# Sheet2s.net
KiCad netlist of a schematic drawn in Altium Designer
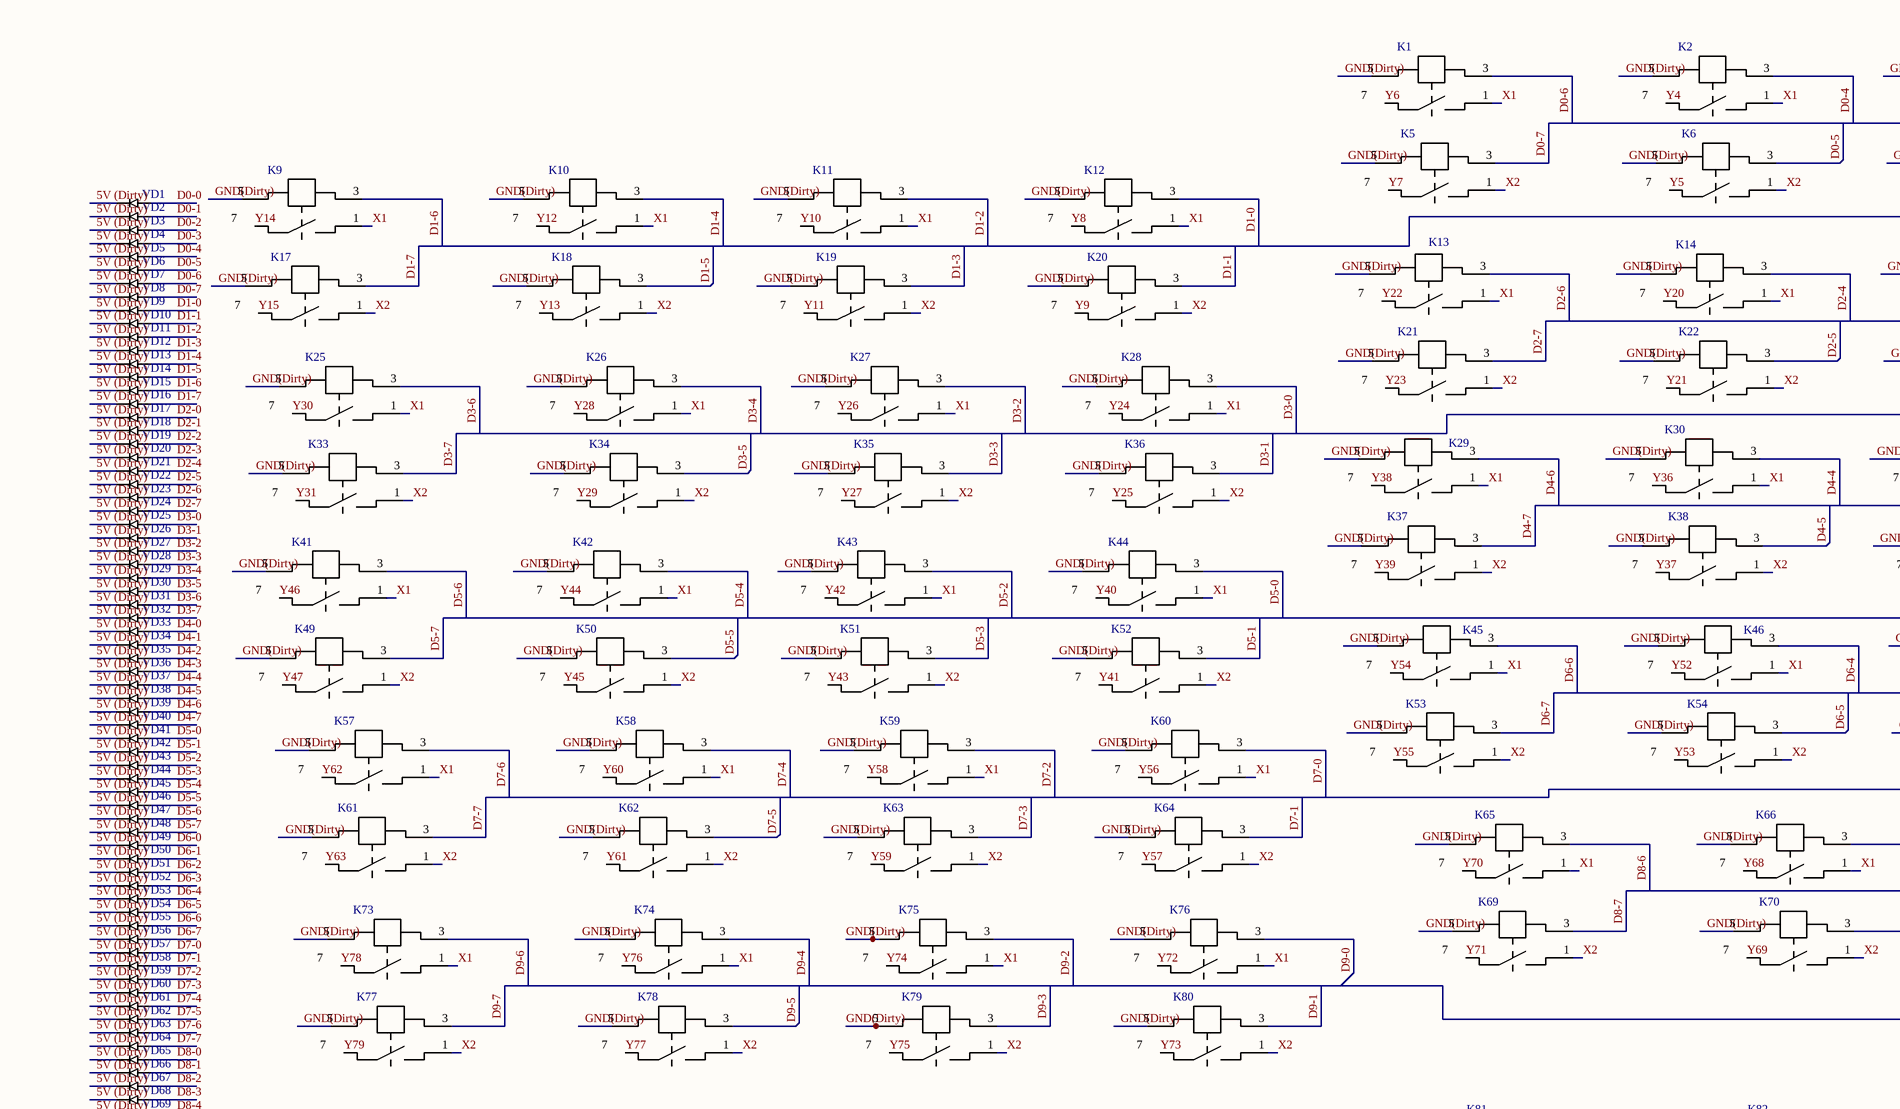
[diagram p0: Sheet2s.SchDoc, top left]
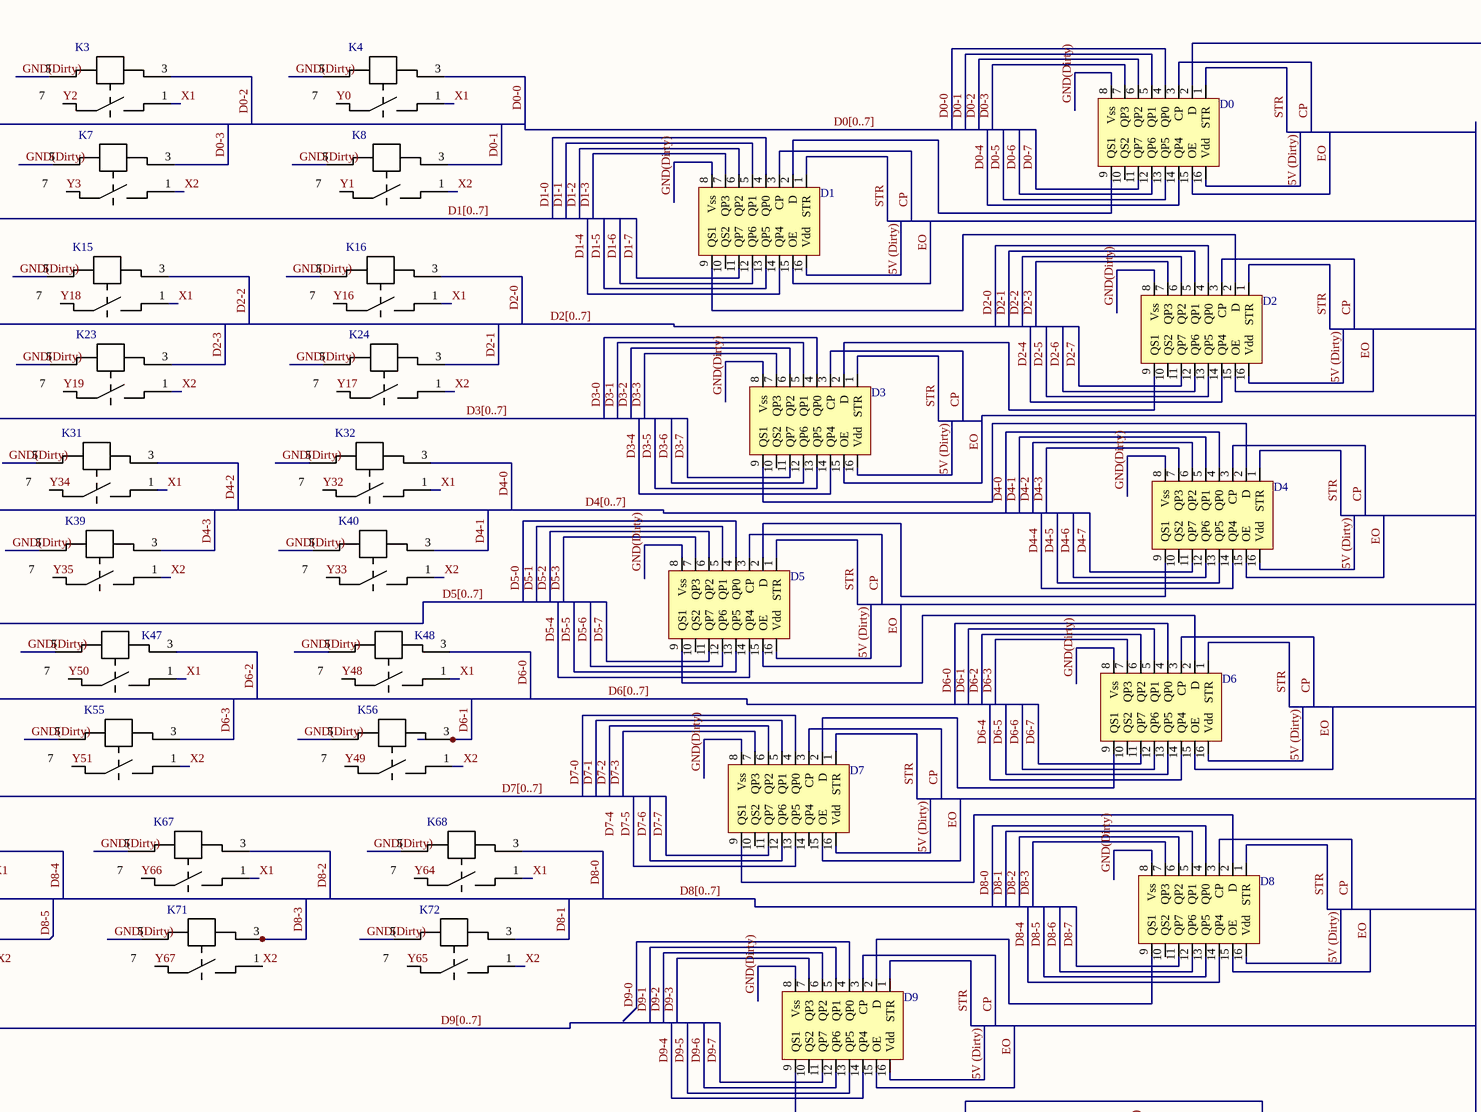
[diagram p1: Sheet2s.SchDoc, top right]
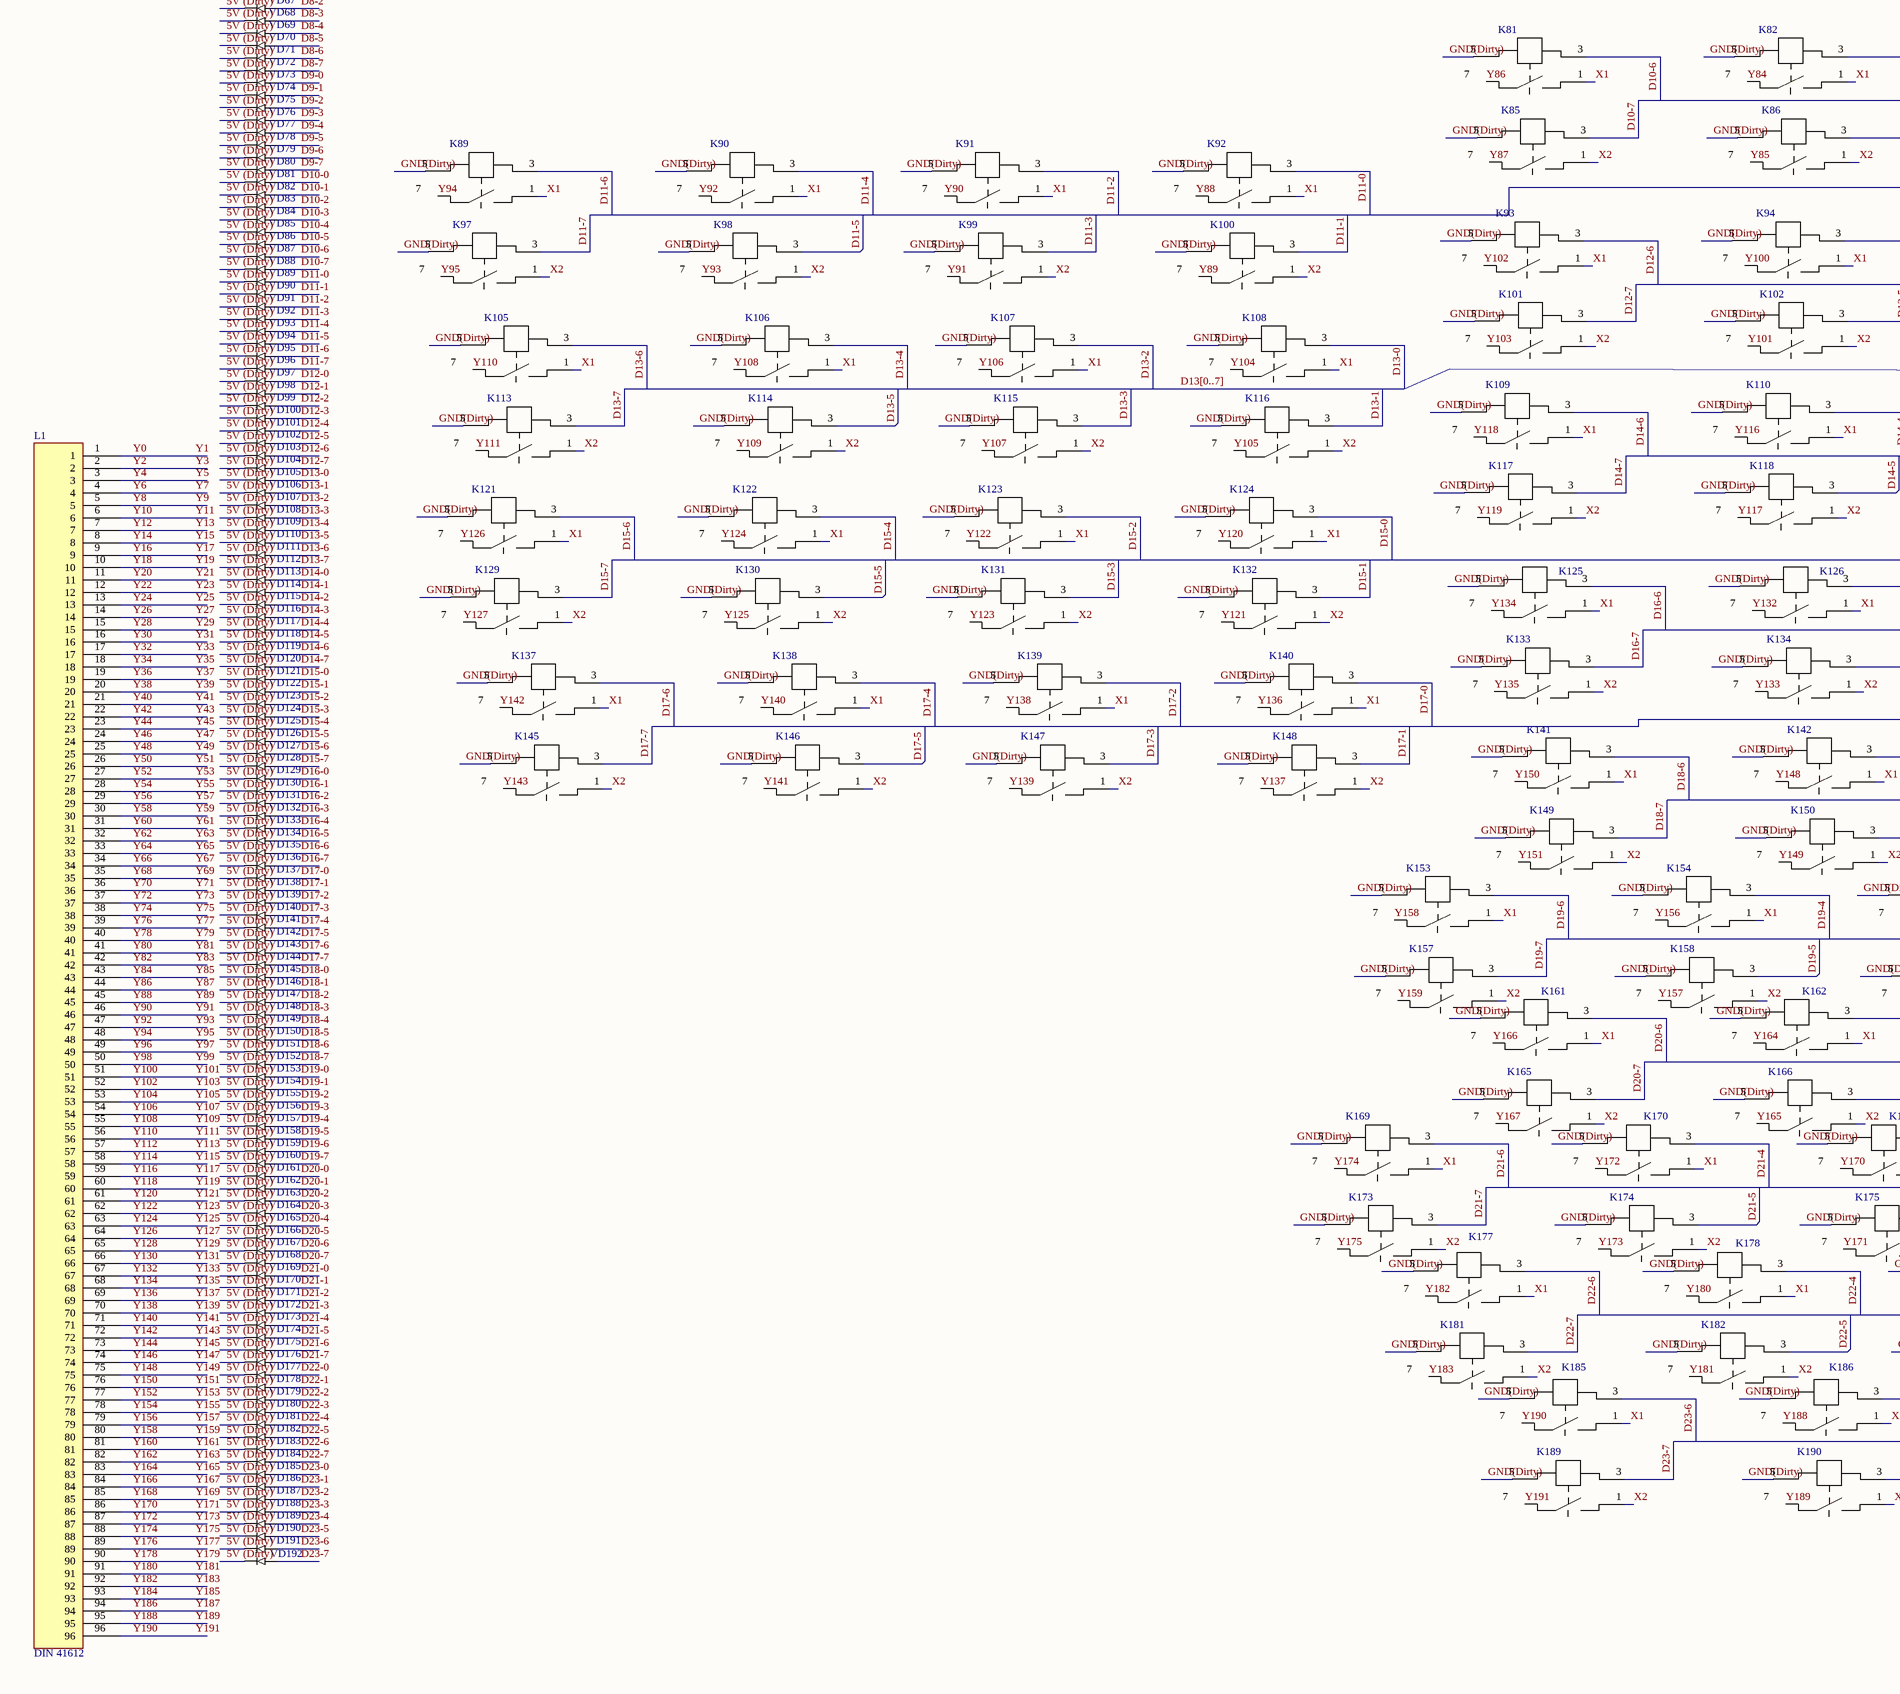
[diagram p2: Sheet2s.SchDoc, bottom left]
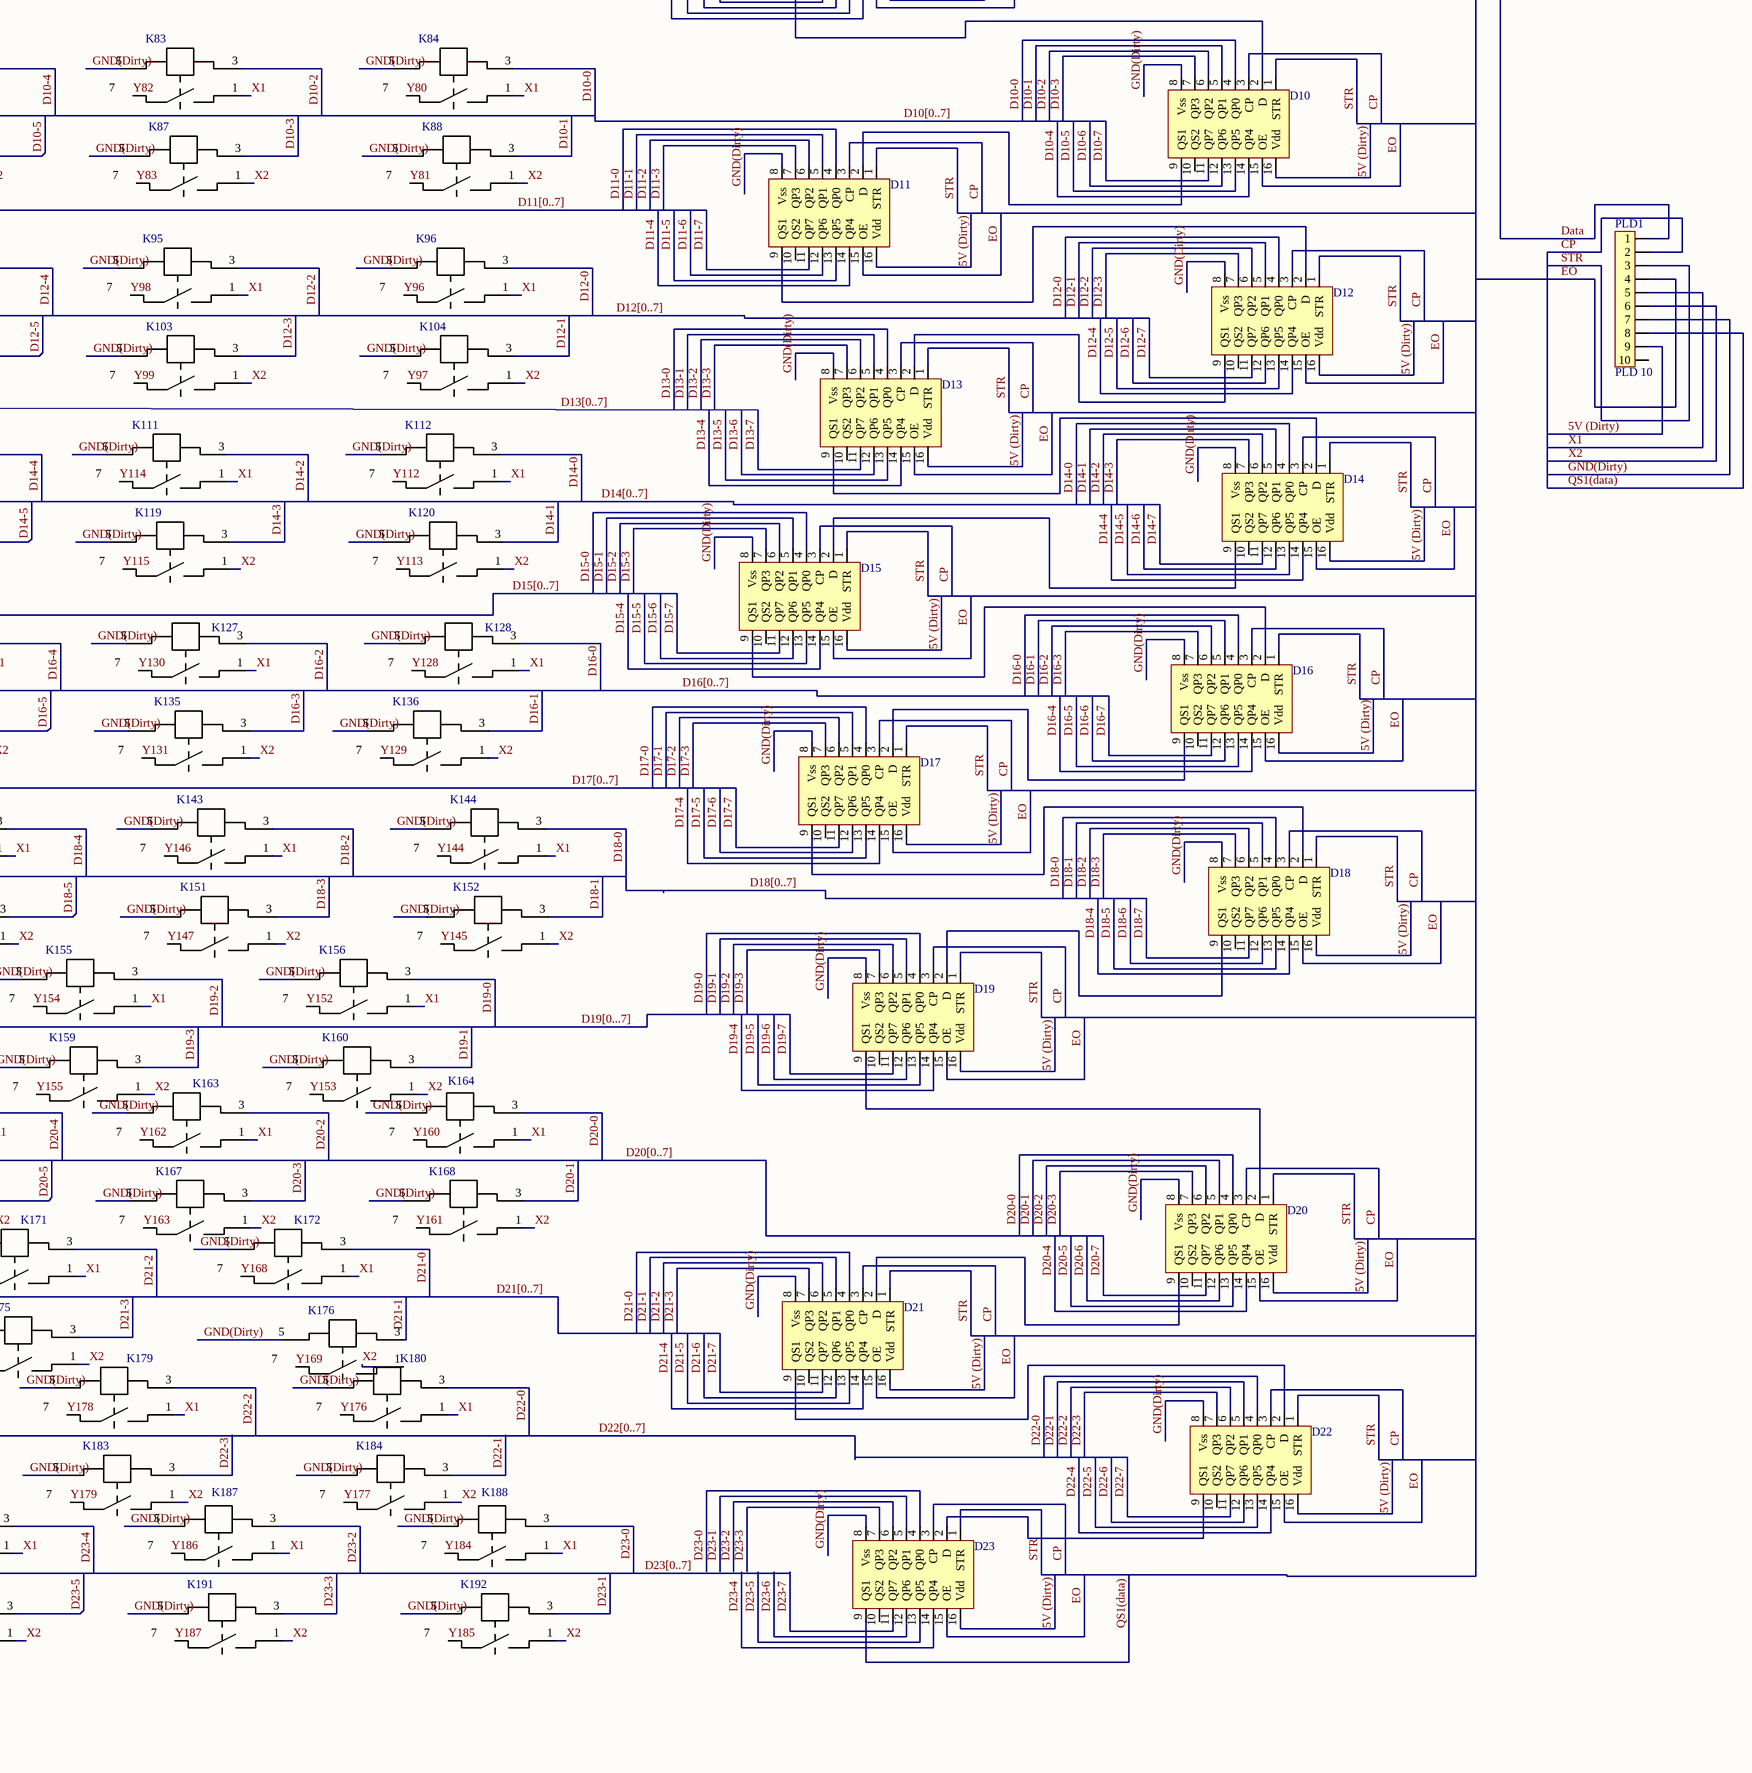
[diagram p3: Sheet2s.SchDoc, bottom right]

(export (version "E")
  (design (tool "Eeschema 10.0.6"))
  (components
    (comp (ref "D0")
      (value "~")
      (footprint "SOP127P600X175-16N")
      (description "Deshifrator")
      (libsource (lib "Schlib1") (part "Component_1"))
    )
    (comp (ref "D1")
      (value "~")
      (footprint "SOP127P600X175-16N")
      (description "Deshifrator")
      (libsource (lib "Schlib1") (part "Component_1"))
    )
    (comp (ref "D2")
      (value "~")
      (footprint "SOP127P600X175-16N")
      (description "Deshifrator")
      (libsource (lib "Schlib1") (part "Component_1"))
    )
    (comp (ref "D3")
      (value "~")
      (footprint "SOP127P600X175-16N")
      (description "Deshifrator")
      (libsource (lib "Schlib1") (part "Component_1"))
    )
    (comp (ref "D4")
      (value "~")
      (footprint "SOP127P600X175-16N")
      (description "Deshifrator")
      (libsource (lib "Schlib1") (part "Component_1"))
    )
    (comp (ref "D5")
      (value "~")
      (footprint "SOP127P600X175-16N")
      (description "Deshifrator")
      (libsource (lib "Schlib1") (part "Component_1"))
    )
    (comp (ref "D6")
      (value "~")
      (footprint "SOP127P600X175-16N")
      (description "Deshifrator")
      (libsource (lib "Schlib1") (part "Component_1"))
    )
    (comp (ref "D7")
      (value "~")
      (footprint "SOP127P600X175-16N")
      (description "Deshifrator")
      (libsource (lib "Schlib1") (part "Component_1"))
    )
    (comp (ref "D8")
      (value "~")
      (footprint "SOP127P600X175-16N")
      (description "Deshifrator")
      (libsource (lib "Schlib1") (part "Component_1"))
    )
    (comp (ref "D9")
      (value "~")
      (footprint "SOP127P600X175-16N")
      (description "Deshifrator")
      (libsource (lib "Schlib1") (part "Component_1"))
    )
    (comp (ref "D10")
      (value "~")
      (footprint "SOP127P600X175-16N")
      (description "Deshifrator")
      (libsource (lib "Schlib1") (part "Component_1"))
    )
    (comp (ref "D11")
      (value "~")
      (footprint "SOP127P600X175-16N")
      (description "Deshifrator")
      (libsource (lib "Schlib1") (part "Component_1"))
    )
    (comp (ref "D12")
      (value "~")
      (footprint "SOP127P600X175-16N")
      (description "Deshifrator")
      (libsource (lib "Schlib1") (part "Component_1"))
    )
    (comp (ref "D13")
      (value "~")
      (footprint "SOP127P600X175-16N")
      (description "Deshifrator")
      (libsource (lib "Schlib1") (part "Component_1"))
    )
    (comp (ref "D14")
      (value "~")
      (footprint "SOP127P600X175-16N")
      (description "Deshifrator")
      (libsource (lib "Schlib1") (part "Component_1"))
    )
    (comp (ref "D15")
      (value "~")
      (footprint "SOP127P600X175-16N")
      (description "Deshifrator")
      (libsource (lib "Schlib1") (part "Component_1"))
    )
    (comp (ref "D16")
      (value "~")
      (footprint "SOP127P600X175-16N")
      (description "Deshifrator")
      (libsource (lib "Schlib1") (part "Component_1"))
    )
    (comp (ref "D17")
      (value "~")
      (footprint "SOP127P600X175-16N")
      (description "Deshifrator")
      (libsource (lib "Schlib1") (part "Component_1"))
    )
    (comp (ref "D18")
      (value "~")
      (footprint "SOP127P600X175-16N")
      (description "Deshifrator")
      (libsource (lib "Schlib1") (part "Component_1"))
    )
    (comp (ref "D19")
      (value "~")
      (footprint "SOP127P600X175-16N")
      (description "Deshifrator")
      (libsource (lib "Schlib1") (part "Component_1"))
    )
    (comp (ref "D20")
      (value "~")
      (footprint "SOP127P600X175-16N")
      (description "Deshifrator")
      (libsource (lib "Schlib1") (part "Component_1"))
    )
    (comp (ref "D21")
      (value "~")
      (footprint "SOP127P600X175-16N")
      (description "Deshifrator")
      (libsource (lib "Schlib1") (part "Component_1"))
    )
    (comp (ref "D22")
      (value "~")
      (footprint "SOP127P600X175-16N")
      (description "Deshifrator")
      (libsource (lib "Schlib1") (part "Component_1"))
    )
    (comp (ref "D23")
      (value "~")
      (footprint "SOP127P600X175-16N")
      (description "Deshifrator")
      (libsource (lib "Schlib1") (part "Component_1"))
    )
    (comp (ref "K1") (value "~") (footprint "TTR-реле") (libsource (lib "Schlib1") (part "TRR1A05D00")))
    (comp (ref "K2") (value "~") (footprint "TTR-реле") (libsource (lib "Schlib1") (part "TRR1A05D00")))
    (comp (ref "K3") (value "~") (footprint "TTR-реле") (libsource (lib "Schlib1") (part "TRR1A05D00")))
    (comp (ref "K4") (value "~") (footprint "TTR-реле") (libsource (lib "Schlib1") (part "TRR1A05D00")))
    (comp (ref "K5") (value "~") (footprint "TTR-реле") (libsource (lib "Schlib1") (part "TRR1A05D00")))
    (comp (ref "K6") (value "~") (footprint "TTR-реле") (libsource (lib "Schlib1") (part "TRR1A05D00")))
    (comp (ref "K7") (value "~") (footprint "TTR-реле") (libsource (lib "Schlib1") (part "TRR1A05D00")))
    (comp (ref "K8") (value "~") (footprint "TTR-реле") (libsource (lib "Schlib1") (part "TRR1A05D00")))
    (comp (ref "K9") (value "~") (footprint "TTR-реле") (libsource (lib "Schlib1") (part "TRR1A05D00")))
    (comp (ref "K10") (value "~") (footprint "TTR-реле") (libsource (lib "Schlib1") (part "TRR1A05D00")))
    (comp (ref "K11") (value "~") (footprint "TTR-реле") (libsource (lib "Schlib1") (part "TRR1A05D00")))
    (comp (ref "K12") (value "~") (footprint "TTR-реле") (libsource (lib "Schlib1") (part "TRR1A05D00")))
    (comp (ref "K13") (value "~") (footprint "TTR-реле") (libsource (lib "Schlib1") (part "TRR1A05D00")))
    (comp (ref "K14") (value "~") (footprint "TTR-реле") (libsource (lib "Schlib1") (part "TRR1A05D00")))
    (comp (ref "K15") (value "~") (footprint "TTR-реле") (libsource (lib "Schlib1") (part "TRR1A05D00")))
    (comp (ref "K16") (value "~") (footprint "TTR-реле") (libsource (lib "Schlib1") (part "TRR1A05D00")))
    (comp (ref "K17") (value "~") (footprint "TTR-реле") (libsource (lib "Schlib1") (part "TRR1A05D00")))
    (comp (ref "K18") (value "~") (footprint "TTR-реле") (libsource (lib "Schlib1") (part "TRR1A05D00")))
    (comp (ref "K19") (value "~") (footprint "TTR-реле") (libsource (lib "Schlib1") (part "TRR1A05D00")))
    (comp (ref "K20") (value "~") (footprint "TTR-реле") (libsource (lib "Schlib1") (part "TRR1A05D00")))
    (comp (ref "K21") (value "~") (footprint "TTR-реле") (libsource (lib "Schlib1") (part "TRR1A05D00")))
    (comp (ref "K22") (value "~") (footprint "TTR-реле") (libsource (lib "Schlib1") (part "TRR1A05D00")))
    (comp (ref "K23") (value "~") (footprint "TTR-реле") (libsource (lib "Schlib1") (part "TRR1A05D00")))
    (comp (ref "K24") (value "~") (footprint "TTR-реле") (libsource (lib "Schlib1") (part "TRR1A05D00")))
    (comp (ref "K25") (value "~") (footprint "TTR-реле") (libsource (lib "Schlib1") (part "TRR1A05D00")))
    (comp (ref "K26") (value "~") (footprint "TTR-реле") (libsource (lib "Schlib1") (part "TRR1A05D00")))
    (comp (ref "K27") (value "~") (footprint "TTR-реле") (libsource (lib "Schlib1") (part "TRR1A05D00")))
    (comp (ref "K28") (value "~") (footprint "TTR-реле") (libsource (lib "Schlib1") (part "TRR1A05D00")))
    (comp (ref "K29") (value "~") (footprint "TTR-реле") (libsource (lib "Schlib1") (part "TRR1A05D00")))
    (comp (ref "K30") (value "~") (footprint "TTR-реле") (libsource (lib "Schlib1") (part "TRR1A05D00")))
    (comp (ref "K31") (value "~") (footprint "TTR-реле") (libsource (lib "Schlib1") (part "TRR1A05D00")))
    (comp (ref "K32") (value "~") (footprint "TTR-реле") (libsource (lib "Schlib1") (part "TRR1A05D00")))
    (comp (ref "K33") (value "~") (footprint "TTR-реле") (libsource (lib "Schlib1") (part "TRR1A05D00")))
    (comp (ref "K34") (value "~") (footprint "TTR-реле") (libsource (lib "Schlib1") (part "TRR1A05D00")))
    (comp (ref "K35") (value "~") (footprint "TTR-реле") (libsource (lib "Schlib1") (part "TRR1A05D00")))
    (comp (ref "K36") (value "~") (footprint "TTR-реле") (libsource (lib "Schlib1") (part "TRR1A05D00")))
    (comp (ref "K37") (value "~") (footprint "TTR-реле") (libsource (lib "Schlib1") (part "TRR1A05D00")))
    (comp (ref "K38") (value "~") (footprint "TTR-реле") (libsource (lib "Schlib1") (part "TRR1A05D00")))
    (comp (ref "K39") (value "~") (footprint "TTR-реле") (libsource (lib "Schlib1") (part "TRR1A05D00")))
    (comp (ref "K40") (value "~") (footprint "TTR-реле") (libsource (lib "Schlib1") (part "TRR1A05D00")))
    (comp (ref "K41") (value "~") (footprint "TTR-реле") (libsource (lib "Schlib1") (part "TRR1A05D00")))
    (comp (ref "K42") (value "~") (footprint "TTR-реле") (libsource (lib "Schlib1") (part "TRR1A05D00")))
    (comp (ref "K43") (value "~") (footprint "TTR-реле") (libsource (lib "Schlib1") (part "TRR1A05D00")))
    (comp (ref "K44") (value "~") (footprint "TTR-реле") (libsource (lib "Schlib1") (part "TRR1A05D00")))
    (comp (ref "K45") (value "~") (footprint "TTR-реле") (libsource (lib "Schlib1") (part "TRR1A05D00")))
    (comp (ref "K46") (value "~") (footprint "TTR-реле") (libsource (lib "Schlib1") (part "TRR1A05D00")))
    (comp (ref "K47") (value "~") (footprint "TTR-реле") (libsource (lib "Schlib1") (part "TRR1A05D00")))
    (comp (ref "K48") (value "~") (footprint "TTR-реле") (libsource (lib "Schlib1") (part "TRR1A05D00")))
    (comp (ref "K49") (value "~") (footprint "TTR-реле") (libsource (lib "Schlib1") (part "TRR1A05D00")))
    (comp (ref "K50") (value "~") (footprint "TTR-реле") (libsource (lib "Schlib1") (part "TRR1A05D00")))
    (comp (ref "K51") (value "~") (footprint "TTR-реле") (libsource (lib "Schlib1") (part "TRR1A05D00")))
    (comp (ref "K52") (value "~") (footprint "TTR-реле") (libsource (lib "Schlib1") (part "TRR1A05D00")))
    (comp (ref "K53") (value "~") (footprint "TTR-реле") (libsource (lib "Schlib1") (part "TRR1A05D00")))
    (comp (ref "K54") (value "~") (footprint "TTR-реле") (libsource (lib "Schlib1") (part "TRR1A05D00")))
    (comp (ref "K55") (value "~") (footprint "TTR-реле") (libsource (lib "Schlib1") (part "TRR1A05D00")))
    (comp (ref "K56") (value "~") (footprint "TTR-реле") (libsource (lib "Schlib1") (part "TRR1A05D00")))
    (comp (ref "K57") (value "~") (footprint "TTR-реле") (libsource (lib "Schlib1") (part "TRR1A05D00")))
    (comp (ref "K58") (value "~") (footprint "TTR-реле") (libsource (lib "Schlib1") (part "TRR1A05D00")))
    (comp (ref "K59") (value "~") (footprint "TTR-реле") (libsource (lib "Schlib1") (part "TRR1A05D00")))
    (comp (ref "K60") (value "~") (footprint "TTR-реле") (libsource (lib "Schlib1") (part "TRR1A05D00")))
    (comp (ref "K61") (value "~") (footprint "TTR-реле") (libsource (lib "Schlib1") (part "TRR1A05D00")))
    (comp (ref "K62") (value "~") (footprint "TTR-реле") (libsource (lib "Schlib1") (part "TRR1A05D00")))
    (comp (ref "K63") (value "~") (footprint "TTR-реле") (libsource (lib "Schlib1") (part "TRR1A05D00")))
    (comp (ref "K64") (value "~") (footprint "TTR-реле") (libsource (lib "Schlib1") (part "TRR1A05D00")))
    (comp (ref "K65") (value "~") (footprint "TTR-реле") (libsource (lib "Schlib1") (part "TRR1A05D00")))
    (comp (ref "K66") (value "~") (footprint "TTR-реле") (libsource (lib "Schlib1") (part "TRR1A05D00")))
    (comp (ref "K67") (value "~") (footprint "TTR-реле") (libsource (lib "Schlib1") (part "TRR1A05D00")))
    (comp (ref "K68") (value "~") (footprint "TTR-реле") (libsource (lib "Schlib1") (part "TRR1A05D00")))
    (comp (ref "K69") (value "~") (footprint "TTR-реле") (libsource (lib "Schlib1") (part "TRR1A05D00")))
    (comp (ref "K70") (value "~") (footprint "TTR-реле") (libsource (lib "Schlib1") (part "TRR1A05D00")))
    (comp (ref "K71") (value "~") (footprint "TTR-реле") (libsource (lib "Schlib1") (part "TRR1A05D00")))
    (comp (ref "K72") (value "~") (footprint "TTR-реле") (libsource (lib "Schlib1") (part "TRR1A05D00")))
    (comp (ref "K73") (value "~") (footprint "TTR-реле") (libsource (lib "Schlib1") (part "TRR1A05D00")))
    (comp (ref "K74") (value "~") (footprint "TTR-реле") (libsource (lib "Schlib1") (part "TRR1A05D00")))
    (comp (ref "K75") (value "~") (footprint "TTR-реле") (libsource (lib "Schlib1") (part "TRR1A05D00")))
    (comp (ref "K76") (value "~") (footprint "TTR-реле") (libsource (lib "Schlib1") (part "TRR1A05D00")))
    (comp (ref "K77") (value "~") (footprint "TTR-реле") (libsource (lib "Schlib1") (part "TRR1A05D00")))
    (comp (ref "K78") (value "~") (footprint "TTR-реле") (libsource (lib "Schlib1") (part "TRR1A05D00")))
    (comp (ref "K79") (value "~") (footprint "TTR-реле") (libsource (lib "Schlib1") (part "TRR1A05D00")))
    (comp (ref "K80") (value "~") (footprint "TTR-реле") (libsource (lib "Schlib1") (part "TRR1A05D00")))
    (comp (ref "K81") (value "~") (footprint "TTR-реле") (libsource (lib "Schlib1") (part "TRR1A05D00")))
    (comp (ref "K82") (value "~") (footprint "TTR-реле") (libsource (lib "Schlib1") (part "TRR1A05D00")))
    (comp (ref "K83") (value "~") (footprint "TTR-реле") (libsource (lib "Schlib1") (part "TRR1A05D00")))
    (comp (ref "K84") (value "~") (footprint "TTR-реле") (libsource (lib "Schlib1") (part "TRR1A05D00")))
    (comp (ref "K85") (value "~") (footprint "TTR-реле") (libsource (lib "Schlib1") (part "TRR1A05D00")))
    (comp (ref "K86") (value "~") (footprint "TTR-реле") (libsource (lib "Schlib1") (part "TRR1A05D00")))
    (comp (ref "K87") (value "~") (footprint "TTR-реле") (libsource (lib "Schlib1") (part "TRR1A05D00")))
    (comp (ref "K88") (value "~") (footprint "TTR-реле") (libsource (lib "Schlib1") (part "TRR1A05D00")))
    (comp (ref "K89") (value "~") (footprint "TTR-реле") (libsource (lib "Schlib1") (part "TRR1A05D00")))
    (comp (ref "K90") (value "~") (footprint "TTR-реле") (libsource (lib "Schlib1") (part "TRR1A05D00")))
    (comp (ref "K91") (value "~") (footprint "TTR-реле") (libsource (lib "Schlib1") (part "TRR1A05D00")))
    (comp (ref "K92") (value "~") (footprint "TTR-реле") (libsource (lib "Schlib1") (part "TRR1A05D00")))
    (comp (ref "K93") (value "~") (footprint "TTR-реле") (libsource (lib "Schlib1") (part "TRR1A05D00")))
    (comp (ref "K94") (value "~") (footprint "TTR-реле") (libsource (lib "Schlib1") (part "TRR1A05D00")))
    (comp (ref "K95") (value "~") (footprint "TTR-реле") (libsource (lib "Schlib1") (part "TRR1A05D00")))
    (comp (ref "K96") (value "~") (footprint "TTR-реле") (libsource (lib "Schlib1") (part "TRR1A05D00")))
    (comp (ref "K97") (value "~") (footprint "TTR-реле") (libsource (lib "Schlib1") (part "TRR1A05D00")))
    (comp (ref "K98") (value "~") (footprint "TTR-реле") (libsource (lib "Schlib1") (part "TRR1A05D00")))
    (comp (ref "K99") (value "~") (footprint "TTR-реле") (libsource (lib "Schlib1") (part "TRR1A05D00")))
    (comp (ref "K100") (value "~") (footprint "TTR-реле") (libsource (lib "Schlib1") (part "TRR1A05D00")))
    (comp (ref "K101") (value "~") (footprint "TTR-реле") (libsource (lib "Schlib1") (part "TRR1A05D00")))
    (comp (ref "K102") (value "~") (footprint "TTR-реле") (libsource (lib "Schlib1") (part "TRR1A05D00")))
    (comp (ref "K103") (value "~") (footprint "TTR-реле") (libsource (lib "Schlib1") (part "TRR1A05D00")))
    (comp (ref "K104") (value "~") (footprint "TTR-реле") (libsource (lib "Schlib1") (part "TRR1A05D00")))
    (comp (ref "K105") (value "~") (footprint "TTR-реле") (libsource (lib "Schlib1") (part "TRR1A05D00")))
    (comp (ref "K106") (value "~") (footprint "TTR-реле") (libsource (lib "Schlib1") (part "TRR1A05D00")))
    (comp (ref "K107") (value "~") (footprint "TTR-реле") (libsource (lib "Schlib1") (part "TRR1A05D00")))
    (comp (ref "K108") (value "~") (footprint "TTR-реле") (libsource (lib "Schlib1") (part "TRR1A05D00")))
    (comp (ref "K109") (value "~") (footprint "TTR-реле") (libsource (lib "Schlib1") (part "TRR1A05D00")))
    (comp (ref "K110") (value "~") (footprint "TTR-реле") (libsource (lib "Schlib1") (part "TRR1A05D00")))
    (comp (ref "K111") (value "~") (footprint "TTR-реле") (libsource (lib "Schlib1") (part "TRR1A05D00")))
    (comp (ref "K112") (value "~") (footprint "TTR-реле") (libsource (lib "Schlib1") (part "TRR1A05D00")))
    (comp (ref "K113") (value "~") (footprint "TTR-реле") (libsource (lib "Schlib1") (part "TRR1A05D00")))
    (comp (ref "K114") (value "~") (footprint "TTR-реле") (libsource (lib "Schlib1") (part "TRR1A05D00")))
    (comp (ref "K115") (value "~") (footprint "TTR-реле") (libsource (lib "Schlib1") (part "TRR1A05D00")))
    (comp (ref "K116") (value "~") (footprint "TTR-реле") (libsource (lib "Schlib1") (part "TRR1A05D00")))
    (comp (ref "K117") (value "~") (footprint "TTR-реле") (libsource (lib "Schlib1") (part "TRR1A05D00")))
    (comp (ref "K118") (value "~") (footprint "TTR-реле") (libsource (lib "Schlib1") (part "TRR1A05D00")))
    (comp (ref "K119") (value "~") (footprint "TTR-реле") (libsource (lib "Schlib1") (part "TRR1A05D00")))
    (comp (ref "K120") (value "~") (footprint "TTR-реле") (libsource (lib "Schlib1") (part "TRR1A05D00")))
    (comp (ref "K121") (value "~") (footprint "TTR-реле") (libsource (lib "Schlib1") (part "TRR1A05D00")))
    (comp (ref "K122") (value "~") (footprint "TTR-реле") (libsource (lib "Schlib1") (part "TRR1A05D00")))
    (comp (ref "K123") (value "~") (footprint "TTR-реле") (libsource (lib "Schlib1") (part "TRR1A05D00")))
    (comp (ref "K124") (value "~") (footprint "TTR-реле") (libsource (lib "Schlib1") (part "TRR1A05D00")))
    (comp (ref "K125") (value "~") (footprint "TTR-реле") (libsource (lib "Schlib1") (part "TRR1A05D00")))
    (comp (ref "K126") (value "~") (footprint "TTR-реле") (libsource (lib "Schlib1") (part "TRR1A05D00")))
    (comp (ref "K127") (value "~") (footprint "TTR-реле") (libsource (lib "Schlib1") (part "TRR1A05D00")))
    (comp (ref "K128") (value "~") (footprint "TTR-реле") (libsource (lib "Schlib1") (part "TRR1A05D00")))
    (comp (ref "K129") (value "~") (footprint "TTR-реле") (libsource (lib "Schlib1") (part "TRR1A05D00")))
    (comp (ref "K130") (value "~") (footprint "TTR-реле") (libsource (lib "Schlib1") (part "TRR1A05D00")))
    (comp (ref "K131") (value "~") (footprint "TTR-реле") (libsource (lib "Schlib1") (part "TRR1A05D00")))
    (comp (ref "K132") (value "~") (footprint "TTR-реле") (libsource (lib "Schlib1") (part "TRR1A05D00")))
    (comp (ref "K133") (value "~") (footprint "TTR-реле") (libsource (lib "Schlib1") (part "TRR1A05D00")))
    (comp (ref "K134") (value "~") (footprint "TTR-реле") (libsource (lib "Schlib1") (part "TRR1A05D00")))
    (comp (ref "K135") (value "~") (footprint "TTR-реле") (libsource (lib "Schlib1") (part "TRR1A05D00")))
    (comp (ref "K136") (value "~") (footprint "TTR-реле") (libsource (lib "Schlib1") (part "TRR1A05D00")))
    (comp (ref "K137") (value "~") (footprint "TTR-реле") (libsource (lib "Schlib1") (part "TRR1A05D00")))
    (comp (ref "K138") (value "~") (footprint "TTR-реле") (libsource (lib "Schlib1") (part "TRR1A05D00")))
    (comp (ref "K139") (value "~") (footprint "TTR-реле") (libsource (lib "Schlib1") (part "TRR1A05D00")))
    (comp (ref "K140") (value "~") (footprint "TTR-реле") (libsource (lib "Schlib1") (part "TRR1A05D00")))
    (comp (ref "K141") (value "~") (footprint "TTR-реле") (libsource (lib "Schlib1") (part "TRR1A05D00")))
    (comp (ref "K142") (value "~") (footprint "TTR-реле") (libsource (lib "Schlib1") (part "TRR1A05D00")))
    (comp (ref "K143") (value "~") (footprint "TTR-реле") (libsource (lib "Schlib1") (part "TRR1A05D00")))
    (comp (ref "K144") (value "~") (footprint "TTR-реле") (libsource (lib "Schlib1") (part "TRR1A05D00")))
    (comp (ref "K145") (value "~") (footprint "TTR-реле") (libsource (lib "Schlib1") (part "TRR1A05D00")))
    (comp (ref "K146") (value "~") (footprint "TTR-реле") (libsource (lib "Schlib1") (part "TRR1A05D00")))
    (comp (ref "K147") (value "~") (footprint "TTR-реле") (libsource (lib "Schlib1") (part "TRR1A05D00")))
    (comp (ref "K148") (value "~") (footprint "TTR-реле") (libsource (lib "Schlib1") (part "TRR1A05D00")))
    (comp (ref "K149") (value "~") (footprint "TTR-реле") (libsource (lib "Schlib1") (part "TRR1A05D00")))
    (comp (ref "K150") (value "~") (footprint "TTR-реле") (libsource (lib "Schlib1") (part "TRR1A05D00")))
    (comp (ref "K151") (value "~") (footprint "TTR-реле") (libsource (lib "Schlib1") (part "TRR1A05D00")))
    (comp (ref "K152") (value "~") (footprint "TTR-реле") (libsource (lib "Schlib1") (part "TRR1A05D00")))
    (comp (ref "K153") (value "~") (footprint "TTR-реле") (libsource (lib "Schlib1") (part "TRR1A05D00")))
    (comp (ref "K154") (value "~") (footprint "TTR-реле") (libsource (lib "Schlib1") (part "TRR1A05D00")))
    (comp (ref "K155") (value "~") (footprint "TTR-реле") (libsource (lib "Schlib1") (part "TRR1A05D00")))
    (comp (ref "K156") (value "~") (footprint "TTR-реле") (libsource (lib "Schlib1") (part "TRR1A05D00")))
    (comp (ref "K157") (value "~") (footprint "TTR-реле") (libsource (lib "Schlib1") (part "TRR1A05D00")))
    (comp (ref "K158") (value "~") (footprint "TTR-реле") (libsource (lib "Schlib1") (part "TRR1A05D00")))
    (comp (ref "K159") (value "~") (footprint "TTR-реле") (libsource (lib "Schlib1") (part "TRR1A05D00")))
    (comp (ref "K160") (value "~") (footprint "TTR-реле") (libsource (lib "Schlib1") (part "TRR1A05D00")))
    (comp (ref "K161") (value "~") (footprint "TTR-реле") (libsource (lib "Schlib1") (part "TRR1A05D00")))
    (comp (ref "K162") (value "~") (footprint "TTR-реле") (libsource (lib "Schlib1") (part "TRR1A05D00")))
    (comp (ref "K163") (value "~") (footprint "TTR-реле") (libsource (lib "Schlib1") (part "TRR1A05D00")))
    (comp (ref "K164") (value "~") (footprint "TTR-реле") (libsource (lib "Schlib1") (part "TRR1A05D00")))
    (comp (ref "K165") (value "~") (footprint "TTR-реле") (libsource (lib "Schlib1") (part "TRR1A05D00")))
    (comp (ref "K166") (value "~") (footprint "TTR-реле") (libsource (lib "Schlib1") (part "TRR1A05D00")))
    (comp (ref "K167") (value "~") (footprint "TTR-реле") (libsource (lib "Schlib1") (part "TRR1A05D00")))
    (comp (ref "K168") (value "~") (footprint "TTR-реле") (libsource (lib "Schlib1") (part "TRR1A05D00")))
    (comp (ref "K169") (value "~") (footprint "TTR-реле") (libsource (lib "Schlib1") (part "TRR1A05D00")))
    (comp (ref "K170") (value "~") (footprint "TTR-реле") (libsource (lib "Schlib1") (part "TRR1A05D00")))
    (comp (ref "K171") (value "~") (footprint "TTR-реле") (libsource (lib "Schlib1") (part "TRR1A05D00")))
    (comp (ref "K172") (value "~") (footprint "TTR-реле") (libsource (lib "Schlib1") (part "TRR1A05D00")))
    (comp (ref "K173") (value "~") (footprint "TTR-реле") (libsource (lib "Schlib1") (part "TRR1A05D00")))
    (comp (ref "K174") (value "~") (footprint "TTR-реле") (libsource (lib "Schlib1") (part "TRR1A05D00")))
    (comp (ref "K175") (value "~") (footprint "TTR-реле") (libsource (lib "Schlib1") (part "TRR1A05D00")))
    (comp (ref "K176") (value "~") (footprint "TTR-реле") (libsource (lib "Schlib1") (part "TRR1A05D00")))
    (comp (ref "K177") (value "~") (footprint "TTR-реле") (libsource (lib "Schlib1") (part "TRR1A05D00")))
    (comp (ref "K178") (value "~") (footprint "TTR-реле") (libsource (lib "Schlib1") (part "TRR1A05D00")))
    (comp (ref "K179") (value "~") (footprint "TTR-реле") (libsource (lib "Schlib1") (part "TRR1A05D00")))
    (comp (ref "K180") (value "~") (footprint "TTR-реле") (libsource (lib "Schlib1") (part "TRR1A05D00")))
    (comp (ref "K181") (value "~") (footprint "TTR-реле") (libsource (lib "Schlib1") (part "TRR1A05D00")))
    (comp (ref "K182") (value "~") (footprint "TTR-реле") (libsource (lib "Schlib1") (part "TRR1A05D00")))
    (comp (ref "K183") (value "~") (footprint "TTR-реле") (libsource (lib "Schlib1") (part "TRR1A05D00")))
    (comp (ref "K184") (value "~") (footprint "TTR-реле") (libsource (lib "Schlib1") (part "TRR1A05D00")))
    (comp (ref "K185") (value "~") (footprint "TTR-реле") (libsource (lib "Schlib1") (part "TRR1A05D00")))
    (comp (ref "K186") (value "~") (footprint "TTR-реле") (libsource (lib "Schlib1") (part "TRR1A05D00")))
    (comp (ref "K187") (value "~") (footprint "TTR-реле") (libsource (lib "Schlib1") (part "TRR1A05D00")))
    (comp (ref "K188") (value "~") (footprint "TTR-реле") (libsource (lib "Schlib1") (part "TRR1A05D00")))
    (comp (ref "K189") (value "~") (footprint "TTR-реле") (libsource (lib "Schlib1") (part "TRR1A05D00")))
    (comp (ref "K190") (value "~") (footprint "TTR-реле") (libsource (lib "Schlib1") (part "TRR1A05D00")))
    (comp (ref "K191") (value "~") (footprint "TTR-реле") (libsource (lib "Schlib1") (part "TRR1A05D00")))
    (comp (ref "K192") (value "~") (footprint "TTR-реле") (libsource (lib "Schlib1") (part "TRR1A05D00")))
    (comp (ref "L1") (value "DIN 41612") (footprint "DIN41612") (libsource (lib "Schlib1") (part "DIN41612")))
    (comp (ref "PLD1") (value "PLD 10") (footprint "PLD 10") (libsource (lib "Schlib1") (part "PLD 10")))
    (comp (ref "VD1") (value "BAS216") (footprint "BAS216") (libsource (lib "Schlib1") (part "Диод")))
    (comp (ref "VD2") (value "BAS216") (footprint "BAS216") (libsource (lib "Schlib1") (part "Диод")))
    (comp (ref "VD3") (value "BAS216") (footprint "BAS216") (libsource (lib "Schlib1") (part "Диод")))
    (comp (ref "VD4") (value "BAS216") (footprint "BAS216") (libsource (lib "Schlib1") (part "Диод")))
    (comp (ref "VD5") (value "BAS216") (footprint "BAS216") (libsource (lib "Schlib1") (part "Диод")))
    (comp (ref "VD6") (value "BAS216") (footprint "BAS216") (libsource (lib "Schlib1") (part "Диод")))
    (comp (ref "VD7") (value "BAS216") (footprint "BAS216") (libsource (lib "Schlib1") (part "Диод")))
    (comp (ref "VD8") (value "BAS216") (footprint "BAS216") (libsource (lib "Schlib1") (part "Диод")))
    (comp (ref "VD9") (value "BAS216") (footprint "BAS216") (libsource (lib "Schlib1") (part "Диод")))
    (comp (ref "VD10") (value "BAS216") (footprint "BAS216") (libsource (lib "Schlib1") (part "Диод")))
    (comp (ref "VD11") (value "BAS216") (footprint "BAS216") (libsource (lib "Schlib1") (part "Диод")))
    (comp (ref "VD12") (value "BAS216") (footprint "BAS216") (libsource (lib "Schlib1") (part "Диод")))
    (comp (ref "VD13") (value "BAS216") (footprint "BAS216") (libsource (lib "Schlib1") (part "Диод")))
    (comp (ref "VD14") (value "BAS216") (footprint "BAS216") (libsource (lib "Schlib1") (part "Диод")))
    (comp (ref "VD15") (value "BAS216") (footprint "BAS216") (libsource (lib "Schlib1") (part "Диод")))
    (comp (ref "VD16") (value "BAS216") (footprint "BAS216") (libsource (lib "Schlib1") (part "Диод")))
    (comp (ref "VD17") (value "BAS216") (footprint "BAS216") (libsource (lib "Schlib1") (part "Диод")))
    (comp (ref "VD18") (value "BAS216") (footprint "BAS216") (libsource (lib "Schlib1") (part "Диод")))
    (comp (ref "VD19") (value "BAS216") (footprint "BAS216") (libsource (lib "Schlib1") (part "Диод")))
    (comp (ref "VD20") (value "BAS216") (footprint "BAS216") (libsource (lib "Schlib1") (part "Диод")))
    (comp (ref "VD21") (value "BAS216") (footprint "BAS216") (libsource (lib "Schlib1") (part "Диод")))
    (comp (ref "VD22") (value "BAS216") (footprint "BAS216") (libsource (lib "Schlib1") (part "Диод")))
    (comp (ref "VD23") (value "BAS216") (footprint "BAS216") (libsource (lib "Schlib1") (part "Диод")))
    (comp (ref "VD24") (value "BAS216") (footprint "BAS216") (libsource (lib "Schlib1") (part "Диод")))
    (comp (ref "VD25") (value "BAS216") (footprint "BAS216") (libsource (lib "Schlib1") (part "Диод")))
    (comp (ref "VD26") (value "BAS216") (footprint "BAS216") (libsource (lib "Schlib1") (part "Диод")))
    (comp (ref "VD27") (value "BAS216") (footprint "BAS216") (libsource (lib "Schlib1") (part "Диод")))
    (comp (ref "VD28") (value "BAS216") (footprint "BAS216") (libsource (lib "Schlib1") (part "Диод")))
    (comp (ref "VD29") (value "BAS216") (footprint "BAS216") (libsource (lib "Schlib1") (part "Диод")))
    (comp (ref "VD30") (value "BAS216") (footprint "BAS216") (libsource (lib "Schlib1") (part "Диод")))
    (comp (ref "VD31") (value "BAS216") (footprint "BAS216") (libsource (lib "Schlib1") (part "Диод")))
    (comp (ref "VD32") (value "BAS216") (footprint "BAS216") (libsource (lib "Schlib1") (part "Диод")))
    (comp (ref "VD33") (value "BAS216") (footprint "BAS216") (libsource (lib "Schlib1") (part "Диод")))
    (comp (ref "VD34") (value "BAS216") (footprint "BAS216") (libsource (lib "Schlib1") (part "Диод")))
    (comp (ref "VD35") (value "BAS216") (footprint "BAS216") (libsource (lib "Schlib1") (part "Диод")))
    (comp (ref "VD36") (value "BAS216") (footprint "BAS216") (libsource (lib "Schlib1") (part "Диод")))
    (comp (ref "VD37") (value "BAS216") (footprint "BAS216") (libsource (lib "Schlib1") (part "Диод")))
    (comp (ref "VD38") (value "BAS216") (footprint "BAS216") (libsource (lib "Schlib1") (part "Диод")))
    (comp (ref "VD39") (value "BAS216") (footprint "BAS216") (libsource (lib "Schlib1") (part "Диод")))
    (comp (ref "VD40") (value "BAS216") (footprint "BAS216") (libsource (lib "Schlib1") (part "Диод")))
    (comp (ref "VD41") (value "BAS216") (footprint "BAS216") (libsource (lib "Schlib1") (part "Диод")))
    (comp (ref "VD42") (value "BAS216") (footprint "BAS216") (libsource (lib "Schlib1") (part "Диод")))
    (comp (ref "VD43") (value "BAS216") (footprint "BAS216") (libsource (lib "Schlib1") (part "Диод")))
    (comp (ref "VD44") (value "BAS216") (footprint "BAS216") (libsource (lib "Schlib1") (part "Диод")))
    (comp (ref "VD45") (value "BAS216") (footprint "BAS216") (libsource (lib "Schlib1") (part "Диод")))
    (comp (ref "VD46") (value "BAS216") (footprint "BAS216") (libsource (lib "Schlib1") (part "Диод")))
    (comp (ref "VD47") (value "BAS216") (footprint "BAS216") (libsource (lib "Schlib1") (part "Диод")))
    (comp (ref "VD48") (value "BAS216") (footprint "BAS216") (libsource (lib "Schlib1") (part "Диод")))
    (comp (ref "VD49") (value "BAS216") (footprint "BAS216") (libsource (lib "Schlib1") (part "Диод")))
    (comp (ref "VD50") (value "BAS216") (footprint "BAS216") (libsource (lib "Schlib1") (part "Диод")))
    (comp (ref "VD51") (value "BAS216") (footprint "BAS216") (libsource (lib "Schlib1") (part "Диод")))
    (comp (ref "VD52") (value "BAS216") (footprint "BAS216") (libsource (lib "Schlib1") (part "Диод")))
    (comp (ref "VD53") (value "BAS216") (footprint "BAS216") (libsource (lib "Schlib1") (part "Диод")))
    (comp (ref "VD54") (value "BAS216") (footprint "BAS216") (libsource (lib "Schlib1") (part "Диод")))
    (comp (ref "VD55") (value "BAS216") (footprint "BAS216") (libsource (lib "Schlib1") (part "Диод")))
    (comp (ref "VD56") (value "BAS216") (footprint "BAS216") (libsource (lib "Schlib1") (part "Диод")))
    (comp (ref "VD57") (value "BAS216") (footprint "BAS216") (libsource (lib "Schlib1") (part "Диод")))
    (comp (ref "VD58") (value "BAS216") (footprint "BAS216") (libsource (lib "Schlib1") (part "Диод")))
    (comp (ref "VD59") (value "BAS216") (footprint "BAS216") (libsource (lib "Schlib1") (part "Диод")))
    (comp (ref "VD60") (value "BAS216") (footprint "BAS216") (libsource (lib "Schlib1") (part "Диод")))
    (comp (ref "VD61") (value "BAS216") (footprint "BAS216") (libsource (lib "Schlib1") (part "Диод")))
    (comp (ref "VD62") (value "BAS216") (footprint "BAS216") (libsource (lib "Schlib1") (part "Диод")))
    (comp (ref "VD63") (value "BAS216") (footprint "BAS216") (libsource (lib "Schlib1") (part "Диод")))
    (comp (ref "VD64") (value "BAS216") (footprint "BAS216") (libsource (lib "Schlib1") (part "Диод")))
    (comp (ref "VD65") (value "BAS216") (footprint "BAS216") (libsource (lib "Schlib1") (part "Диод")))
    (comp (ref "VD66") (value "BAS216") (footprint "BAS216") (libsource (lib "Schlib1") (part "Диод")))
    (comp (ref "VD67") (value "BAS216") (footprint "BAS216") (libsource (lib "Schlib1") (part "Диод")))
    (comp (ref "VD68") (value "BAS216") (footprint "BAS216") (libsource (lib "Schlib1") (part "Диод")))
    (comp (ref "VD69") (value "BAS216") (footprint "BAS216") (libsource (lib "Schlib1") (part "Диод")))
    (comp (ref "VD70") (value "BAS216") (footprint "BAS216") (libsource (lib "Schlib1") (part "Диод")))
    (comp (ref "VD71") (value "BAS216") (footprint "BAS216") (libsource (lib "Schlib1") (part "Диод")))
    (comp (ref "VD72") (value "BAS216") (footprint "BAS216") (libsource (lib "Schlib1") (part "Диод")))
    (comp (ref "VD73") (value "BAS216") (footprint "BAS216") (libsource (lib "Schlib1") (part "Диод")))
    (comp (ref "VD74") (value "BAS216") (footprint "BAS216") (libsource (lib "Schlib1") (part "Диод")))
    (comp (ref "VD75") (value "BAS216") (footprint "BAS216") (libsource (lib "Schlib1") (part "Диод")))
    (comp (ref "VD76") (value "BAS216") (footprint "BAS216") (libsource (lib "Schlib1") (part "Диод")))
    (comp (ref "VD77") (value "BAS216") (footprint "BAS216") (libsource (lib "Schlib1") (part "Диод")))
    (comp (ref "VD78") (value "BAS216") (footprint "BAS216") (libsource (lib "Schlib1") (part "Диод")))
    (comp (ref "VD79") (value "BAS216") (footprint "BAS216") (libsource (lib "Schlib1") (part "Диод")))
    (comp (ref "VD80") (value "BAS216") (footprint "BAS216") (libsource (lib "Schlib1") (part "Диод")))
    (comp (ref "VD81") (value "BAS216") (footprint "BAS216") (libsource (lib "Schlib1") (part "Диод")))
    (comp (ref "VD82") (value "BAS216") (footprint "BAS216") (libsource (lib "Schlib1") (part "Диод")))
    (comp (ref "VD83") (value "BAS216") (footprint "BAS216") (libsource (lib "Schlib1") (part "Диод")))
    (comp (ref "VD84") (value "BAS216") (footprint "BAS216") (libsource (lib "Schlib1") (part "Диод")))
    (comp (ref "VD85") (value "BAS216") (footprint "BAS216") (libsource (lib "Schlib1") (part "Диод")))
    (comp (ref "VD86") (value "BAS216") (footprint "BAS216") (libsource (lib "Schlib1") (part "Диод")))
    (comp (ref "VD87") (value "BAS216") (footprint "BAS216") (libsource (lib "Schlib1") (part "Диод")))
    (comp (ref "VD88") (value "BAS216") (footprint "BAS216") (libsource (lib "Schlib1") (part "Диод")))
    (comp (ref "VD89") (value "BAS216") (footprint "BAS216") (libsource (lib "Schlib1") (part "Диод")))
    (comp (ref "VD90") (value "BAS216") (footprint "BAS216") (libsource (lib "Schlib1") (part "Диод")))
    (comp (ref "VD91") (value "BAS216") (footprint "BAS216") (libsource (lib "Schlib1") (part "Диод")))
    (comp (ref "VD92") (value "BAS216") (footprint "BAS216") (libsource (lib "Schlib1") (part "Диод")))
    (comp (ref "VD93") (value "BAS216") (footprint "BAS216") (libsource (lib "Schlib1") (part "Диод")))
    (comp (ref "VD94") (value "BAS216") (footprint "BAS216") (libsource (lib "Schlib1") (part "Диод")))
    (comp (ref "VD95") (value "BAS216") (footprint "BAS216") (libsource (lib "Schlib1") (part "Диод")))
    (comp (ref "VD96") (value "BAS216") (footprint "BAS216") (libsource (lib "Schlib1") (part "Диод")))
    (comp (ref "VD97") (value "BAS216") (footprint "BAS216") (libsource (lib "Schlib1") (part "Диод")))
    (comp (ref "VD98") (value "BAS216") (footprint "BAS216") (libsource (lib "Schlib1") (part "Диод")))
    (comp (ref "VD99") (value "BAS216") (footprint "BAS216") (libsource (lib "Schlib1") (part "Диод")))
    (comp (ref "VD100") (value "BAS216") (footprint "BAS216") (libsource (lib "Schlib1") (part "Диод")))
    (comp (ref "VD101") (value "BAS216") (footprint "BAS216") (libsource (lib "Schlib1") (part "Диод")))
    (comp (ref "VD102") (value "BAS216") (footprint "BAS216") (libsource (lib "Schlib1") (part "Диод")))
    (comp (ref "VD103") (value "BAS216") (footprint "BAS216") (libsource (lib "Schlib1") (part "Диод")))
    (comp (ref "VD104") (value "BAS216") (footprint "BAS216") (libsource (lib "Schlib1") (part "Диод")))
    (comp (ref "VD105") (value "BAS216") (footprint "BAS216") (libsource (lib "Schlib1") (part "Диод")))
    (comp (ref "VD106") (value "BAS216") (footprint "BAS216") (libsource (lib "Schlib1") (part "Диод")))
    (comp (ref "VD107") (value "BAS216") (footprint "BAS216") (libsource (lib "Schlib1") (part "Диод")))
    (comp (ref "VD108") (value "BAS216") (footprint "BAS216") (libsource (lib "Schlib1") (part "Диод")))
    (comp (ref "VD109") (value "BAS216") (footprint "BAS216") (libsource (lib "Schlib1") (part "Диод")))
    (comp (ref "VD110") (value "BAS216") (footprint "BAS216") (libsource (lib "Schlib1") (part "Диод")))
    (comp (ref "VD111") (value "BAS216") (footprint "BAS216") (libsource (lib "Schlib1") (part "Диод")))
    (comp (ref "VD112") (value "BAS216") (footprint "BAS216") (libsource (lib "Schlib1") (part "Диод")))
    (comp (ref "VD113") (value "BAS216") (footprint "BAS216") (libsource (lib "Schlib1") (part "Диод")))
    (comp (ref "VD114") (value "BAS216") (footprint "BAS216") (libsource (lib "Schlib1") (part "Диод")))
    (comp (ref "VD115") (value "BAS216") (footprint "BAS216") (libsource (lib "Schlib1") (part "Диод")))
    (comp (ref "VD116") (value "BAS216") (footprint "BAS216") (libsource (lib "Schlib1") (part "Диод")))
    (comp (ref "VD117") (value "BAS216") (footprint "BAS216") (libsource (lib "Schlib1") (part "Диод")))
    (comp (ref "VD118") (value "BAS216") (footprint "BAS216") (libsource (lib "Schlib1") (part "Диод")))
    (comp (ref "VD119") (value "BAS216") (footprint "BAS216") (libsource (lib "Schlib1") (part "Диод")))
    (comp (ref "VD120") (value "BAS216") (footprint "BAS216") (libsource (lib "Schlib1") (part "Диод")))
    (comp (ref "VD121") (value "BAS216") (footprint "BAS216") (libsource (lib "Schlib1") (part "Диод")))
    (comp (ref "VD122") (value "BAS216") (footprint "BAS216") (libsource (lib "Schlib1") (part "Диод")))
    (comp (ref "VD123") (value "BAS216") (footprint "BAS216") (libsource (lib "Schlib1") (part "Диод")))
    (comp (ref "VD124") (value "BAS216") (footprint "BAS216") (libsource (lib "Schlib1") (part "Диод")))
    (comp (ref "VD125") (value "BAS216") (footprint "BAS216") (libsource (lib "Schlib1") (part "Диод")))
    (comp (ref "VD126") (value "BAS216") (footprint "BAS216") (libsource (lib "Schlib1") (part "Диод")))
    (comp (ref "VD127") (value "BAS216") (footprint "BAS216") (libsource (lib "Schlib1") (part "Диод")))
    (comp (ref "VD128") (value "BAS216") (footprint "BAS216") (libsource (lib "Schlib1") (part "Диод")))
    (comp (ref "VD129") (value "BAS216") (footprint "BAS216") (libsource (lib "Schlib1") (part "Диод")))
    (comp (ref "VD130") (value "BAS216") (footprint "BAS216") (libsource (lib "Schlib1") (part "Диод")))
    (comp (ref "VD131") (value "BAS216") (footprint "BAS216") (libsource (lib "Schlib1") (part "Диод")))
    (comp (ref "VD132") (value "BAS216") (footprint "BAS216") (libsource (lib "Schlib1") (part "Диод")))
    (comp (ref "VD133") (value "BAS216") (footprint "BAS216") (libsource (lib "Schlib1") (part "Диод")))
    (comp (ref "VD134") (value "BAS216") (footprint "BAS216") (libsource (lib "Schlib1") (part "Диод")))
    (comp (ref "VD135") (value "BAS216") (footprint "BAS216") (libsource (lib "Schlib1") (part "Диод")))
    (comp (ref "VD136") (value "BAS216") (footprint "BAS216") (libsource (lib "Schlib1") (part "Диод")))
    (comp (ref "VD137") (value "BAS216") (footprint "BAS216") (libsource (lib "Schlib1") (part "Диод")))
    (comp (ref "VD138") (value "BAS216") (footprint "BAS216") (libsource (lib "Schlib1") (part "Диод")))
    (comp (ref "VD139") (value "BAS216") (footprint "BAS216") (libsource (lib "Schlib1") (part "Диод")))
    (comp (ref "VD140") (value "BAS216") (footprint "BAS216") (libsource (lib "Schlib1") (part "Диод")))
    (comp (ref "VD141") (value "BAS216") (footprint "BAS216") (libsource (lib "Schlib1") (part "Диод")))
    (comp (ref "VD142") (value "BAS216") (footprint "BAS216") (libsource (lib "Schlib1") (part "Диод")))
    (comp (ref "VD143") (value "BAS216") (footprint "BAS216") (libsource (lib "Schlib1") (part "Диод")))
    (comp (ref "VD144") (value "BAS216") (footprint "BAS216") (libsource (lib "Schlib1") (part "Диод")))
    (comp (ref "VD145") (value "BAS216") (footprint "BAS216") (libsource (lib "Schlib1") (part "Диод")))
    (comp (ref "VD146") (value "BAS216") (footprint "BAS216") (libsource (lib "Schlib1") (part "Диод")))
    (comp (ref "VD147") (value "BAS216") (footprint "BAS216") (libsource (lib "Schlib1") (part "Диод")))
    (comp (ref "VD148") (value "BAS216") (footprint "BAS216") (libsource (lib "Schlib1") (part "Диод")))
    (comp (ref "VD149") (value "BAS216") (footprint "BAS216") (libsource (lib "Schlib1") (part "Диод")))
    (comp (ref "VD150") (value "BAS216") (footprint "BAS216") (libsource (lib "Schlib1") (part "Диод")))
    (comp (ref "VD151") (value "BAS216") (footprint "BAS216") (libsource (lib "Schlib1") (part "Диод")))
    (comp (ref "VD152") (value "BAS216") (footprint "BAS216") (libsource (lib "Schlib1") (part "Диод")))
    (comp (ref "VD153") (value "BAS216") (footprint "BAS216") (libsource (lib "Schlib1") (part "Диод")))
    (comp (ref "VD154") (value "BAS216") (footprint "BAS216") (libsource (lib "Schlib1") (part "Диод")))
    (comp (ref "VD155") (value "BAS216") (footprint "BAS216") (libsource (lib "Schlib1") (part "Диод")))
    (comp (ref "VD156") (value "BAS216") (footprint "BAS216") (libsource (lib "Schlib1") (part "Диод")))
    (comp (ref "VD157") (value "BAS216") (footprint "BAS216") (libsource (lib "Schlib1") (part "Диод")))
    (comp (ref "VD158") (value "BAS216") (footprint "BAS216") (libsource (lib "Schlib1") (part "Диод")))
    (comp (ref "VD159") (value "BAS216") (footprint "BAS216") (libsource (lib "Schlib1") (part "Диод")))
    (comp (ref "VD160") (value "BAS216") (footprint "BAS216") (libsource (lib "Schlib1") (part "Диод")))
    (comp (ref "VD161") (value "BAS216") (footprint "BAS216") (libsource (lib "Schlib1") (part "Диод")))
    (comp (ref "VD162") (value "BAS216") (footprint "BAS216") (libsource (lib "Schlib1") (part "Диод")))
    (comp (ref "VD163") (value "BAS216") (footprint "BAS216") (libsource (lib "Schlib1") (part "Диод")))
    (comp (ref "VD164") (value "BAS216") (footprint "BAS216") (libsource (lib "Schlib1") (part "Диод")))
    (comp (ref "VD165") (value "BAS216") (footprint "BAS216") (libsource (lib "Schlib1") (part "Диод")))
    (comp (ref "VD166") (value "BAS216") (footprint "BAS216") (libsource (lib "Schlib1") (part "Диод")))
    (comp (ref "VD167") (value "BAS216") (footprint "BAS216") (libsource (lib "Schlib1") (part "Диод")))
    (comp (ref "VD168") (value "BAS216") (footprint "BAS216") (libsource (lib "Schlib1") (part "Диод")))
    (comp (ref "VD169") (value "BAS216") (footprint "BAS216") (libsource (lib "Schlib1") (part "Диод")))
    (comp (ref "VD170") (value "BAS216") (footprint "BAS216") (libsource (lib "Schlib1") (part "Диод")))
    (comp (ref "VD171") (value "BAS216") (footprint "BAS216") (libsource (lib "Schlib1") (part "Диод")))
    (comp (ref "VD172") (value "BAS216") (footprint "BAS216") (libsource (lib "Schlib1") (part "Диод")))
    (comp (ref "VD173") (value "BAS216") (footprint "BAS216") (libsource (lib "Schlib1") (part "Диод")))
    (comp (ref "VD174") (value "BAS216") (footprint "BAS216") (libsource (lib "Schlib1") (part "Диод")))
    (comp (ref "VD175") (value "BAS216") (footprint "BAS216") (libsource (lib "Schlib1") (part "Диод")))
    (comp (ref "VD176") (value "BAS216") (footprint "BAS216") (libsource (lib "Schlib1") (part "Диод")))
    (comp (ref "VD177") (value "BAS216") (footprint "BAS216") (libsource (lib "Schlib1") (part "Диод")))
    (comp (ref "VD178") (value "BAS216") (footprint "BAS216") (libsource (lib "Schlib1") (part "Диод")))
    (comp (ref "VD179") (value "BAS216") (footprint "BAS216") (libsource (lib "Schlib1") (part "Диод")))
    (comp (ref "VD180") (value "BAS216") (footprint "BAS216") (libsource (lib "Schlib1") (part "Диод")))
    (comp (ref "VD181") (value "BAS216") (footprint "BAS216") (libsource (lib "Schlib1") (part "Диод")))
    (comp (ref "VD182") (value "BAS216") (footprint "BAS216") (libsource (lib "Schlib1") (part "Диод")))
    (comp (ref "VD183") (value "BAS216") (footprint "BAS216") (libsource (lib "Schlib1") (part "Диод")))
    (comp (ref "VD184") (value "BAS216") (footprint "BAS216") (libsource (lib "Schlib1") (part "Диод")))
    (comp (ref "VD185") (value "BAS216") (footprint "BAS216") (libsource (lib "Schlib1") (part "Диод")))
    (comp (ref "VD186") (value "BAS216") (footprint "BAS216") (libsource (lib "Schlib1") (part "Диод")))
    (comp (ref "VD187") (value "BAS216") (footprint "BAS216") (libsource (lib "Schlib1") (part "Диод")))
    (comp (ref "VD188") (value "BAS216") (footprint "BAS216") (libsource (lib "Schlib1") (part "Диод")))
    (comp (ref "VD189") (value "BAS216") (footprint "BAS216") (libsource (lib "Schlib1") (part "Диод")))
    (comp (ref "VD190") (value "BAS216") (footprint "BAS216") (libsource (lib "Schlib1") (part "Диод")))
    (comp (ref "VD191") (value "BAS216") (footprint "BAS216") (libsource (lib "Schlib1") (part "Диод")))
    (comp (ref "VD192") (value "BAS216") (footprint "BAS216") (libsource (lib "Schlib1") (part "Диод")))
  )
  (nets
    (net (code "186") (name "/5V (Dirty)") (class "Default")
      (node (ref "D0") (pin "16") (pinfunction "Vdd_16") (pintype "passive"))
      (node (ref "D1") (pin "16") (pinfunction "Vdd_16") (pintype "passive"))
      (node (ref "D10") (pin "16") (pinfunction "Vdd_16") (pintype "passive"))
      (node (ref "D11") (pin "16") (pinfunction "Vdd_16") (pintype "passive"))
      (node (ref "D12") (pin "16") (pinfunction "Vdd_16") (pintype "passive"))
      (node (ref "D13") (pin "16") (pinfunction "Vdd_16") (pintype "passive"))
      (node (ref "D14") (pin "16") (pinfunction "Vdd_16") (pintype "passive"))
      (node (ref "D15") (pin "16") (pinfunction "Vdd_16") (pintype "passive"))
      (node (ref "D16") (pin "16") (pinfunction "Vdd_16") (pintype "passive"))
      (node (ref "D17") (pin "16") (pinfunction "Vdd_16") (pintype "passive"))
      (node (ref "D18") (pin "16") (pinfunction "Vdd_16") (pintype "passive"))
      (node (ref "D19") (pin "16") (pinfunction "Vdd_16") (pintype "passive"))
      (node (ref "D2") (pin "16") (pinfunction "Vdd_16") (pintype "passive"))
      (node (ref "D20") (pin "16") (pinfunction "Vdd_16") (pintype "passive"))
      (node (ref "D21") (pin "16") (pinfunction "Vdd_16") (pintype "passive"))
      (node (ref "D22") (pin "16") (pinfunction "Vdd_16") (pintype "passive"))
      (node (ref "D23") (pin "16") (pinfunction "Vdd_16") (pintype "passive"))
      (node (ref "D3") (pin "16") (pinfunction "Vdd_16") (pintype "passive"))
      (node (ref "D4") (pin "16") (pinfunction "Vdd_16") (pintype "passive"))
      (node (ref "D5") (pin "16") (pinfunction "Vdd_16") (pintype "passive"))
      (node (ref "D6") (pin "16") (pinfunction "Vdd_16") (pintype "passive"))
      (node (ref "D7") (pin "16") (pinfunction "Vdd_16") (pintype "passive"))
      (node (ref "D8") (pin "16") (pinfunction "Vdd_16") (pintype "passive"))
      (node (ref "D9") (pin "16") (pinfunction "Vdd_16") (pintype "passive"))
      (node (ref "PLD1") (pin "9") (pinfunction "9_9") (pintype "passive"))
      (node (ref "VD1") (pin "K") (pinfunction "Katod_K") (pintype "passive"))
      (node (ref "VD10") (pin "K") (pinfunction "Katod_K") (pintype "passive"))
      (node (ref "VD100") (pin "K") (pinfunction "Katod_K") (pintype "passive"))
      (node (ref "VD101") (pin "K") (pinfunction "Katod_K") (pintype "passive"))
      (node (ref "VD102") (pin "K") (pinfunction "Katod_K") (pintype "passive"))
      (node (ref "VD103") (pin "K") (pinfunction "Katod_K") (pintype "passive"))
      (node (ref "VD104") (pin "K") (pinfunction "Katod_K") (pintype "passive"))
      (node (ref "VD105") (pin "K") (pinfunction "Katod_K") (pintype "passive"))
      (node (ref "VD106") (pin "K") (pinfunction "Katod_K") (pintype "passive"))
      (node (ref "VD107") (pin "K") (pinfunction "Katod_K") (pintype "passive"))
      (node (ref "VD108") (pin "K") (pinfunction "Katod_K") (pintype "passive"))
      (node (ref "VD109") (pin "K") (pinfunction "Katod_K") (pintype "passive"))
      (node (ref "VD11") (pin "K") (pinfunction "Katod_K") (pintype "passive"))
      (node (ref "VD110") (pin "K") (pinfunction "Katod_K") (pintype "passive"))
      (node (ref "VD111") (pin "K") (pinfunction "Katod_K") (pintype "passive"))
      (node (ref "VD112") (pin "K") (pinfunction "Katod_K") (pintype "passive"))
      (node (ref "VD113") (pin "K") (pinfunction "Katod_K") (pintype "passive"))
      (node (ref "VD114") (pin "K") (pinfunction "Katod_K") (pintype "passive"))
      (node (ref "VD115") (pin "K") (pinfunction "Katod_K") (pintype "passive"))
      (node (ref "VD116") (pin "K") (pinfunction "Katod_K") (pintype "passive"))
      (node (ref "VD117") (pin "K") (pinfunction "Katod_K") (pintype "passive"))
      (node (ref "VD118") (pin "K") (pinfunction "Katod_K") (pintype "passive"))
      (node (ref "VD119") (pin "K") (pinfunction "Katod_K") (pintype "passive"))
      (node (ref "VD12") (pin "K") (pinfunction "Katod_K") (pintype "passive"))
      (node (ref "VD120") (pin "K") (pinfunction "Katod_K") (pintype "passive"))
      (node (ref "VD121") (pin "K") (pinfunction "Katod_K") (pintype "passive"))
      (node (ref "VD122") (pin "K") (pinfunction "Katod_K") (pintype "passive"))
      (node (ref "VD123") (pin "K") (pinfunction "Katod_K") (pintype "passive"))
      (node (ref "VD124") (pin "K") (pinfunction "Katod_K") (pintype "passive"))
      (node (ref "VD125") (pin "K") (pinfunction "Katod_K") (pintype "passive"))
      (node (ref "VD126") (pin "K") (pinfunction "Katod_K") (pintype "passive"))
      (node (ref "VD127") (pin "K") (pinfunction "Katod_K") (pintype "passive"))
      (node (ref "VD128") (pin "K") (pinfunction "Katod_K") (pintype "passive"))
      (node (ref "VD129") (pin "K") (pinfunction "Katod_K") (pintype "passive"))
      (node (ref "VD13") (pin "K") (pinfunction "Katod_K") (pintype "passive"))
      (node (ref "VD130") (pin "K") (pinfunction "Katod_K") (pintype "passive"))
      (node (ref "VD131") (pin "K") (pinfunction "Katod_K") (pintype "passive"))
      (node (ref "VD132") (pin "K") (pinfunction "Katod_K") (pintype "passive"))
      (node (ref "VD133") (pin "K") (pinfunction "Katod_K") (pintype "passive"))
      (node (ref "VD134") (pin "K") (pinfunction "Katod_K") (pintype "passive"))
      (node (ref "VD135") (pin "K") (pinfunction "Katod_K") (pintype "passive"))
      (node (ref "VD136") (pin "K") (pinfunction "Katod_K") (pintype "passive"))
      (node (ref "VD137") (pin "K") (pinfunction "Katod_K") (pintype "passive"))
      (node (ref "VD138") (pin "K") (pinfunction "Katod_K") (pintype "passive"))
      (node (ref "VD139") (pin "K") (pinfunction "Katod_K") (pintype "passive"))
      (node (ref "VD14") (pin "K") (pinfunction "Katod_K") (pintype "passive"))
      (node (ref "VD140") (pin "K") (pinfunction "Katod_K") (pintype "passive"))
      (node (ref "VD141") (pin "K") (pinfunction "Katod_K") (pintype "passive"))
      (node (ref "VD142") (pin "K") (pinfunction "Katod_K") (pintype "passive"))
      (node (ref "VD143") (pin "K") (pinfunction "Katod_K") (pintype "passive"))
      (node (ref "VD144") (pin "K") (pinfunction "Katod_K") (pintype "passive"))
      (node (ref "VD145") (pin "K") (pinfunction "Katod_K") (pintype "passive"))
      (node (ref "VD146") (pin "K") (pinfunction "Katod_K") (pintype "passive"))
      (node (ref "VD147") (pin "K") (pinfunction "Katod_K") (pintype "passive"))
      (node (ref "VD148") (pin "K") (pinfunction "Katod_K") (pintype "passive"))
      (node (ref "VD149") (pin "K") (pinfunction "Katod_K") (pintype "passive"))
      (node (ref "VD15") (pin "K") (pinfunction "Katod_K") (pintype "passive"))
      (node (ref "VD150") (pin "K") (pinfunction "Katod_K") (pintype "passive"))
      (node (ref "VD151") (pin "K") (pinfunction "Katod_K") (pintype "passive"))
      (node (ref "VD152") (pin "K") (pinfunction "Katod_K") (pintype "passive"))
      (node (ref "VD153") (pin "K") (pinfunction "Katod_K") (pintype "passive"))
      (node (ref "VD154") (pin "K") (pinfunction "Katod_K") (pintype "passive"))
      (node (ref "VD155") (pin "K") (pinfunction "Katod_K") (pintype "passive"))
      (node (ref "VD156") (pin "K") (pinfunction "Katod_K") (pintype "passive"))
      (node (ref "VD157") (pin "K") (pinfunction "Katod_K") (pintype "passive"))
      (node (ref "VD158") (pin "K") (pinfunction "Katod_K") (pintype "passive"))
      (node (ref "VD159") (pin "K") (pinfunction "Katod_K") (pintype "passive"))
      (node (ref "VD16") (pin "K") (pinfunction "Katod_K") (pintype "passive"))
      (node (ref "VD160") (pin "K") (pinfunction "Katod_K") (pintype "passive"))
      (node (ref "VD161") (pin "K") (pinfunction "Katod_K") (pintype "passive"))
      (node (ref "VD162") (pin "K") (pinfunction "Katod_K") (pintype "passive"))
      (node (ref "VD163") (pin "K") (pinfunction "Katod_K") (pintype "passive"))
      (node (ref "VD164") (pin "K") (pinfunction "Katod_K") (pintype "passive"))
      (node (ref "VD165") (pin "K") (pinfunction "Katod_K") (pintype "passive"))
      (node (ref "VD166") (pin "K") (pinfunction "Katod_K") (pintype "passive"))
      (node (ref "VD167") (pin "K") (pinfunction "Katod_K") (pintype "passive"))
      (node (ref "VD168") (pin "K") (pinfunction "Katod_K") (pintype "passive"))
      (node (ref "VD169") (pin "K") (pinfunction "Katod_K") (pintype "passive"))
      (node (ref "VD17") (pin "K") (pinfunction "Katod_K") (pintype "passive"))
      (node (ref "VD170") (pin "K") (pinfunction "Katod_K") (pintype "passive"))
      (node (ref "VD171") (pin "K") (pinfunction "Katod_K") (pintype "passive"))
      (node (ref "VD172") (pin "K") (pinfunction "Katod_K") (pintype "passive"))
      (node (ref "VD173") (pin "K") (pinfunction "Katod_K") (pintype "passive"))
      (node (ref "VD174") (pin "K") (pinfunction "Katod_K") (pintype "passive"))
      (node (ref "VD175") (pin "K") (pinfunction "Katod_K") (pintype "passive"))
      (node (ref "VD176") (pin "K") (pinfunction "Katod_K") (pintype "passive"))
      (node (ref "VD177") (pin "K") (pinfunction "Katod_K") (pintype "passive"))
      (node (ref "VD178") (pin "K") (pinfunction "Katod_K") (pintype "passive"))
      (node (ref "VD179") (pin "K") (pinfunction "Katod_K") (pintype "passive"))
      (node (ref "VD18") (pin "K") (pinfunction "Katod_K") (pintype "passive"))
      (node (ref "VD180") (pin "K") (pinfunction "Katod_K") (pintype "passive"))
      (node (ref "VD181") (pin "K") (pinfunction "Katod_K") (pintype "passive"))
      (node (ref "VD182") (pin "K") (pinfunction "Katod_K") (pintype "passive"))
      (node (ref "VD183") (pin "K") (pinfunction "Katod_K") (pintype "passive"))
      (node (ref "VD184") (pin "K") (pinfunction "Katod_K") (pintype "passive"))
      (node (ref "VD185") (pin "K") (pinfunction "Katod_K") (pintype "passive"))
      (node (ref "VD186") (pin "K") (pinfunction "Katod_K") (pintype "passive"))
      (node (ref "VD187") (pin "K") (pinfunction "Katod_K") (pintype "passive"))
      (node (ref "VD188") (pin "K") (pinfunction "Katod_K") (pintype "passive"))
      (node (ref "VD189") (pin "K") (pinfunction "Katod_K") (pintype "passive"))
      (node (ref "VD19") (pin "K") (pinfunction "Katod_K") (pintype "passive"))
      (node (ref "VD190") (pin "K") (pinfunction "Katod_K") (pintype "passive"))
      (node (ref "VD191") (pin "K") (pinfunction "Katod_K") (pintype "passive"))
      (node (ref "VD192") (pin "K") (pinfunction "Katod_K") (pintype "passive"))
      (node (ref "VD2") (pin "K") (pinfunction "Katod_K") (pintype "passive"))
      (node (ref "VD20") (pin "K") (pinfunction "Katod_K") (pintype "passive"))
      (node (ref "VD21") (pin "K") (pinfunction "Katod_K") (pintype "passive"))
      (node (ref "VD22") (pin "K") (pinfunction "Katod_K") (pintype "passive"))
      (node (ref "VD23") (pin "K") (pinfunction "Katod_K") (pintype "passive"))
      (node (ref "VD24") (pin "K") (pinfunction "Katod_K") (pintype "passive"))
      (node (ref "VD25") (pin "K") (pinfunction "Katod_K") (pintype "passive"))
      (node (ref "VD26") (pin "K") (pinfunction "Katod_K") (pintype "passive"))
      (node (ref "VD27") (pin "K") (pinfunction "Katod_K") (pintype "passive"))
      (node (ref "VD28") (pin "K") (pinfunction "Katod_K") (pintype "passive"))
      (node (ref "VD29") (pin "K") (pinfunction "Katod_K") (pintype "passive"))
      (node (ref "VD3") (pin "K") (pinfunction "Katod_K") (pintype "passive"))
      (node (ref "VD30") (pin "K") (pinfunction "Katod_K") (pintype "passive"))
      (node (ref "VD31") (pin "K") (pinfunction "Katod_K") (pintype "passive"))
      (node (ref "VD32") (pin "K") (pinfunction "Katod_K") (pintype "passive"))
      (node (ref "VD33") (pin "K") (pinfunction "Katod_K") (pintype "passive"))
      (node (ref "VD34") (pin "K") (pinfunction "Katod_K") (pintype "passive"))
      (node (ref "VD35") (pin "K") (pinfunction "Katod_K") (pintype "passive"))
      (node (ref "VD36") (pin "K") (pinfunction "Katod_K") (pintype "passive"))
      (node (ref "VD37") (pin "K") (pinfunction "Katod_K") (pintype "passive"))
      (node (ref "VD38") (pin "K") (pinfunction "Katod_K") (pintype "passive"))
      (node (ref "VD39") (pin "K") (pinfunction "Katod_K") (pintype "passive"))
      (node (ref "VD4") (pin "K") (pinfunction "Katod_K") (pintype "passive"))
      (node (ref "VD40") (pin "K") (pinfunction "Katod_K") (pintype "passive"))
      (node (ref "VD41") (pin "K") (pinfunction "Katod_K") (pintype "passive"))
      (node (ref "VD42") (pin "K") (pinfunction "Katod_K") (pintype "passive"))
      (node (ref "VD43") (pin "K") (pinfunction "Katod_K") (pintype "passive"))
      (node (ref "VD44") (pin "K") (pinfunction "Katod_K") (pintype "passive"))
      (node (ref "VD45") (pin "K") (pinfunction "Katod_K") (pintype "passive"))
      (node (ref "VD46") (pin "K") (pinfunction "Katod_K") (pintype "passive"))
      (node (ref "VD47") (pin "K") (pinfunction "Katod_K") (pintype "passive"))
      (node (ref "VD48") (pin "K") (pinfunction "Katod_K") (pintype "passive"))
      (node (ref "VD49") (pin "K") (pinfunction "Katod_K") (pintype "passive"))
      (node (ref "VD5") (pin "K") (pinfunction "Katod_K") (pintype "passive"))
      (node (ref "VD50") (pin "K") (pinfunction "Katod_K") (pintype "passive"))
      (node (ref "VD51") (pin "K") (pinfunction "Katod_K") (pintype "passive"))
      (node (ref "VD52") (pin "K") (pinfunction "Katod_K") (pintype "passive"))
      (node (ref "VD53") (pin "K") (pinfunction "Katod_K") (pintype "passive"))
      (node (ref "VD54") (pin "K") (pinfunction "Katod_K") (pintype "passive"))
      (node (ref "VD55") (pin "K") (pinfunction "Katod_K") (pintype "passive"))
      (node (ref "VD56") (pin "K") (pinfunction "Katod_K") (pintype "passive"))
      (node (ref "VD57") (pin "K") (pinfunction "Katod_K") (pintype "passive"))
      (node (ref "VD58") (pin "K") (pinfunction "Katod_K") (pintype "passive"))
      (node (ref "VD59") (pin "K") (pinfunction "Katod_K") (pintype "passive"))
      (node (ref "VD6") (pin "K") (pinfunction "Katod_K") (pintype "passive"))
      (node (ref "VD60") (pin "K") (pinfunction "Katod_K") (pintype "passive"))
      (node (ref "VD61") (pin "K") (pinfunction "Katod_K") (pintype "passive"))
      (node (ref "VD62") (pin "K") (pinfunction "Katod_K") (pintype "passive"))
      (node (ref "VD63") (pin "K") (pinfunction "Katod_K") (pintype "passive"))
      (node (ref "VD64") (pin "K") (pinfunction "Katod_K") (pintype "passive"))
      (node (ref "VD65") (pin "K") (pinfunction "Katod_K") (pintype "passive"))
      (node (ref "VD66") (pin "K") (pinfunction "Katod_K") (pintype "passive"))
      (node (ref "VD67") (pin "K") (pinfunction "Katod_K") (pintype "passive"))
      (node (ref "VD68") (pin "K") (pinfunction "Katod_K") (pintype "passive"))
      (node (ref "VD69") (pin "K") (pinfunction "Katod_K") (pintype "passive"))
      (node (ref "VD7") (pin "K") (pinfunction "Katod_K") (pintype "passive"))
      (node (ref "VD70") (pin "K") (pinfunction "Katod_K") (pintype "passive"))
      (node (ref "VD71") (pin "K") (pinfunction "Katod_K") (pintype "passive"))
      (node (ref "VD72") (pin "K") (pinfunction "Katod_K") (pintype "passive"))
      (node (ref "VD73") (pin "K") (pinfunction "Katod_K") (pintype "passive"))
      (node (ref "VD74") (pin "K") (pinfunction "Katod_K") (pintype "passive"))
      (node (ref "VD75") (pin "K") (pinfunction "Katod_K") (pintype "passive"))
      (node (ref "VD76") (pin "K") (pinfunction "Katod_K") (pintype "passive"))
      (node (ref "VD77") (pin "K") (pinfunction "Katod_K") (pintype "passive"))
      (node (ref "VD78") (pin "K") (pinfunction "Katod_K") (pintype "passive"))
      (node (ref "VD79") (pin "K") (pinfunction "Katod_K") (pintype "passive"))
      (node (ref "VD8") (pin "K") (pinfunction "Katod_K") (pintype "passive"))
      (node (ref "VD80") (pin "K") (pinfunction "Katod_K") (pintype "passive"))
      (node (ref "VD81") (pin "K") (pinfunction "Katod_K") (pintype "passive"))
      (node (ref "VD82") (pin "K") (pinfunction "Katod_K") (pintype "passive"))
      (node (ref "VD83") (pin "K") (pinfunction "Katod_K") (pintype "passive"))
      (node (ref "VD84") (pin "K") (pinfunction "Katod_K") (pintype "passive"))
      (node (ref "VD85") (pin "K") (pinfunction "Katod_K") (pintype "passive"))
      (node (ref "VD86") (pin "K") (pinfunction "Katod_K") (pintype "passive"))
      (node (ref "VD87") (pin "K") (pinfunction "Katod_K") (pintype "passive"))
      (node (ref "VD88") (pin "K") (pinfunction "Katod_K") (pintype "passive"))
      (node (ref "VD89") (pin "K") (pinfunction "Katod_K") (pintype "passive"))
      (node (ref "VD9") (pin "K") (pinfunction "Katod_K") (pintype "passive"))
      (node (ref "VD90") (pin "K") (pinfunction "Katod_K") (pintype "passive"))
      (node (ref "VD91") (pin "K") (pinfunction "Katod_K") (pintype "passive"))
      (node (ref "VD92") (pin "K") (pinfunction "Katod_K") (pintype "passive"))
      (node (ref "VD93") (pin "K") (pinfunction "Katod_K") (pintype "passive"))
      (node (ref "VD94") (pin "K") (pinfunction "Katod_K") (pintype "passive"))
      (node (ref "VD95") (pin "K") (pinfunction "Katod_K") (pintype "passive"))
      (node (ref "VD96") (pin "K") (pinfunction "Katod_K") (pintype "passive"))
      (node (ref "VD97") (pin "K") (pinfunction "Katod_K") (pintype "passive"))
      (node (ref "VD98") (pin "K") (pinfunction "Katod_K") (pintype "passive"))
      (node (ref "VD99") (pin "K") (pinfunction "Katod_K") (pintype "passive"))
    )
    (net (code "187") (name "/CP") (class "Default")
      (node (ref "D0") (pin "3") (pinfunction "CP_3") (pintype "passive"))
      (node (ref "D1") (pin "3") (pinfunction "CP_3") (pintype "passive"))
      (node (ref "D10") (pin "3") (pinfunction "CP_3") (pintype "passive"))
      (node (ref "D11") (pin "3") (pinfunction "CP_3") (pintype "passive"))
      (node (ref "D12") (pin "3") (pinfunction "CP_3") (pintype "passive"))
      (node (ref "D13") (pin "3") (pinfunction "CP_3") (pintype "passive"))
      (node (ref "D14") (pin "3") (pinfunction "CP_3") (pintype "passive"))
      (node (ref "D15") (pin "3") (pinfunction "CP_3") (pintype "passive"))
      (node (ref "D16") (pin "3") (pinfunction "CP_3") (pintype "passive"))
      (node (ref "D17") (pin "3") (pinfunction "CP_3") (pintype "passive"))
      (node (ref "D18") (pin "3") (pinfunction "CP_3") (pintype "passive"))
      (node (ref "D19") (pin "3") (pinfunction "CP_3") (pintype "passive"))
      (node (ref "D2") (pin "3") (pinfunction "CP_3") (pintype "passive"))
      (node (ref "D20") (pin "3") (pinfunction "CP_3") (pintype "passive"))
      (node (ref "D21") (pin "3") (pinfunction "CP_3") (pintype "passive"))
      (node (ref "D22") (pin "3") (pinfunction "CP_3") (pintype "passive"))
      (node (ref "D23") (pin "3") (pinfunction "CP_3") (pintype "passive"))
      (node (ref "D3") (pin "3") (pinfunction "CP_3") (pintype "passive"))
      (node (ref "D4") (pin "3") (pinfunction "CP_3") (pintype "passive"))
      (node (ref "D5") (pin "3") (pinfunction "CP_3") (pintype "passive"))
      (node (ref "D6") (pin "3") (pinfunction "CP_3") (pintype "passive"))
      (node (ref "D7") (pin "3") (pinfunction "CP_3") (pintype "passive"))
      (node (ref "D8") (pin "3") (pinfunction "CP_3") (pintype "passive"))
      (node (ref "D9") (pin "3") (pinfunction "CP_3") (pintype "passive"))
      (node (ref "PLD1") (pin "2") (pinfunction "2_2") (pintype "passive"))
    )
    (net (code "188") (name "/D0-0") (class "Default")
      (node (ref "D0") (pin "4") (pinfunction "QP0_4") (pintype "passive"))
      (node (ref "K4") (pin "3") (pinfunction "3_3") (pintype "passive"))
      (node (ref "VD1") (pin "A") (pinfunction "Anod_A") (pintype "passive"))
    )
    (net (code "189") (name "/D0-1") (class "Default")
      (node (ref "D0") (pin "5") (pinfunction "QP1_5") (pintype "passive"))
      (node (ref "K8") (pin "3") (pinfunction "3_3") (pintype "passive"))
      (node (ref "VD2") (pin "A") (pinfunction "Anod_A") (pintype "passive"))
    )
    (net (code "190") (name "/D0-2") (class "Default")
      (node (ref "D0") (pin "6") (pinfunction "QP2_6") (pintype "passive"))
      (node (ref "K3") (pin "3") (pinfunction "3_3") (pintype "passive"))
      (node (ref "VD3") (pin "A") (pinfunction "Anod_A") (pintype "passive"))
    )
    (net (code "191") (name "/D0-3") (class "Default")
      (node (ref "D0") (pin "7") (pinfunction "QP3_7") (pintype "passive"))
      (node (ref "K7") (pin "3") (pinfunction "3_3") (pintype "passive"))
      (node (ref "VD4") (pin "A") (pinfunction "Anod_A") (pintype "passive"))
    )
    (net (code "192") (name "/D0-4") (class "Default")
      (node (ref "D0") (pin "14") (pinfunction "QP4_14") (pintype "passive"))
      (node (ref "K2") (pin "3") (pinfunction "3_3") (pintype "passive"))
      (node (ref "VD5") (pin "A") (pinfunction "Anod_A") (pintype "passive"))
    )
    (net (code "193") (name "/D0-5") (class "Default")
      (node (ref "D0") (pin "13") (pinfunction "QP5_13") (pintype "passive"))
      (node (ref "K6") (pin "3") (pinfunction "3_3") (pintype "passive"))
      (node (ref "VD6") (pin "A") (pinfunction "Anod_A") (pintype "passive"))
    )
    (net (code "194") (name "/D0-6") (class "Default")
      (node (ref "D0") (pin "12") (pinfunction "QP6_12") (pintype "passive"))
      (node (ref "K1") (pin "3") (pinfunction "3_3") (pintype "passive"))
      (node (ref "VD7") (pin "A") (pinfunction "Anod_A") (pintype "passive"))
    )
    (net (code "195") (name "/D0-7") (class "Default")
      (node (ref "D0") (pin "11") (pinfunction "QP7_11") (pintype "passive"))
      (node (ref "K5") (pin "3") (pinfunction "3_3") (pintype "passive"))
      (node (ref "VD8") (pin "A") (pinfunction "Anod_A") (pintype "passive"))
    )
    (net (code "197") (name "/D1-0") (class "Default")
      (node (ref "D1") (pin "4") (pinfunction "QP0_4") (pintype "passive"))
      (node (ref "K12") (pin "3") (pinfunction "3_3") (pintype "passive"))
      (node (ref "VD9") (pin "A") (pinfunction "Anod_A") (pintype "passive"))
    )
    (net (code "198") (name "/D1-1") (class "Default")
      (node (ref "D1") (pin "5") (pinfunction "QP1_5") (pintype "passive"))
      (node (ref "K20") (pin "3") (pinfunction "3_3") (pintype "passive"))
      (node (ref "VD10") (pin "A") (pinfunction "Anod_A") (pintype "passive"))
    )
    (net (code "199") (name "/D1-2") (class "Default")
      (node (ref "D1") (pin "6") (pinfunction "QP2_6") (pintype "passive"))
      (node (ref "K11") (pin "3") (pinfunction "3_3") (pintype "passive"))
      (node (ref "VD11") (pin "A") (pinfunction "Anod_A") (pintype "passive"))
    )
    (net (code "200") (name "/D1-3") (class "Default")
      (node (ref "D1") (pin "7") (pinfunction "QP3_7") (pintype "passive"))
      (node (ref "K19") (pin "3") (pinfunction "3_3") (pintype "passive"))
      (node (ref "VD12") (pin "A") (pinfunction "Anod_A") (pintype "passive"))
    )
    (net (code "201") (name "/D1-4") (class "Default")
      (node (ref "D1") (pin "14") (pinfunction "QP4_14") (pintype "passive"))
      (node (ref "K10") (pin "3") (pinfunction "3_3") (pintype "passive"))
      (node (ref "VD13") (pin "A") (pinfunction "Anod_A") (pintype "passive"))
    )
    (net (code "202") (name "/D1-5") (class "Default")
      (node (ref "D1") (pin "13") (pinfunction "QP5_13") (pintype "passive"))
      (node (ref "K18") (pin "3") (pinfunction "3_3") (pintype "passive"))
      (node (ref "VD14") (pin "A") (pinfunction "Anod_A") (pintype "passive"))
    )
    (net (code "203") (name "/D1-6") (class "Default")
      (node (ref "D1") (pin "12") (pinfunction "QP6_12") (pintype "passive"))
      (node (ref "K9") (pin "3") (pinfunction "3_3") (pintype "passive"))
      (node (ref "VD15") (pin "A") (pinfunction "Anod_A") (pintype "passive"))
    )
    (net (code "204") (name "/D1-7") (class "Default")
      (node (ref "D1") (pin "11") (pinfunction "QP7_11") (pintype "passive"))
      (node (ref "K17") (pin "3") (pinfunction "3_3") (pintype "passive"))
      (node (ref "VD16") (pin "A") (pinfunction "Anod_A") (pintype "passive"))
    )
    (net (code "206") (name "/D2-0") (class "Default")
      (node (ref "D2") (pin "4") (pinfunction "QP0_4") (pintype "passive"))
      (node (ref "K16") (pin "3") (pinfunction "3_3") (pintype "passive"))
      (node (ref "VD17") (pin "A") (pinfunction "Anod_A") (pintype "passive"))
    )
    (net (code "207") (name "/D2-1") (class "Default")
      (node (ref "D2") (pin "5") (pinfunction "QP1_5") (pintype "passive"))
      (node (ref "K24") (pin "3") (pinfunction "3_3") (pintype "passive"))
      (node (ref "VD18") (pin "A") (pinfunction "Anod_A") (pintype "passive"))
    )
    (net (code "208") (name "/D2-2") (class "Default")
      (node (ref "D2") (pin "6") (pinfunction "QP2_6") (pintype "passive"))
      (node (ref "K15") (pin "3") (pinfunction "3_3") (pintype "passive"))
      (node (ref "VD19") (pin "A") (pinfunction "Anod_A") (pintype "passive"))
    )
    (net (code "209") (name "/D2-3") (class "Default")
      (node (ref "D2") (pin "7") (pinfunction "QP3_7") (pintype "passive"))
      (node (ref "K23") (pin "3") (pinfunction "3_3") (pintype "passive"))
      (node (ref "VD20") (pin "A") (pinfunction "Anod_A") (pintype "passive"))
    )
    (net (code "210") (name "/D2-4") (class "Default")
      (node (ref "D2") (pin "14") (pinfunction "QP4_14") (pintype "passive"))
      (node (ref "K14") (pin "3") (pinfunction "3_3") (pintype "passive"))
      (node (ref "VD21") (pin "A") (pinfunction "Anod_A") (pintype "passive"))
    )
    (net (code "211") (name "/D2-5") (class "Default")
      (node (ref "D2") (pin "13") (pinfunction "QP5_13") (pintype "passive"))
      (node (ref "K22") (pin "3") (pinfunction "3_3") (pintype "passive"))
      (node (ref "VD22") (pin "A") (pinfunction "Anod_A") (pintype "passive"))
    )
    (net (code "212") (name "/D2-6") (class "Default")
      (node (ref "D2") (pin "12") (pinfunction "QP6_12") (pintype "passive"))
      (node (ref "K13") (pin "3") (pinfunction "3_3") (pintype "passive"))
      (node (ref "VD23") (pin "A") (pinfunction "Anod_A") (pintype "passive"))
    )
    (net (code "213") (name "/D2-7") (class "Default")
      (node (ref "D2") (pin "11") (pinfunction "QP7_11") (pintype "passive"))
      (node (ref "K21") (pin "3") (pinfunction "3_3") (pintype "passive"))
      (node (ref "VD24") (pin "A") (pinfunction "Anod_A") (pintype "passive"))
    )
    (net (code "215") (name "/D3-0") (class "Default")
      (node (ref "D3") (pin "4") (pinfunction "QP0_4") (pintype "passive"))
      (node (ref "K28") (pin "3") (pinfunction "3_3") (pintype "passive"))
      (node (ref "VD25") (pin "A") (pinfunction "Anod_A") (pintype "passive"))
    )
    (net (code "216") (name "/D3-1") (class "Default")
      (node (ref "D3") (pin "5") (pinfunction "QP1_5") (pintype "passive"))
      (node (ref "K36") (pin "3") (pinfunction "3_3") (pintype "passive"))
      (node (ref "VD26") (pin "A") (pinfunction "Anod_A") (pintype "passive"))
    )
    (net (code "217") (name "/D3-2") (class "Default")
      (node (ref "D3") (pin "6") (pinfunction "QP2_6") (pintype "passive"))
      (node (ref "K27") (pin "3") (pinfunction "3_3") (pintype "passive"))
      (node (ref "VD27") (pin "A") (pinfunction "Anod_A") (pintype "passive"))
    )
    (net (code "218") (name "/D3-3") (class "Default")
      (node (ref "D3") (pin "7") (pinfunction "QP3_7") (pintype "passive"))
      (node (ref "K35") (pin "3") (pinfunction "3_3") (pintype "passive"))
      (node (ref "VD28") (pin "A") (pinfunction "Anod_A") (pintype "passive"))
    )
    (net (code "219") (name "/D3-4") (class "Default")
      (node (ref "D3") (pin "14") (pinfunction "QP4_14") (pintype "passive"))
      (node (ref "K26") (pin "3") (pinfunction "3_3") (pintype "passive"))
      (node (ref "VD29") (pin "A") (pinfunction "Anod_A") (pintype "passive"))
    )
    (net (code "220") (name "/D3-5") (class "Default")
      (node (ref "D3") (pin "13") (pinfunction "QP5_13") (pintype "passive"))
      (node (ref "K34") (pin "3") (pinfunction "3_3") (pintype "passive"))
      (node (ref "VD30") (pin "A") (pinfunction "Anod_A") (pintype "passive"))
    )
    (net (code "221") (name "/D3-6") (class "Default")
      (node (ref "D3") (pin "12") (pinfunction "QP6_12") (pintype "passive"))
      (node (ref "K25") (pin "3") (pinfunction "3_3") (pintype "passive"))
      (node (ref "VD31") (pin "A") (pinfunction "Anod_A") (pintype "passive"))
    )
    (net (code "222") (name "/D3-7") (class "Default")
      (node (ref "D3") (pin "11") (pinfunction "QP7_11") (pintype "passive"))
      (node (ref "K33") (pin "3") (pinfunction "3_3") (pintype "passive"))
      (node (ref "VD32") (pin "A") (pinfunction "Anod_A") (pintype "passive"))
    )
    (net (code "224") (name "/D4-0") (class "Default")
      (node (ref "D4") (pin "4") (pinfunction "QP0_4") (pintype "passive"))
      (node (ref "K32") (pin "3") (pinfunction "3_3") (pintype "passive"))
      (node (ref "VD33") (pin "A") (pinfunction "Anod_A") (pintype "passive"))
    )
    (net (code "225") (name "/D4-1") (class "Default")
      (node (ref "D4") (pin "5") (pinfunction "QP1_5") (pintype "passive"))
      (node (ref "K40") (pin "3") (pinfunction "3_3") (pintype "passive"))
      (node (ref "VD34") (pin "A") (pinfunction "Anod_A") (pintype "passive"))
    )
    (net (code "226") (name "/D4-2") (class "Default")
      (node (ref "D4") (pin "6") (pinfunction "QP2_6") (pintype "passive"))
      (node (ref "K31") (pin "3") (pinfunction "3_3") (pintype "passive"))
      (node (ref "VD35") (pin "A") (pinfunction "Anod_A") (pintype "passive"))
    )
    (net (code "227") (name "/D4-3") (class "Default")
      (node (ref "D4") (pin "7") (pinfunction "QP3_7") (pintype "passive"))
      (node (ref "K39") (pin "3") (pinfunction "3_3") (pintype "passive"))
      (node (ref "VD36") (pin "A") (pinfunction "Anod_A") (pintype "passive"))
    )
    (net (code "228") (name "/D4-4") (class "Default")
      (node (ref "D4") (pin "14") (pinfunction "QP4_14") (pintype "passive"))
      (node (ref "K30") (pin "3") (pinfunction "3_3") (pintype "passive"))
      (node (ref "VD37") (pin "A") (pinfunction "Anod_A") (pintype "passive"))
    )
    (net (code "229") (name "/D4-5") (class "Default")
      (node (ref "D4") (pin "13") (pinfunction "QP5_13") (pintype "passive"))
      (node (ref "K38") (pin "3") (pinfunction "3_3") (pintype "passive"))
      (node (ref "VD38") (pin "A") (pinfunction "Anod_A") (pintype "passive"))
    )
    (net (code "230") (name "/D4-6") (class "Default")
      (node (ref "D4") (pin "12") (pinfunction "QP6_12") (pintype "passive"))
      (node (ref "K29") (pin "3") (pinfunction "3_3") (pintype "passive"))
      (node (ref "VD39") (pin "A") (pinfunction "Anod_A") (pintype "passive"))
    )
    (net (code "231") (name "/D4-7") (class "Default")
      (node (ref "D4") (pin "11") (pinfunction "QP7_11") (pintype "passive"))
      (node (ref "K37") (pin "3") (pinfunction "3_3") (pintype "passive"))
      (node (ref "VD40") (pin "A") (pinfunction "Anod_A") (pintype "passive"))
    )
    (net (code "233") (name "/D5-0") (class "Default")
      (node (ref "D5") (pin "4") (pinfunction "QP0_4") (pintype "passive"))
      (node (ref "K44") (pin "3") (pinfunction "3_3") (pintype "passive"))
      (node (ref "VD41") (pin "A") (pinfunction "Anod_A") (pintype "passive"))
    )
    (net (code "234") (name "/D5-1") (class "Default")
      (node (ref "D5") (pin "5") (pinfunction "QP1_5") (pintype "passive"))
      (node (ref "K52") (pin "3") (pinfunction "3_3") (pintype "passive"))
      (node (ref "VD42") (pin "A") (pinfunction "Anod_A") (pintype "passive"))
    )
    (net (code "235") (name "/D5-2") (class "Default")
      (node (ref "D5") (pin "6") (pinfunction "QP2_6") (pintype "passive"))
      (node (ref "K43") (pin "3") (pinfunction "3_3") (pintype "passive"))
      (node (ref "VD43") (pin "A") (pinfunction "Anod_A") (pintype "passive"))
    )
    (net (code "236") (name "/D5-3") (class "Default")
      (node (ref "D5") (pin "7") (pinfunction "QP3_7") (pintype "passive"))
      (node (ref "K51") (pin "3") (pinfunction "3_3") (pintype "passive"))
      (node (ref "VD44") (pin "A") (pinfunction "Anod_A") (pintype "passive"))
    )
    (net (code "237") (name "/D5-4") (class "Default")
      (node (ref "D5") (pin "14") (pinfunction "QP4_14") (pintype "passive"))
      (node (ref "K42") (pin "3") (pinfunction "3_3") (pintype "passive"))
      (node (ref "VD45") (pin "A") (pinfunction "Anod_A") (pintype "passive"))
    )
    (net (code "238") (name "/D5-5") (class "Default")
      (node (ref "D5") (pin "13") (pinfunction "QP5_13") (pintype "passive"))
      (node (ref "K50") (pin "3") (pinfunction "3_3") (pintype "passive"))
      (node (ref "VD46") (pin "A") (pinfunction "Anod_A") (pintype "passive"))
    )
    (net (code "239") (name "/D5-6") (class "Default")
      (node (ref "D5") (pin "12") (pinfunction "QP6_12") (pintype "passive"))
      (node (ref "K41") (pin "3") (pinfunction "3_3") (pintype "passive"))
      (node (ref "VD47") (pin "A") (pinfunction "Anod_A") (pintype "passive"))
    )
    (net (code "240") (name "/D5-7") (class "Default")
      (node (ref "D5") (pin "11") (pinfunction "QP7_11") (pintype "passive"))
      (node (ref "K49") (pin "3") (pinfunction "3_3") (pintype "passive"))
      (node (ref "VD48") (pin "A") (pinfunction "Anod_A") (pintype "passive"))
    )
    (net (code "242") (name "/D6-0") (class "Default")
      (node (ref "D6") (pin "4") (pinfunction "QP0_4") (pintype "passive"))
      (node (ref "K48") (pin "3") (pinfunction "3_3") (pintype "passive"))
      (node (ref "VD49") (pin "A") (pinfunction "Anod_A") (pintype "passive"))
    )
    (net (code "243") (name "/D6-1") (class "Default")
      (node (ref "D6") (pin "5") (pinfunction "QP1_5") (pintype "passive"))
      (node (ref "K56") (pin "3") (pinfunction "3_3") (pintype "passive"))
      (node (ref "VD50") (pin "A") (pinfunction "Anod_A") (pintype "passive"))
    )
    (net (code "244") (name "/D6-2") (class "Default")
      (node (ref "D6") (pin "6") (pinfunction "QP2_6") (pintype "passive"))
      (node (ref "K47") (pin "3") (pinfunction "3_3") (pintype "passive"))
      (node (ref "VD51") (pin "A") (pinfunction "Anod_A") (pintype "passive"))
    )
    (net (code "245") (name "/D6-3") (class "Default")
      (node (ref "D6") (pin "7") (pinfunction "QP3_7") (pintype "passive"))
      (node (ref "K55") (pin "3") (pinfunction "3_3") (pintype "passive"))
      (node (ref "VD52") (pin "A") (pinfunction "Anod_A") (pintype "passive"))
    )
    (net (code "246") (name "/D6-4") (class "Default")
      (node (ref "D6") (pin "14") (pinfunction "QP4_14") (pintype "passive"))
      (node (ref "K46") (pin "3") (pinfunction "3_3") (pintype "passive"))
      (node (ref "VD53") (pin "A") (pinfunction "Anod_A") (pintype "passive"))
    )
    (net (code "247") (name "/D6-5") (class "Default")
      (node (ref "D6") (pin "13") (pinfunction "QP5_13") (pintype "passive"))
      (node (ref "K54") (pin "3") (pinfunction "3_3") (pintype "passive"))
      (node (ref "VD54") (pin "A") (pinfunction "Anod_A") (pintype "passive"))
    )
    (net (code "248") (name "/D6-6") (class "Default")
      (node (ref "D6") (pin "12") (pinfunction "QP6_12") (pintype "passive"))
      (node (ref "K45") (pin "3") (pinfunction "3_3") (pintype "passive"))
      (node (ref "VD55") (pin "A") (pinfunction "Anod_A") (pintype "passive"))
    )
    (net (code "249") (name "/D6-7") (class "Default")
      (node (ref "D6") (pin "11") (pinfunction "QP7_11") (pintype "passive"))
      (node (ref "K53") (pin "3") (pinfunction "3_3") (pintype "passive"))
      (node (ref "VD56") (pin "A") (pinfunction "Anod_A") (pintype "passive"))
    )
    (net (code "251") (name "/D7-0") (class "Default")
      (node (ref "D7") (pin "4") (pinfunction "QP0_4") (pintype "passive"))
      (node (ref "K60") (pin "3") (pinfunction "3_3") (pintype "passive"))
      (node (ref "VD57") (pin "A") (pinfunction "Anod_A") (pintype "passive"))
    )
    (net (code "252") (name "/D7-1") (class "Default")
      (node (ref "D7") (pin "5") (pinfunction "QP1_5") (pintype "passive"))
      (node (ref "K64") (pin "3") (pinfunction "3_3") (pintype "passive"))
      (node (ref "VD58") (pin "A") (pinfunction "Anod_A") (pintype "passive"))
    )
    (net (code "253") (name "/D7-2") (class "Default")
      (node (ref "D7") (pin "6") (pinfunction "QP2_6") (pintype "passive"))
      (node (ref "K59") (pin "3") (pinfunction "3_3") (pintype "passive"))
      (node (ref "VD59") (pin "A") (pinfunction "Anod_A") (pintype "passive"))
    )
    (net (code "254") (name "/D7-3") (class "Default")
      (node (ref "D7") (pin "7") (pinfunction "QP3_7") (pintype "passive"))
      (node (ref "K63") (pin "3") (pinfunction "3_3") (pintype "passive"))
      (node (ref "VD60") (pin "A") (pinfunction "Anod_A") (pintype "passive"))
    )
    (net (code "255") (name "/D7-4") (class "Default")
      (node (ref "K58") (pin "3") (pinfunction "3_3") (pintype "passive"))
      (node (ref "VD61") (pin "A") (pinfunction "Anod_A") (pintype "passive"))
    )
    (net (code "256") (name "/D7-5") (class "Default")
      (node (ref "D7") (pin "13") (pinfunction "QP5_13") (pintype "passive"))
      (node (ref "K62") (pin "3") (pinfunction "3_3") (pintype "passive"))
      (node (ref "VD62") (pin "A") (pinfunction "Anod_A") (pintype "passive"))
    )
    (net (code "257") (name "/D7-6") (class "Default")
      (node (ref "D7") (pin "12") (pinfunction "QP6_12") (pintype "passive"))
      (node (ref "K57") (pin "3") (pinfunction "3_3") (pintype "passive"))
      (node (ref "VD63") (pin "A") (pinfunction "Anod_A") (pintype "passive"))
    )
    (net (code "258") (name "/D7-7") (class "Default")
      (node (ref "D7") (pin "11") (pinfunction "QP7_11") (pintype "passive"))
      (node (ref "K61") (pin "3") (pinfunction "3_3") (pintype "passive"))
      (node (ref "VD64") (pin "A") (pinfunction "Anod_A") (pintype "passive"))
    )
    (net (code "260") (name "/D8-0") (class "Default")
      (node (ref "D8") (pin "4") (pinfunction "QP0_4") (pintype "passive"))
      (node (ref "K68") (pin "3") (pinfunction "3_3") (pintype "passive"))
      (node (ref "VD65") (pin "A") (pinfunction "Anod_A") (pintype "passive"))
    )
    (net (code "261") (name "/D8-1") (class "Default")
      (node (ref "D8") (pin "5") (pinfunction "QP1_5") (pintype "passive"))
      (node (ref "K72") (pin "3") (pinfunction "3_3") (pintype "passive"))
      (node (ref "VD66") (pin "A") (pinfunction "Anod_A") (pintype "passive"))
    )
    (net (code "262") (name "/D8-2") (class "Default")
      (node (ref "D8") (pin "6") (pinfunction "QP2_6") (pintype "passive"))
      (node (ref "K67") (pin "3") (pinfunction "3_3") (pintype "passive"))
      (node (ref "VD67") (pin "A") (pinfunction "Anod_A") (pintype "passive"))
    )
    (net (code "263") (name "/D8-3") (class "Default")
      (node (ref "D8") (pin "7") (pinfunction "QP3_7") (pintype "passive"))
      (node (ref "K71") (pin "3") (pinfunction "3_3") (pintype "passive"))
      (node (ref "VD68") (pin "A") (pinfunction "Anod_A") (pintype "passive"))
    )
    (net (code "264") (name "/D8-4") (class "Default")
      (node (ref "D8") (pin "14") (pinfunction "QP4_14") (pintype "passive"))
      (node (ref "K66") (pin "3") (pinfunction "3_3") (pintype "passive"))
      (node (ref "VD69") (pin "A") (pinfunction "Anod_A") (pintype "passive"))
    )
    (net (code "265") (name "/D8-5") (class "Default")
      (node (ref "D8") (pin "13") (pinfunction "QP5_13") (pintype "passive"))
      (node (ref "K70") (pin "3") (pinfunction "3_3") (pintype "passive"))
      (node (ref "VD70") (pin "A") (pinfunction "Anod_A") (pintype "passive"))
    )
    (net (code "266") (name "/D8-6") (class "Default")
      (node (ref "D8") (pin "12") (pinfunction "QP6_12") (pintype "passive"))
      (node (ref "K65") (pin "3") (pinfunction "3_3") (pintype "passive"))
      (node (ref "VD71") (pin "A") (pinfunction "Anod_A") (pintype "passive"))
    )
    (net (code "267") (name "/D8-7") (class "Default")
      (node (ref "D8") (pin "11") (pinfunction "QP7_11") (pintype "passive"))
      (node (ref "K69") (pin "3") (pinfunction "3_3") (pintype "passive"))
      (node (ref "VD72") (pin "A") (pinfunction "Anod_A") (pintype "passive"))
    )
    (net (code "269") (name "/D9-0") (class "Default")
      (node (ref "D9") (pin "4") (pinfunction "QP0_4") (pintype "passive"))
      (node (ref "K76") (pin "3") (pinfunction "3_3") (pintype "passive"))
      (node (ref "VD73") (pin "A") (pinfunction "Anod_A") (pintype "passive"))
    )
    (net (code "270") (name "/D9-1") (class "Default")
      (node (ref "D9") (pin "5") (pinfunction "QP1_5") (pintype "passive"))
      (node (ref "K80") (pin "3") (pinfunction "3_3") (pintype "passive"))
      (node (ref "VD74") (pin "A") (pinfunction "Anod_A") (pintype "passive"))
    )
    (net (code "271") (name "/D9-2") (class "Default")
      (node (ref "D9") (pin "6") (pinfunction "QP2_6") (pintype "passive"))
      (node (ref "K75") (pin "3") (pinfunction "3_3") (pintype "passive"))
      (node (ref "VD75") (pin "A") (pinfunction "Anod_A") (pintype "passive"))
    )
    (net (code "272") (name "/D9-3") (class "Default")
      (node (ref "D9") (pin "7") (pinfunction "QP3_7") (pintype "passive"))
      (node (ref "K79") (pin "3") (pinfunction "3_3") (pintype "passive"))
      (node (ref "VD76") (pin "A") (pinfunction "Anod_A") (pintype "passive"))
    )
    (net (code "273") (name "/D9-4") (class "Default")
      (node (ref "D9") (pin "14") (pinfunction "QP4_14") (pintype "passive"))
      (node (ref "K74") (pin "3") (pinfunction "3_3") (pintype "passive"))
      (node (ref "VD77") (pin "A") (pinfunction "Anod_A") (pintype "passive"))
    )
    (net (code "274") (name "/D9-5") (class "Default")
      (node (ref "D9") (pin "13") (pinfunction "QP5_13") (pintype "passive"))
      (node (ref "K78") (pin "3") (pinfunction "3_3") (pintype "passive"))
      (node (ref "VD78") (pin "A") (pinfunction "Anod_A") (pintype "passive"))
    )
    (net (code "275") (name "/D9-6") (class "Default")
      (node (ref "D9") (pin "12") (pinfunction "QP6_12") (pintype "passive"))
      (node (ref "K73") (pin "3") (pinfunction "3_3") (pintype "passive"))
      (node (ref "VD79") (pin "A") (pinfunction "Anod_A") (pintype "passive"))
    )
    (net (code "276") (name "/D9-7") (class "Default")
      (node (ref "D9") (pin "11") (pinfunction "QP7_11") (pintype "passive"))
      (node (ref "K77") (pin "3") (pinfunction "3_3") (pintype "passive"))
      (node (ref "VD80") (pin "A") (pinfunction "Anod_A") (pintype "passive"))
    )
    (net (code "278") (name "/D10-0") (class "Default")
      (node (ref "D10") (pin "4") (pinfunction "QP0_4") (pintype "passive"))
      (node (ref "K84") (pin "3") (pinfunction "3_3") (pintype "passive"))
      (node (ref "VD81") (pin "A") (pinfunction "Anod_A") (pintype "passive"))
    )
    (net (code "279") (name "/D10-1") (class "Default")
      (node (ref "D10") (pin "5") (pinfunction "QP1_5") (pintype "passive"))
      (node (ref "K88") (pin "3") (pinfunction "3_3") (pintype "passive"))
      (node (ref "VD82") (pin "A") (pinfunction "Anod_A") (pintype "passive"))
    )
    (net (code "280") (name "/D10-2") (class "Default")
      (node (ref "D10") (pin "6") (pinfunction "QP2_6") (pintype "passive"))
      (node (ref "K83") (pin "3") (pinfunction "3_3") (pintype "passive"))
      (node (ref "VD83") (pin "A") (pinfunction "Anod_A") (pintype "passive"))
    )
    (net (code "281") (name "/D10-3") (class "Default")
      (node (ref "D10") (pin "7") (pinfunction "QP3_7") (pintype "passive"))
      (node (ref "K87") (pin "3") (pinfunction "3_3") (pintype "passive"))
      (node (ref "VD84") (pin "A") (pinfunction "Anod_A") (pintype "passive"))
    )
    (net (code "282") (name "/D10-4") (class "Default")
      (node (ref "D10") (pin "14") (pinfunction "QP4_14") (pintype "passive"))
      (node (ref "K82") (pin "3") (pinfunction "3_3") (pintype "passive"))
      (node (ref "VD85") (pin "A") (pinfunction "Anod_A") (pintype "passive"))
    )
    (net (code "283") (name "/D10-5") (class "Default")
      (node (ref "D10") (pin "13") (pinfunction "QP5_13") (pintype "passive"))
      (node (ref "K86") (pin "3") (pinfunction "3_3") (pintype "passive"))
      (node (ref "VD86") (pin "A") (pinfunction "Anod_A") (pintype "passive"))
    )
    (net (code "284") (name "/D10-6") (class "Default")
      (node (ref "D10") (pin "12") (pinfunction "QP6_12") (pintype "passive"))
      (node (ref "K81") (pin "3") (pinfunction "3_3") (pintype "passive"))
      (node (ref "VD87") (pin "A") (pinfunction "Anod_A") (pintype "passive"))
    )
    (net (code "285") (name "/D10-7") (class "Default")
      (node (ref "D10") (pin "11") (pinfunction "QP7_11") (pintype "passive"))
      (node (ref "K85") (pin "3") (pinfunction "3_3") (pintype "passive"))
      (node (ref "VD88") (pin "A") (pinfunction "Anod_A") (pintype "passive"))
    )
    (net (code "287") (name "/D11-0") (class "Default")
      (node (ref "D11") (pin "4") (pinfunction "QP0_4") (pintype "passive"))
      (node (ref "K92") (pin "3") (pinfunction "3_3") (pintype "passive"))
      (node (ref "VD89") (pin "A") (pinfunction "Anod_A") (pintype "passive"))
    )
    (net (code "288") (name "/D11-1") (class "Default")
      (node (ref "D11") (pin "5") (pinfunction "QP1_5") (pintype "passive"))
      (node (ref "K100") (pin "3") (pinfunction "3_3") (pintype "passive"))
      (node (ref "VD90") (pin "A") (pinfunction "Anod_A") (pintype "passive"))
    )
    (net (code "289") (name "/D11-2") (class "Default")
      (node (ref "D11") (pin "6") (pinfunction "QP2_6") (pintype "passive"))
      (node (ref "K91") (pin "3") (pinfunction "3_3") (pintype "passive"))
      (node (ref "VD91") (pin "A") (pinfunction "Anod_A") (pintype "passive"))
    )
    (net (code "290") (name "/D11-3") (class "Default")
      (node (ref "D11") (pin "7") (pinfunction "QP3_7") (pintype "passive"))
      (node (ref "K99") (pin "3") (pinfunction "3_3") (pintype "passive"))
      (node (ref "VD92") (pin "A") (pinfunction "Anod_A") (pintype "passive"))
    )
    (net (code "291") (name "/D11-4") (class "Default")
      (node (ref "D11") (pin "14") (pinfunction "QP4_14") (pintype "passive"))
      (node (ref "K90") (pin "3") (pinfunction "3_3") (pintype "passive"))
      (node (ref "VD93") (pin "A") (pinfunction "Anod_A") (pintype "passive"))
    )
    (net (code "292") (name "/D11-5") (class "Default")
      (node (ref "D11") (pin "13") (pinfunction "QP5_13") (pintype "passive"))
      (node (ref "K98") (pin "3") (pinfunction "3_3") (pintype "passive"))
      (node (ref "VD94") (pin "A") (pinfunction "Anod_A") (pintype "passive"))
    )
    (net (code "293") (name "/D11-6") (class "Default")
      (node (ref "D11") (pin "12") (pinfunction "QP6_12") (pintype "passive"))
      (node (ref "K89") (pin "3") (pinfunction "3_3") (pintype "passive"))
      (node (ref "VD95") (pin "A") (pinfunction "Anod_A") (pintype "passive"))
    )
    (net (code "294") (name "/D11-7") (class "Default")
      (node (ref "D11") (pin "11") (pinfunction "QP7_11") (pintype "passive"))
      (node (ref "K97") (pin "3") (pinfunction "3_3") (pintype "passive"))
      (node (ref "VD96") (pin "A") (pinfunction "Anod_A") (pintype "passive"))
    )
    (net (code "296") (name "/D12-0") (class "Default")
      (node (ref "D12") (pin "4") (pinfunction "QP0_4") (pintype "passive"))
      (node (ref "K96") (pin "3") (pinfunction "3_3") (pintype "passive"))
      (node (ref "VD97") (pin "A") (pinfunction "Anod_A") (pintype "passive"))
    )
    (net (code "297") (name "/D12-1") (class "Default")
      (node (ref "D12") (pin "5") (pinfunction "QP1_5") (pintype "passive"))
      (node (ref "K104") (pin "3") (pinfunction "3_3") (pintype "passive"))
      (node (ref "VD98") (pin "A") (pinfunction "Anod_A") (pintype "passive"))
    )
    (net (code "298") (name "/D12-2") (class "Default")
      (node (ref "D12") (pin "6") (pinfunction "QP2_6") (pintype "passive"))
      (node (ref "K95") (pin "3") (pinfunction "3_3") (pintype "passive"))
      (node (ref "VD99") (pin "A") (pinfunction "Anod_A") (pintype "passive"))
    )
    (net (code "299") (name "/D12-3") (class "Default")
      (node (ref "D12") (pin "7") (pinfunction "QP3_7") (pintype "passive"))
      (node (ref "K103") (pin "3") (pinfunction "3_3") (pintype "passive"))
      (node (ref "VD100") (pin "A") (pinfunction "Anod_A") (pintype "passive"))
    )
    (net (code "300") (name "/D12-4") (class "Default")
      (node (ref "D12") (pin "14") (pinfunction "QP4_14") (pintype "passive"))
      (node (ref "K94") (pin "3") (pinfunction "3_3") (pintype "passive"))
      (node (ref "VD101") (pin "A") (pinfunction "Anod_A") (pintype "passive"))
    )
    (net (code "301") (name "/D12-5") (class "Default")
      (node (ref "D12") (pin "13") (pinfunction "QP5_13") (pintype "passive"))
      (node (ref "K102") (pin "3") (pinfunction "3_3") (pintype "passive"))
      (node (ref "VD102") (pin "A") (pinfunction "Anod_A") (pintype "passive"))
    )
    (net (code "302") (name "/D12-6") (class "Default")
      (node (ref "D12") (pin "12") (pinfunction "QP6_12") (pintype "passive"))
      (node (ref "K93") (pin "3") (pinfunction "3_3") (pintype "passive"))
      (node (ref "VD103") (pin "A") (pinfunction "Anod_A") (pintype "passive"))
    )
    (net (code "303") (name "/D12-7") (class "Default")
      (node (ref "D12") (pin "11") (pinfunction "QP7_11") (pintype "passive"))
      (node (ref "K101") (pin "3") (pinfunction "3_3") (pintype "passive"))
      (node (ref "VD104") (pin "A") (pinfunction "Anod_A") (pintype "passive"))
    )
    (net (code "305") (name "/D13-0") (class "Default")
      (node (ref "D13") (pin "4") (pinfunction "QP0_4") (pintype "passive"))
      (node (ref "K108") (pin "3") (pinfunction "3_3") (pintype "passive"))
      (node (ref "VD105") (pin "A") (pinfunction "Anod_A") (pintype "passive"))
    )
    (net (code "306") (name "/D13-1") (class "Default")
      (node (ref "D13") (pin "5") (pinfunction "QP1_5") (pintype "passive"))
      (node (ref "K116") (pin "3") (pinfunction "3_3") (pintype "passive"))
      (node (ref "VD106") (pin "A") (pinfunction "Anod_A") (pintype "passive"))
    )
    (net (code "307") (name "/D13-2") (class "Default")
      (node (ref "D13") (pin "6") (pinfunction "QP2_6") (pintype "passive"))
      (node (ref "K107") (pin "3") (pinfunction "3_3") (pintype "passive"))
      (node (ref "VD107") (pin "A") (pinfunction "Anod_A") (pintype "passive"))
    )
    (net (code "308") (name "/D13-3") (class "Default")
      (node (ref "D13") (pin "7") (pinfunction "QP3_7") (pintype "passive"))
      (node (ref "K115") (pin "3") (pinfunction "3_3") (pintype "passive"))
      (node (ref "VD108") (pin "A") (pinfunction "Anod_A") (pintype "passive"))
    )
    (net (code "309") (name "/D13-4") (class "Default")
      (node (ref "D13") (pin "14") (pinfunction "QP4_14") (pintype "passive"))
      (node (ref "K106") (pin "3") (pinfunction "3_3") (pintype "passive"))
      (node (ref "VD109") (pin "A") (pinfunction "Anod_A") (pintype "passive"))
    )
    (net (code "310") (name "/D13-5") (class "Default")
      (node (ref "D13") (pin "13") (pinfunction "QP5_13") (pintype "passive"))
      (node (ref "K114") (pin "3") (pinfunction "3_3") (pintype "passive"))
      (node (ref "VD110") (pin "A") (pinfunction "Anod_A") (pintype "passive"))
    )
    (net (code "311") (name "/D13-6") (class "Default")
      (node (ref "D13") (pin "12") (pinfunction "QP6_12") (pintype "passive"))
      (node (ref "K105") (pin "3") (pinfunction "3_3") (pintype "passive"))
      (node (ref "VD111") (pin "A") (pinfunction "Anod_A") (pintype "passive"))
    )
    (net (code "312") (name "/D13-7") (class "Default")
      (node (ref "D13") (pin "11") (pinfunction "QP7_11") (pintype "passive"))
      (node (ref "K113") (pin "3") (pinfunction "3_3") (pintype "passive"))
      (node (ref "VD112") (pin "A") (pinfunction "Anod_A") (pintype "passive"))
    )
    (net (code "314") (name "/D14-0") (class "Default")
      (node (ref "D14") (pin "4") (pinfunction "QP0_4") (pintype "passive"))
      (node (ref "K112") (pin "3") (pinfunction "3_3") (pintype "passive"))
      (node (ref "VD113") (pin "A") (pinfunction "Anod_A") (pintype "passive"))
    )
    (net (code "315") (name "/D14-1") (class "Default")
      (node (ref "D14") (pin "5") (pinfunction "QP1_5") (pintype "passive"))
      (node (ref "K120") (pin "3") (pinfunction "3_3") (pintype "passive"))
      (node (ref "VD114") (pin "A") (pinfunction "Anod_A") (pintype "passive"))
    )
    (net (code "316") (name "/D14-2") (class "Default")
      (node (ref "D14") (pin "6") (pinfunction "QP2_6") (pintype "passive"))
      (node (ref "K111") (pin "3") (pinfunction "3_3") (pintype "passive"))
      (node (ref "VD115") (pin "A") (pinfunction "Anod_A") (pintype "passive"))
    )
    (net (code "317") (name "/D14-3") (class "Default")
      (node (ref "D14") (pin "7") (pinfunction "QP3_7") (pintype "passive"))
      (node (ref "K119") (pin "3") (pinfunction "3_3") (pintype "passive"))
      (node (ref "VD116") (pin "A") (pinfunction "Anod_A") (pintype "passive"))
    )
    (net (code "318") (name "/D14-4") (class "Default")
      (node (ref "D14") (pin "14") (pinfunction "QP4_14") (pintype "passive"))
      (node (ref "K110") (pin "3") (pinfunction "3_3") (pintype "passive"))
      (node (ref "VD117") (pin "A") (pinfunction "Anod_A") (pintype "passive"))
    )
    (net (code "319") (name "/D14-5") (class "Default")
      (node (ref "D14") (pin "13") (pinfunction "QP5_13") (pintype "passive"))
      (node (ref "K118") (pin "3") (pinfunction "3_3") (pintype "passive"))
      (node (ref "VD118") (pin "A") (pinfunction "Anod_A") (pintype "passive"))
    )
    (net (code "320") (name "/D14-6") (class "Default")
      (node (ref "D14") (pin "12") (pinfunction "QP6_12") (pintype "passive"))
      (node (ref "K109") (pin "3") (pinfunction "3_3") (pintype "passive"))
      (node (ref "VD119") (pin "A") (pinfunction "Anod_A") (pintype "passive"))
    )
    (net (code "321") (name "/D14-7") (class "Default")
      (node (ref "D14") (pin "11") (pinfunction "QP7_11") (pintype "passive"))
      (node (ref "K117") (pin "3") (pinfunction "3_3") (pintype "passive"))
      (node (ref "VD120") (pin "A") (pinfunction "Anod_A") (pintype "passive"))
    )
    (net (code "323") (name "/D15-0") (class "Default")
      (node (ref "D15") (pin "4") (pinfunction "QP0_4") (pintype "passive"))
      (node (ref "K124") (pin "3") (pinfunction "3_3") (pintype "passive"))
      (node (ref "VD121") (pin "A") (pinfunction "Anod_A") (pintype "passive"))
    )
    (net (code "324") (name "/D15-1") (class "Default")
      (node (ref "D15") (pin "5") (pinfunction "QP1_5") (pintype "passive"))
      (node (ref "K132") (pin "3") (pinfunction "3_3") (pintype "passive"))
      (node (ref "VD122") (pin "A") (pinfunction "Anod_A") (pintype "passive"))
    )
    (net (code "325") (name "/D15-2") (class "Default")
      (node (ref "D15") (pin "6") (pinfunction "QP2_6") (pintype "passive"))
      (node (ref "K123") (pin "3") (pinfunction "3_3") (pintype "passive"))
      (node (ref "VD123") (pin "A") (pinfunction "Anod_A") (pintype "passive"))
    )
    (net (code "326") (name "/D15-3") (class "Default")
      (node (ref "D15") (pin "7") (pinfunction "QP3_7") (pintype "passive"))
      (node (ref "K131") (pin "3") (pinfunction "3_3") (pintype "passive"))
      (node (ref "VD124") (pin "A") (pinfunction "Anod_A") (pintype "passive"))
    )
    (net (code "327") (name "/D15-4") (class "Default")
      (node (ref "D15") (pin "14") (pinfunction "QP4_14") (pintype "passive"))
      (node (ref "K122") (pin "3") (pinfunction "3_3") (pintype "passive"))
      (node (ref "VD125") (pin "A") (pinfunction "Anod_A") (pintype "passive"))
    )
    (net (code "328") (name "/D15-5") (class "Default")
      (node (ref "D15") (pin "13") (pinfunction "QP5_13") (pintype "passive"))
      (node (ref "K130") (pin "3") (pinfunction "3_3") (pintype "passive"))
      (node (ref "VD126") (pin "A") (pinfunction "Anod_A") (pintype "passive"))
    )
    (net (code "329") (name "/D15-6") (class "Default")
      (node (ref "D15") (pin "12") (pinfunction "QP6_12") (pintype "passive"))
      (node (ref "K121") (pin "3") (pinfunction "3_3") (pintype "passive"))
      (node (ref "VD127") (pin "A") (pinfunction "Anod_A") (pintype "passive"))
    )
    (net (code "330") (name "/D15-7") (class "Default")
      (node (ref "D15") (pin "11") (pinfunction "QP7_11") (pintype "passive"))
      (node (ref "K129") (pin "3") (pinfunction "3_3") (pintype "passive"))
      (node (ref "VD128") (pin "A") (pinfunction "Anod_A") (pintype "passive"))
    )
    (net (code "332") (name "/D16-0") (class "Default")
      (node (ref "D16") (pin "4") (pinfunction "QP0_4") (pintype "passive"))
      (node (ref "K128") (pin "3") (pinfunction "3_3") (pintype "passive"))
      (node (ref "VD129") (pin "A") (pinfunction "Anod_A") (pintype "passive"))
    )
    (net (code "333") (name "/D16-1") (class "Default")
      (node (ref "D16") (pin "5") (pinfunction "QP1_5") (pintype "passive"))
      (node (ref "K136") (pin "3") (pinfunction "3_3") (pintype "passive"))
      (node (ref "VD130") (pin "A") (pinfunction "Anod_A") (pintype "passive"))
    )
    (net (code "334") (name "/D16-2") (class "Default")
      (node (ref "D16") (pin "6") (pinfunction "QP2_6") (pintype "passive"))
      (node (ref "K127") (pin "3") (pinfunction "3_3") (pintype "passive"))
      (node (ref "VD131") (pin "A") (pinfunction "Anod_A") (pintype "passive"))
    )
    (net (code "335") (name "/D16-3") (class "Default")
      (node (ref "D16") (pin "7") (pinfunction "QP3_7") (pintype "passive"))
      (node (ref "K135") (pin "3") (pinfunction "3_3") (pintype "passive"))
      (node (ref "VD132") (pin "A") (pinfunction "Anod_A") (pintype "passive"))
    )
    (net (code "336") (name "/D16-4") (class "Default")
      (node (ref "D16") (pin "14") (pinfunction "QP4_14") (pintype "passive"))
      (node (ref "K126") (pin "3") (pinfunction "3_3") (pintype "passive"))
      (node (ref "VD133") (pin "A") (pinfunction "Anod_A") (pintype "passive"))
    )
    (net (code "337") (name "/D16-5") (class "Default")
      (node (ref "D16") (pin "13") (pinfunction "QP5_13") (pintype "passive"))
      (node (ref "K134") (pin "3") (pinfunction "3_3") (pintype "passive"))
      (node (ref "VD134") (pin "A") (pinfunction "Anod_A") (pintype "passive"))
    )
    (net (code "338") (name "/D16-6") (class "Default")
      (node (ref "D16") (pin "12") (pinfunction "QP6_12") (pintype "passive"))
      (node (ref "K125") (pin "3") (pinfunction "3_3") (pintype "passive"))
      (node (ref "VD135") (pin "A") (pinfunction "Anod_A") (pintype "passive"))
    )
    (net (code "339") (name "/D16-7") (class "Default")
      (node (ref "D16") (pin "11") (pinfunction "QP7_11") (pintype "passive"))
      (node (ref "K133") (pin "3") (pinfunction "3_3") (pintype "passive"))
      (node (ref "VD136") (pin "A") (pinfunction "Anod_A") (pintype "passive"))
    )
    (net (code "341") (name "/D17-0") (class "Default")
      (node (ref "D17") (pin "4") (pinfunction "QP0_4") (pintype "passive"))
      (node (ref "K140") (pin "3") (pinfunction "3_3") (pintype "passive"))
      (node (ref "VD137") (pin "A") (pinfunction "Anod_A") (pintype "passive"))
    )
    (net (code "342") (name "/D17-1") (class "Default")
      (node (ref "D17") (pin "5") (pinfunction "QP1_5") (pintype "passive"))
      (node (ref "K148") (pin "3") (pinfunction "3_3") (pintype "passive"))
      (node (ref "VD138") (pin "A") (pinfunction "Anod_A") (pintype "passive"))
    )
    (net (code "343") (name "/D17-2") (class "Default")
      (node (ref "D17") (pin "6") (pinfunction "QP2_6") (pintype "passive"))
      (node (ref "K139") (pin "3") (pinfunction "3_3") (pintype "passive"))
      (node (ref "VD139") (pin "A") (pinfunction "Anod_A") (pintype "passive"))
    )
    (net (code "344") (name "/D17-3") (class "Default")
      (node (ref "D17") (pin "7") (pinfunction "QP3_7") (pintype "passive"))
      (node (ref "K147") (pin "3") (pinfunction "3_3") (pintype "passive"))
      (node (ref "VD140") (pin "A") (pinfunction "Anod_A") (pintype "passive"))
    )
    (net (code "345") (name "/D17-4") (class "Default")
      (node (ref "D17") (pin "14") (pinfunction "QP4_14") (pintype "passive"))
      (node (ref "K138") (pin "3") (pinfunction "3_3") (pintype "passive"))
      (node (ref "VD141") (pin "A") (pinfunction "Anod_A") (pintype "passive"))
    )
    (net (code "346") (name "/D17-5") (class "Default")
      (node (ref "D17") (pin "13") (pinfunction "QP5_13") (pintype "passive"))
      (node (ref "K146") (pin "3") (pinfunction "3_3") (pintype "passive"))
      (node (ref "VD142") (pin "A") (pinfunction "Anod_A") (pintype "passive"))
    )
    (net (code "347") (name "/D17-6") (class "Default")
      (node (ref "D17") (pin "12") (pinfunction "QP6_12") (pintype "passive"))
      (node (ref "K137") (pin "3") (pinfunction "3_3") (pintype "passive"))
      (node (ref "VD143") (pin "A") (pinfunction "Anod_A") (pintype "passive"))
    )
    (net (code "348") (name "/D17-7") (class "Default")
      (node (ref "D17") (pin "11") (pinfunction "QP7_11") (pintype "passive"))
      (node (ref "K145") (pin "3") (pinfunction "3_3") (pintype "passive"))
      (node (ref "VD144") (pin "A") (pinfunction "Anod_A") (pintype "passive"))
    )
    (net (code "350") (name "/D18-0") (class "Default")
      (node (ref "D18") (pin "4") (pinfunction "QP0_4") (pintype "passive"))
      (node (ref "K144") (pin "3") (pinfunction "3_3") (pintype "passive"))
      (node (ref "VD145") (pin "A") (pinfunction "Anod_A") (pintype "passive"))
    )
    (net (code "351") (name "/D18-1") (class "Default")
      (node (ref "D18") (pin "5") (pinfunction "QP1_5") (pintype "passive"))
      (node (ref "K152") (pin "3") (pinfunction "3_3") (pintype "passive"))
      (node (ref "VD146") (pin "A") (pinfunction "Anod_A") (pintype "passive"))
    )
    (net (code "352") (name "/D18-2") (class "Default")
      (node (ref "D18") (pin "6") (pinfunction "QP2_6") (pintype "passive"))
      (node (ref "K143") (pin "3") (pinfunction "3_3") (pintype "passive"))
      (node (ref "VD147") (pin "A") (pinfunction "Anod_A") (pintype "passive"))
    )
    (net (code "353") (name "/D18-3") (class "Default")
      (node (ref "D18") (pin "7") (pinfunction "QP3_7") (pintype "passive"))
      (node (ref "K151") (pin "3") (pinfunction "3_3") (pintype "passive"))
      (node (ref "VD148") (pin "A") (pinfunction "Anod_A") (pintype "passive"))
    )
    (net (code "354") (name "/D18-4") (class "Default")
      (node (ref "D18") (pin "14") (pinfunction "QP4_14") (pintype "passive"))
      (node (ref "K142") (pin "3") (pinfunction "3_3") (pintype "passive"))
      (node (ref "VD149") (pin "A") (pinfunction "Anod_A") (pintype "passive"))
    )
    (net (code "355") (name "/D18-5") (class "Default")
      (node (ref "D18") (pin "13") (pinfunction "QP5_13") (pintype "passive"))
      (node (ref "K150") (pin "3") (pinfunction "3_3") (pintype "passive"))
      (node (ref "VD150") (pin "A") (pinfunction "Anod_A") (pintype "passive"))
    )
    (net (code "356") (name "/D18-6") (class "Default")
      (node (ref "D18") (pin "12") (pinfunction "QP6_12") (pintype "passive"))
      (node (ref "K141") (pin "3") (pinfunction "3_3") (pintype "passive"))
      (node (ref "VD151") (pin "A") (pinfunction "Anod_A") (pintype "passive"))
    )
    (net (code "357") (name "/D18-7") (class "Default")
      (node (ref "D18") (pin "11") (pinfunction "QP7_11") (pintype "passive"))
      (node (ref "K149") (pin "3") (pinfunction "3_3") (pintype "passive"))
      (node (ref "VD152") (pin "A") (pinfunction "Anod_A") (pintype "passive"))
    )
    (net (code "359") (name "/D19-0") (class "Default")
      (node (ref "D19") (pin "4") (pinfunction "QP0_4") (pintype "passive"))
      (node (ref "K156") (pin "3") (pinfunction "3_3") (pintype "passive"))
      (node (ref "VD153") (pin "A") (pinfunction "Anod_A") (pintype "passive"))
    )
    (net (code "360") (name "/D19-1") (class "Default")
      (node (ref "D19") (pin "5") (pinfunction "QP1_5") (pintype "passive"))
      (node (ref "K160") (pin "3") (pinfunction "3_3") (pintype "passive"))
      (node (ref "VD154") (pin "A") (pinfunction "Anod_A") (pintype "passive"))
    )
    (net (code "361") (name "/D19-2") (class "Default")
      (node (ref "D19") (pin "6") (pinfunction "QP2_6") (pintype "passive"))
      (node (ref "K155") (pin "3") (pinfunction "3_3") (pintype "passive"))
      (node (ref "VD155") (pin "A") (pinfunction "Anod_A") (pintype "passive"))
    )
    (net (code "362") (name "/D19-3") (class "Default")
      (node (ref "D19") (pin "7") (pinfunction "QP3_7") (pintype "passive"))
      (node (ref "K159") (pin "3") (pinfunction "3_3") (pintype "passive"))
      (node (ref "VD156") (pin "A") (pinfunction "Anod_A") (pintype "passive"))
    )
    (net (code "363") (name "/D19-4") (class "Default")
      (node (ref "D19") (pin "14") (pinfunction "QP4_14") (pintype "passive"))
      (node (ref "K154") (pin "3") (pinfunction "3_3") (pintype "passive"))
      (node (ref "VD157") (pin "A") (pinfunction "Anod_A") (pintype "passive"))
    )
    (net (code "364") (name "/D19-5") (class "Default")
      (node (ref "D19") (pin "13") (pinfunction "QP5_13") (pintype "passive"))
      (node (ref "K158") (pin "3") (pinfunction "3_3") (pintype "passive"))
      (node (ref "VD158") (pin "A") (pinfunction "Anod_A") (pintype "passive"))
    )
    (net (code "365") (name "/D19-6") (class "Default")
      (node (ref "D19") (pin "12") (pinfunction "QP6_12") (pintype "passive"))
      (node (ref "K153") (pin "3") (pinfunction "3_3") (pintype "passive"))
      (node (ref "VD159") (pin "A") (pinfunction "Anod_A") (pintype "passive"))
    )
    (net (code "366") (name "/D19-7") (class "Default")
      (node (ref "D19") (pin "11") (pinfunction "QP7_11") (pintype "passive"))
      (node (ref "K157") (pin "3") (pinfunction "3_3") (pintype "passive"))
      (node (ref "VD160") (pin "A") (pinfunction "Anod_A") (pintype "passive"))
    )
    (net (code "367") (name "/D20-0") (class "Default")
      (node (ref "D20") (pin "4") (pinfunction "QP0_4") (pintype "passive"))
      (node (ref "K164") (pin "3") (pinfunction "3_3") (pintype "passive"))
      (node (ref "VD161") (pin "A") (pinfunction "Anod_A") (pintype "passive"))
    )
    (net (code "368") (name "/D20-1") (class "Default")
      (node (ref "D20") (pin "5") (pinfunction "QP1_5") (pintype "passive"))
      (node (ref "K168") (pin "3") (pinfunction "3_3") (pintype "passive"))
      (node (ref "VD162") (pin "A") (pinfunction "Anod_A") (pintype "passive"))
    )
    (net (code "369") (name "/D20-2") (class "Default")
      (node (ref "D20") (pin "6") (pinfunction "QP2_6") (pintype "passive"))
      (node (ref "K163") (pin "3") (pinfunction "3_3") (pintype "passive"))
      (node (ref "VD163") (pin "A") (pinfunction "Anod_A") (pintype "passive"))
    )
    (net (code "370") (name "/D20-3") (class "Default")
      (node (ref "D20") (pin "7") (pinfunction "QP3_7") (pintype "passive"))
      (node (ref "K167") (pin "3") (pinfunction "3_3") (pintype "passive"))
      (node (ref "VD164") (pin "A") (pinfunction "Anod_A") (pintype "passive"))
    )
    (net (code "371") (name "/D20-4") (class "Default")
      (node (ref "D20") (pin "14") (pinfunction "QP4_14") (pintype "passive"))
      (node (ref "K162") (pin "3") (pinfunction "3_3") (pintype "passive"))
      (node (ref "VD165") (pin "A") (pinfunction "Anod_A") (pintype "passive"))
    )
    (net (code "372") (name "/D20-5") (class "Default")
      (node (ref "D20") (pin "13") (pinfunction "QP5_13") (pintype "passive"))
      (node (ref "K166") (pin "3") (pinfunction "3_3") (pintype "passive"))
      (node (ref "VD166") (pin "A") (pinfunction "Anod_A") (pintype "passive"))
    )
    (net (code "373") (name "/D20-6") (class "Default")
      (node (ref "D20") (pin "12") (pinfunction "QP6_12") (pintype "passive"))
      (node (ref "K161") (pin "3") (pinfunction "3_3") (pintype "passive"))
      (node (ref "VD167") (pin "A") (pinfunction "Anod_A") (pintype "passive"))
    )
    (net (code "374") (name "/D20-7") (class "Default")
      (node (ref "D20") (pin "11") (pinfunction "QP7_11") (pintype "passive"))
      (node (ref "K165") (pin "3") (pinfunction "3_3") (pintype "passive"))
      (node (ref "VD168") (pin "A") (pinfunction "Anod_A") (pintype "passive"))
    )
    (net (code "376") (name "/D21-0") (class "Default")
      (node (ref "D21") (pin "4") (pinfunction "QP0_4") (pintype "passive"))
      (node (ref "K172") (pin "3") (pinfunction "3_3") (pintype "passive"))
      (node (ref "VD169") (pin "A") (pinfunction "Anod_A") (pintype "passive"))
    )
    (net (code "377") (name "/D21-1") (class "Default")
      (node (ref "D21") (pin "5") (pinfunction "QP1_5") (pintype "passive"))
      (node (ref "K176") (pin "3") (pinfunction "3_3") (pintype "passive"))
      (node (ref "VD170") (pin "A") (pinfunction "Anod_A") (pintype "passive"))
    )
    (net (code "378") (name "/D21-2") (class "Default")
      (node (ref "D21") (pin "6") (pinfunction "QP2_6") (pintype "passive"))
      (node (ref "K171") (pin "3") (pinfunction "3_3") (pintype "passive"))
      (node (ref "VD171") (pin "A") (pinfunction "Anod_A") (pintype "passive"))
    )
    (net (code "379") (name "/D21-3") (class "Default")
      (node (ref "D21") (pin "7") (pinfunction "QP3_7") (pintype "passive"))
      (node (ref "K175") (pin "3") (pinfunction "3_3") (pintype "passive"))
      (node (ref "VD172") (pin "A") (pinfunction "Anod_A") (pintype "passive"))
    )
    (net (code "380") (name "/D21-4") (class "Default")
      (node (ref "D21") (pin "14") (pinfunction "QP4_14") (pintype "passive"))
      (node (ref "K170") (pin "3") (pinfunction "3_3") (pintype "passive"))
      (node (ref "VD173") (pin "A") (pinfunction "Anod_A") (pintype "passive"))
    )
    (net (code "381") (name "/D21-5") (class "Default")
      (node (ref "D21") (pin "13") (pinfunction "QP5_13") (pintype "passive"))
      (node (ref "K174") (pin "3") (pinfunction "3_3") (pintype "passive"))
      (node (ref "VD174") (pin "A") (pinfunction "Anod_A") (pintype "passive"))
    )
    (net (code "382") (name "/D21-6") (class "Default")
      (node (ref "D21") (pin "12") (pinfunction "QP6_12") (pintype "passive"))
      (node (ref "K169") (pin "3") (pinfunction "3_3") (pintype "passive"))
      (node (ref "VD175") (pin "A") (pinfunction "Anod_A") (pintype "passive"))
    )
    (net (code "383") (name "/D21-7") (class "Default")
      (node (ref "D21") (pin "11") (pinfunction "QP7_11") (pintype "passive"))
      (node (ref "K173") (pin "3") (pinfunction "3_3") (pintype "passive"))
      (node (ref "VD176") (pin "A") (pinfunction "Anod_A") (pintype "passive"))
    )
    (net (code "385") (name "/D22-0") (class "Default")
      (node (ref "D22") (pin "4") (pinfunction "QP0_4") (pintype "passive"))
      (node (ref "K180") (pin "3") (pinfunction "3_3") (pintype "passive"))
      (node (ref "VD177") (pin "A") (pinfunction "Anod_A") (pintype "passive"))
    )
    (net (code "386") (name "/D22-1") (class "Default")
      (node (ref "D22") (pin "5") (pinfunction "QP1_5") (pintype "passive"))
      (node (ref "K184") (pin "3") (pinfunction "3_3") (pintype "passive"))
      (node (ref "VD178") (pin "A") (pinfunction "Anod_A") (pintype "passive"))
    )
    (net (code "387") (name "/D22-2") (class "Default")
      (node (ref "D22") (pin "6") (pinfunction "QP2_6") (pintype "passive"))
      (node (ref "K179") (pin "3") (pinfunction "3_3") (pintype "passive"))
      (node (ref "VD179") (pin "A") (pinfunction "Anod_A") (pintype "passive"))
    )
    (net (code "388") (name "/D22-3") (class "Default")
      (node (ref "D22") (pin "7") (pinfunction "QP3_7") (pintype "passive"))
      (node (ref "K183") (pin "3") (pinfunction "3_3") (pintype "passive"))
      (node (ref "VD180") (pin "A") (pinfunction "Anod_A") (pintype "passive"))
    )
    (net (code "389") (name "/D22-4") (class "Default")
      (node (ref "D22") (pin "14") (pinfunction "QP4_14") (pintype "passive"))
      (node (ref "K178") (pin "3") (pinfunction "3_3") (pintype "passive"))
      (node (ref "VD181") (pin "A") (pinfunction "Anod_A") (pintype "passive"))
    )
    (net (code "390") (name "/D22-5") (class "Default")
      (node (ref "D22") (pin "13") (pinfunction "QP5_13") (pintype "passive"))
      (node (ref "K182") (pin "3") (pinfunction "3_3") (pintype "passive"))
      (node (ref "VD182") (pin "A") (pinfunction "Anod_A") (pintype "passive"))
    )
    (net (code "391") (name "/D22-6") (class "Default")
      (node (ref "D22") (pin "12") (pinfunction "QP6_12") (pintype "passive"))
      (node (ref "K177") (pin "3") (pinfunction "3_3") (pintype "passive"))
      (node (ref "VD183") (pin "A") (pinfunction "Anod_A") (pintype "passive"))
    )
    (net (code "392") (name "/D22-7") (class "Default")
      (node (ref "D22") (pin "11") (pinfunction "QP7_11") (pintype "passive"))
      (node (ref "K181") (pin "3") (pinfunction "3_3") (pintype "passive"))
      (node (ref "VD184") (pin "A") (pinfunction "Anod_A") (pintype "passive"))
    )
    (net (code "394") (name "/D23-0") (class "Default")
      (node (ref "D23") (pin "4") (pinfunction "QP0_4") (pintype "passive"))
      (node (ref "K188") (pin "3") (pinfunction "3_3") (pintype "passive"))
      (node (ref "VD185") (pin "A") (pinfunction "Anod_A") (pintype "passive"))
    )
    (net (code "395") (name "/D23-1") (class "Default")
      (node (ref "D23") (pin "5") (pinfunction "QP1_5") (pintype "passive"))
      (node (ref "K192") (pin "3") (pinfunction "3_3") (pintype "passive"))
      (node (ref "VD186") (pin "A") (pinfunction "Anod_A") (pintype "passive"))
    )
    (net (code "396") (name "/D23-2") (class "Default")
      (node (ref "D23") (pin "6") (pinfunction "QP2_6") (pintype "passive"))
      (node (ref "K187") (pin "3") (pinfunction "3_3") (pintype "passive"))
      (node (ref "VD187") (pin "A") (pinfunction "Anod_A") (pintype "passive"))
    )
    (net (code "397") (name "/D23-3") (class "Default")
      (node (ref "D23") (pin "7") (pinfunction "QP3_7") (pintype "passive"))
      (node (ref "K191") (pin "3") (pinfunction "3_3") (pintype "passive"))
      (node (ref "VD188") (pin "A") (pinfunction "Anod_A") (pintype "passive"))
    )
    (net (code "398") (name "/D23-4") (class "Default")
      (node (ref "D23") (pin "14") (pinfunction "QP4_14") (pintype "passive"))
      (node (ref "K186") (pin "3") (pinfunction "3_3") (pintype "passive"))
      (node (ref "VD189") (pin "A") (pinfunction "Anod_A") (pintype "passive"))
    )
    (net (code "399") (name "/D23-5") (class "Default")
      (node (ref "D23") (pin "13") (pinfunction "QP5_13") (pintype "passive"))
      (node (ref "K190") (pin "3") (pinfunction "3_3") (pintype "passive"))
      (node (ref "VD190") (pin "A") (pinfunction "Anod_A") (pintype "passive"))
    )
    (net (code "400") (name "/D23-6") (class "Default")
      (node (ref "D23") (pin "12") (pinfunction "QP6_12") (pintype "passive"))
      (node (ref "K185") (pin "3") (pinfunction "3_3") (pintype "passive"))
      (node (ref "VD191") (pin "A") (pinfunction "Anod_A") (pintype "passive"))
    )
    (net (code "401") (name "/D23-7") (class "Default")
      (node (ref "D23") (pin "11") (pinfunction "QP7_11") (pintype "passive"))
      (node (ref "K189") (pin "3") (pinfunction "3_3") (pintype "passive"))
      (node (ref "VD192") (pin "A") (pinfunction "Anod_A") (pintype "passive"))
    )
    (net (code "403") (name "/Data") (class "Default")
      (node (ref "D0") (pin "2") (pinfunction "D_2") (pintype "passive"))
      (node (ref "PLD1") (pin "1") (pinfunction "1_1") (pintype "passive"))
    )
    (net (code "404") (name "/EO") (class "Default")
      (node (ref "D0") (pin "15") (pinfunction "OE_15") (pintype "passive"))
      (node (ref "D1") (pin "15") (pinfunction "OE_15") (pintype "passive"))
      (node (ref "D10") (pin "15") (pinfunction "OE_15") (pintype "passive"))
      (node (ref "D11") (pin "15") (pinfunction "OE_15") (pintype "passive"))
      (node (ref "D12") (pin "15") (pinfunction "OE_15") (pintype "passive"))
      (node (ref "D13") (pin "15") (pinfunction "OE_15") (pintype "passive"))
      (node (ref "D14") (pin "15") (pinfunction "OE_15") (pintype "passive"))
      (node (ref "D15") (pin "15") (pinfunction "OE_15") (pintype "passive"))
      (node (ref "D16") (pin "15") (pinfunction "OE_15") (pintype "passive"))
      (node (ref "D17") (pin "15") (pinfunction "OE_15") (pintype "passive"))
      (node (ref "D18") (pin "15") (pinfunction "OE_15") (pintype "passive"))
      (node (ref "D19") (pin "15") (pinfunction "OE_15") (pintype "passive"))
      (node (ref "D2") (pin "15") (pinfunction "OE_15") (pintype "passive"))
      (node (ref "D20") (pin "15") (pinfunction "OE_15") (pintype "passive"))
      (node (ref "D21") (pin "15") (pinfunction "OE_15") (pintype "passive"))
      (node (ref "D22") (pin "15") (pinfunction "OE_15") (pintype "passive"))
      (node (ref "D23") (pin "15") (pinfunction "OE_15") (pintype "passive"))
      (node (ref "D3") (pin "15") (pinfunction "OE_15") (pintype "passive"))
      (node (ref "D4") (pin "15") (pinfunction "OE_15") (pintype "passive"))
      (node (ref "D5") (pin "15") (pinfunction "OE_15") (pintype "passive"))
      (node (ref "D6") (pin "15") (pinfunction "OE_15") (pintype "passive"))
      (node (ref "D7") (pin "15") (pinfunction "OE_15") (pintype "passive"))
      (node (ref "D8") (pin "15") (pinfunction "OE_15") (pintype "passive"))
      (node (ref "D9") (pin "15") (pinfunction "OE_15") (pintype "passive"))
      (node (ref "PLD1") (pin "4") (pinfunction "4_4") (pintype "passive"))
    )
    (net (code "405") (name "/GND(Dirty)") (class "Default")
      (node (ref "D0") (pin "8") (pinfunction "Vss_8") (pintype "passive"))
      (node (ref "D1") (pin "8") (pinfunction "Vss_8") (pintype "passive"))
      (node (ref "D10") (pin "8") (pinfunction "Vss_8") (pintype "passive"))
      (node (ref "D11") (pin "8") (pinfunction "Vss_8") (pintype "passive"))
      (node (ref "D12") (pin "8") (pinfunction "Vss_8") (pintype "passive"))
      (node (ref "D13") (pin "8") (pinfunction "Vss_8") (pintype "passive"))
      (node (ref "D14") (pin "8") (pinfunction "Vss_8") (pintype "passive"))
      (node (ref "D15") (pin "8") (pinfunction "Vss_8") (pintype "passive"))
      (node (ref "D16") (pin "8") (pinfunction "Vss_8") (pintype "passive"))
      (node (ref "D17") (pin "8") (pinfunction "Vss_8") (pintype "passive"))
      (node (ref "D18") (pin "8") (pinfunction "Vss_8") (pintype "passive"))
      (node (ref "D19") (pin "8") (pinfunction "Vss_8") (pintype "passive"))
      (node (ref "D2") (pin "8") (pinfunction "Vss_8") (pintype "passive"))
      (node (ref "D20") (pin "8") (pinfunction "Vss_8") (pintype "passive"))
      (node (ref "D21") (pin "8") (pinfunction "Vss_8") (pintype "passive"))
      (node (ref "D22") (pin "8") (pinfunction "Vss_8") (pintype "passive"))
      (node (ref "D23") (pin "8") (pinfunction "Vss_8") (pintype "passive"))
      (node (ref "D3") (pin "8") (pinfunction "Vss_8") (pintype "passive"))
      (node (ref "D4") (pin "8") (pinfunction "Vss_8") (pintype "passive"))
      (node (ref "D5") (pin "8") (pinfunction "Vss_8") (pintype "passive"))
      (node (ref "D6") (pin "8") (pinfunction "Vss_8") (pintype "passive"))
      (node (ref "D7") (pin "8") (pinfunction "Vss_8") (pintype "passive"))
      (node (ref "D8") (pin "8") (pinfunction "Vss_8") (pintype "passive"))
      (node (ref "D9") (pin "8") (pinfunction "Vss_8") (pintype "passive"))
      (node (ref "K1") (pin "5") (pinfunction "5_5") (pintype "passive"))
      (node (ref "K10") (pin "5") (pinfunction "5_5") (pintype "passive"))
      (node (ref "K100") (pin "5") (pinfunction "5_5") (pintype "passive"))
      (node (ref "K101") (pin "5") (pinfunction "5_5") (pintype "passive"))
      (node (ref "K102") (pin "5") (pinfunction "5_5") (pintype "passive"))
      (node (ref "K103") (pin "5") (pinfunction "5_5") (pintype "passive"))
      (node (ref "K104") (pin "5") (pinfunction "5_5") (pintype "passive"))
      (node (ref "K105") (pin "5") (pinfunction "5_5") (pintype "passive"))
      (node (ref "K106") (pin "5") (pinfunction "5_5") (pintype "passive"))
      (node (ref "K107") (pin "5") (pinfunction "5_5") (pintype "passive"))
      (node (ref "K108") (pin "5") (pinfunction "5_5") (pintype "passive"))
      (node (ref "K109") (pin "5") (pinfunction "5_5") (pintype "passive"))
      (node (ref "K11") (pin "5") (pinfunction "5_5") (pintype "passive"))
      (node (ref "K110") (pin "5") (pinfunction "5_5") (pintype "passive"))
      (node (ref "K111") (pin "5") (pinfunction "5_5") (pintype "passive"))
      (node (ref "K112") (pin "5") (pinfunction "5_5") (pintype "passive"))
      (node (ref "K113") (pin "5") (pinfunction "5_5") (pintype "passive"))
      (node (ref "K114") (pin "5") (pinfunction "5_5") (pintype "passive"))
      (node (ref "K115") (pin "5") (pinfunction "5_5") (pintype "passive"))
      (node (ref "K116") (pin "5") (pinfunction "5_5") (pintype "passive"))
      (node (ref "K117") (pin "5") (pinfunction "5_5") (pintype "passive"))
      (node (ref "K118") (pin "5") (pinfunction "5_5") (pintype "passive"))
      (node (ref "K119") (pin "5") (pinfunction "5_5") (pintype "passive"))
      (node (ref "K12") (pin "5") (pinfunction "5_5") (pintype "passive"))
      (node (ref "K120") (pin "5") (pinfunction "5_5") (pintype "passive"))
      (node (ref "K121") (pin "5") (pinfunction "5_5") (pintype "passive"))
      (node (ref "K122") (pin "5") (pinfunction "5_5") (pintype "passive"))
      (node (ref "K123") (pin "5") (pinfunction "5_5") (pintype "passive"))
      (node (ref "K124") (pin "5") (pinfunction "5_5") (pintype "passive"))
      (node (ref "K125") (pin "5") (pinfunction "5_5") (pintype "passive"))
      (node (ref "K126") (pin "5") (pinfunction "5_5") (pintype "passive"))
      (node (ref "K127") (pin "5") (pinfunction "5_5") (pintype "passive"))
      (node (ref "K128") (pin "5") (pinfunction "5_5") (pintype "passive"))
      (node (ref "K129") (pin "5") (pinfunction "5_5") (pintype "passive"))
      (node (ref "K13") (pin "5") (pinfunction "5_5") (pintype "passive"))
      (node (ref "K130") (pin "5") (pinfunction "5_5") (pintype "passive"))
      (node (ref "K131") (pin "5") (pinfunction "5_5") (pintype "passive"))
      (node (ref "K132") (pin "5") (pinfunction "5_5") (pintype "passive"))
      (node (ref "K133") (pin "5") (pinfunction "5_5") (pintype "passive"))
      (node (ref "K134") (pin "5") (pinfunction "5_5") (pintype "passive"))
      (node (ref "K135") (pin "5") (pinfunction "5_5") (pintype "passive"))
      (node (ref "K136") (pin "5") (pinfunction "5_5") (pintype "passive"))
      (node (ref "K137") (pin "5") (pinfunction "5_5") (pintype "passive"))
      (node (ref "K138") (pin "5") (pinfunction "5_5") (pintype "passive"))
      (node (ref "K139") (pin "5") (pinfunction "5_5") (pintype "passive"))
      (node (ref "K14") (pin "5") (pinfunction "5_5") (pintype "passive"))
      (node (ref "K140") (pin "5") (pinfunction "5_5") (pintype "passive"))
      (node (ref "K141") (pin "5") (pinfunction "5_5") (pintype "passive"))
      (node (ref "K142") (pin "5") (pinfunction "5_5") (pintype "passive"))
      (node (ref "K143") (pin "5") (pinfunction "5_5") (pintype "passive"))
      (node (ref "K144") (pin "5") (pinfunction "5_5") (pintype "passive"))
      (node (ref "K145") (pin "5") (pinfunction "5_5") (pintype "passive"))
      (node (ref "K146") (pin "5") (pinfunction "5_5") (pintype "passive"))
      (node (ref "K147") (pin "5") (pinfunction "5_5") (pintype "passive"))
      (node (ref "K148") (pin "5") (pinfunction "5_5") (pintype "passive"))
      (node (ref "K149") (pin "5") (pinfunction "5_5") (pintype "passive"))
      (node (ref "K15") (pin "5") (pinfunction "5_5") (pintype "passive"))
      (node (ref "K150") (pin "5") (pinfunction "5_5") (pintype "passive"))
      (node (ref "K151") (pin "5") (pinfunction "5_5") (pintype "passive"))
      (node (ref "K152") (pin "5") (pinfunction "5_5") (pintype "passive"))
      (node (ref "K153") (pin "5") (pinfunction "5_5") (pintype "passive"))
      (node (ref "K154") (pin "5") (pinfunction "5_5") (pintype "passive"))
      (node (ref "K155") (pin "5") (pinfunction "5_5") (pintype "passive"))
      (node (ref "K156") (pin "5") (pinfunction "5_5") (pintype "passive"))
      (node (ref "K157") (pin "5") (pinfunction "5_5") (pintype "passive"))
      (node (ref "K158") (pin "5") (pinfunction "5_5") (pintype "passive"))
      (node (ref "K159") (pin "5") (pinfunction "5_5") (pintype "passive"))
      (node (ref "K16") (pin "5") (pinfunction "5_5") (pintype "passive"))
      (node (ref "K160") (pin "5") (pinfunction "5_5") (pintype "passive"))
      (node (ref "K161") (pin "5") (pinfunction "5_5") (pintype "passive"))
      (node (ref "K162") (pin "5") (pinfunction "5_5") (pintype "passive"))
      (node (ref "K163") (pin "5") (pinfunction "5_5") (pintype "passive"))
      (node (ref "K164") (pin "5") (pinfunction "5_5") (pintype "passive"))
      (node (ref "K165") (pin "5") (pinfunction "5_5") (pintype "passive"))
      (node (ref "K166") (pin "5") (pinfunction "5_5") (pintype "passive"))
      (node (ref "K167") (pin "5") (pinfunction "5_5") (pintype "passive"))
      (node (ref "K168") (pin "5") (pinfunction "5_5") (pintype "passive"))
      (node (ref "K169") (pin "5") (pinfunction "5_5") (pintype "passive"))
      (node (ref "K17") (pin "5") (pinfunction "5_5") (pintype "passive"))
      (node (ref "K170") (pin "5") (pinfunction "5_5") (pintype "passive"))
      (node (ref "K171") (pin "5") (pinfunction "5_5") (pintype "passive"))
      (node (ref "K172") (pin "5") (pinfunction "5_5") (pintype "passive"))
      (node (ref "K173") (pin "5") (pinfunction "5_5") (pintype "passive"))
      (node (ref "K174") (pin "5") (pinfunction "5_5") (pintype "passive"))
      (node (ref "K175") (pin "5") (pinfunction "5_5") (pintype "passive"))
      (node (ref "K176") (pin "5") (pinfunction "5_5") (pintype "passive"))
      (node (ref "K177") (pin "5") (pinfunction "5_5") (pintype "passive"))
      (node (ref "K178") (pin "5") (pinfunction "5_5") (pintype "passive"))
      (node (ref "K179") (pin "5") (pinfunction "5_5") (pintype "passive"))
      (node (ref "K18") (pin "5") (pinfunction "5_5") (pintype "passive"))
      (node (ref "K180") (pin "5") (pinfunction "5_5") (pintype "passive"))
      (node (ref "K181") (pin "5") (pinfunction "5_5") (pintype "passive"))
      (node (ref "K182") (pin "5") (pinfunction "5_5") (pintype "passive"))
      (node (ref "K183") (pin "5") (pinfunction "5_5") (pintype "passive"))
      (node (ref "K184") (pin "5") (pinfunction "5_5") (pintype "passive"))
      (node (ref "K185") (pin "5") (pinfunction "5_5") (pintype "passive"))
      (node (ref "K186") (pin "5") (pinfunction "5_5") (pintype "passive"))
      (node (ref "K187") (pin "5") (pinfunction "5_5") (pintype "passive"))
      (node (ref "K188") (pin "5") (pinfunction "5_5") (pintype "passive"))
      (node (ref "K189") (pin "5") (pinfunction "5_5") (pintype "passive"))
      (node (ref "K19") (pin "5") (pinfunction "5_5") (pintype "passive"))
      (node (ref "K190") (pin "5") (pinfunction "5_5") (pintype "passive"))
      (node (ref "K191") (pin "5") (pinfunction "5_5") (pintype "passive"))
      (node (ref "K192") (pin "5") (pinfunction "5_5") (pintype "passive"))
      (node (ref "K2") (pin "5") (pinfunction "5_5") (pintype "passive"))
      (node (ref "K20") (pin "5") (pinfunction "5_5") (pintype "passive"))
      (node (ref "K21") (pin "5") (pinfunction "5_5") (pintype "passive"))
      (node (ref "K22") (pin "5") (pinfunction "5_5") (pintype "passive"))
      (node (ref "K23") (pin "5") (pinfunction "5_5") (pintype "passive"))
      (node (ref "K24") (pin "5") (pinfunction "5_5") (pintype "passive"))
      (node (ref "K25") (pin "5") (pinfunction "5_5") (pintype "passive"))
      (node (ref "K26") (pin "5") (pinfunction "5_5") (pintype "passive"))
      (node (ref "K27") (pin "5") (pinfunction "5_5") (pintype "passive"))
      (node (ref "K28") (pin "5") (pinfunction "5_5") (pintype "passive"))
      (node (ref "K29") (pin "5") (pinfunction "5_5") (pintype "passive"))
      (node (ref "K3") (pin "5") (pinfunction "5_5") (pintype "passive"))
      (node (ref "K30") (pin "5") (pinfunction "5_5") (pintype "passive"))
      (node (ref "K31") (pin "5") (pinfunction "5_5") (pintype "passive"))
      (node (ref "K32") (pin "5") (pinfunction "5_5") (pintype "passive"))
      (node (ref "K33") (pin "5") (pinfunction "5_5") (pintype "passive"))
      (node (ref "K34") (pin "5") (pinfunction "5_5") (pintype "passive"))
      (node (ref "K35") (pin "5") (pinfunction "5_5") (pintype "passive"))
      (node (ref "K36") (pin "5") (pinfunction "5_5") (pintype "passive"))
      (node (ref "K37") (pin "5") (pinfunction "5_5") (pintype "passive"))
      (node (ref "K38") (pin "5") (pinfunction "5_5") (pintype "passive"))
      (node (ref "K39") (pin "5") (pinfunction "5_5") (pintype "passive"))
      (node (ref "K4") (pin "5") (pinfunction "5_5") (pintype "passive"))
      (node (ref "K40") (pin "5") (pinfunction "5_5") (pintype "passive"))
      (node (ref "K41") (pin "5") (pinfunction "5_5") (pintype "passive"))
      (node (ref "K42") (pin "5") (pinfunction "5_5") (pintype "passive"))
      (node (ref "K43") (pin "5") (pinfunction "5_5") (pintype "passive"))
      (node (ref "K44") (pin "5") (pinfunction "5_5") (pintype "passive"))
      (node (ref "K45") (pin "5") (pinfunction "5_5") (pintype "passive"))
      (node (ref "K46") (pin "5") (pinfunction "5_5") (pintype "passive"))
      (node (ref "K47") (pin "5") (pinfunction "5_5") (pintype "passive"))
      (node (ref "K48") (pin "5") (pinfunction "5_5") (pintype "passive"))
      (node (ref "K49") (pin "5") (pinfunction "5_5") (pintype "passive"))
      (node (ref "K5") (pin "5") (pinfunction "5_5") (pintype "passive"))
      (node (ref "K50") (pin "5") (pinfunction "5_5") (pintype "passive"))
      (node (ref "K51") (pin "5") (pinfunction "5_5") (pintype "passive"))
      (node (ref "K52") (pin "5") (pinfunction "5_5") (pintype "passive"))
      (node (ref "K53") (pin "5") (pinfunction "5_5") (pintype "passive"))
      (node (ref "K54") (pin "5") (pinfunction "5_5") (pintype "passive"))
      (node (ref "K55") (pin "5") (pinfunction "5_5") (pintype "passive"))
      (node (ref "K56") (pin "5") (pinfunction "5_5") (pintype "passive"))
      (node (ref "K57") (pin "5") (pinfunction "5_5") (pintype "passive"))
      (node (ref "K58") (pin "5") (pinfunction "5_5") (pintype "passive"))
      (node (ref "K59") (pin "5") (pinfunction "5_5") (pintype "passive"))
      (node (ref "K6") (pin "5") (pinfunction "5_5") (pintype "passive"))
      (node (ref "K60") (pin "5") (pinfunction "5_5") (pintype "passive"))
      (node (ref "K61") (pin "5") (pinfunction "5_5") (pintype "passive"))
      (node (ref "K62") (pin "5") (pinfunction "5_5") (pintype "passive"))
      (node (ref "K63") (pin "5") (pinfunction "5_5") (pintype "passive"))
      (node (ref "K64") (pin "5") (pinfunction "5_5") (pintype "passive"))
      (node (ref "K65") (pin "5") (pinfunction "5_5") (pintype "passive"))
      (node (ref "K66") (pin "5") (pinfunction "5_5") (pintype "passive"))
      (node (ref "K67") (pin "5") (pinfunction "5_5") (pintype "passive"))
      (node (ref "K68") (pin "5") (pinfunction "5_5") (pintype "passive"))
      (node (ref "K69") (pin "5") (pinfunction "5_5") (pintype "passive"))
      (node (ref "K7") (pin "5") (pinfunction "5_5") (pintype "passive"))
      (node (ref "K70") (pin "5") (pinfunction "5_5") (pintype "passive"))
      (node (ref "K71") (pin "5") (pinfunction "5_5") (pintype "passive"))
      (node (ref "K72") (pin "5") (pinfunction "5_5") (pintype "passive"))
      (node (ref "K73") (pin "5") (pinfunction "5_5") (pintype "passive"))
      (node (ref "K74") (pin "5") (pinfunction "5_5") (pintype "passive"))
      (node (ref "K75") (pin "5") (pinfunction "5_5") (pintype "passive"))
      (node (ref "K76") (pin "5") (pinfunction "5_5") (pintype "passive"))
      (node (ref "K77") (pin "5") (pinfunction "5_5") (pintype "passive"))
      (node (ref "K78") (pin "5") (pinfunction "5_5") (pintype "passive"))
      (node (ref "K79") (pin "5") (pinfunction "5_5") (pintype "passive"))
      (node (ref "K8") (pin "5") (pinfunction "5_5") (pintype "passive"))
      (node (ref "K80") (pin "5") (pinfunction "5_5") (pintype "passive"))
      (node (ref "K81") (pin "5") (pinfunction "5_5") (pintype "passive"))
      (node (ref "K82") (pin "5") (pinfunction "5_5") (pintype "passive"))
      (node (ref "K83") (pin "5") (pinfunction "5_5") (pintype "passive"))
      (node (ref "K84") (pin "5") (pinfunction "5_5") (pintype "passive"))
      (node (ref "K85") (pin "5") (pinfunction "5_5") (pintype "passive"))
      (node (ref "K86") (pin "5") (pinfunction "5_5") (pintype "passive"))
      (node (ref "K87") (pin "5") (pinfunction "5_5") (pintype "passive"))
      (node (ref "K88") (pin "5") (pinfunction "5_5") (pintype "passive"))
      (node (ref "K89") (pin "5") (pinfunction "5_5") (pintype "passive"))
      (node (ref "K9") (pin "5") (pinfunction "5_5") (pintype "passive"))
      (node (ref "K90") (pin "5") (pinfunction "5_5") (pintype "passive"))
      (node (ref "K91") (pin "5") (pinfunction "5_5") (pintype "passive"))
      (node (ref "K92") (pin "5") (pinfunction "5_5") (pintype "passive"))
      (node (ref "K93") (pin "5") (pinfunction "5_5") (pintype "passive"))
      (node (ref "K94") (pin "5") (pinfunction "5_5") (pintype "passive"))
      (node (ref "K95") (pin "5") (pinfunction "5_5") (pintype "passive"))
      (node (ref "K96") (pin "5") (pinfunction "5_5") (pintype "passive"))
      (node (ref "K97") (pin "5") (pinfunction "5_5") (pintype "passive"))
      (node (ref "K98") (pin "5") (pinfunction "5_5") (pintype "passive"))
      (node (ref "K99") (pin "5") (pinfunction "5_5") (pintype "passive"))
      (node (ref "PLD1") (pin "7") (pinfunction "7_7") (pintype "passive"))
    )
    (net (code "406") (name "/QS1(data)") (class "Default")
      (node (ref "D23") (pin "9") (pinfunction "QS1_9") (pintype "passive"))
      (node (ref "PLD1") (pin "8") (pinfunction "8_8") (pintype "passive"))
    )
    (net (code "407") (name "/STR") (class "Default")
      (node (ref "D0") (pin "1") (pinfunction "STR_1") (pintype "passive"))
      (node (ref "D1") (pin "1") (pinfunction "STR_1") (pintype "passive"))
      (node (ref "D10") (pin "1") (pinfunction "STR_1") (pintype "passive"))
      (node (ref "D11") (pin "1") (pinfunction "STR_1") (pintype "passive"))
      (node (ref "D12") (pin "1") (pinfunction "STR_1") (pintype "passive"))
      (node (ref "D13") (pin "1") (pinfunction "STR_1") (pintype "passive"))
      (node (ref "D14") (pin "1") (pinfunction "STR_1") (pintype "passive"))
      (node (ref "D15") (pin "1") (pinfunction "STR_1") (pintype "passive"))
      (node (ref "D16") (pin "1") (pinfunction "STR_1") (pintype "passive"))
      (node (ref "D17") (pin "1") (pinfunction "STR_1") (pintype "passive"))
      (node (ref "D18") (pin "1") (pinfunction "STR_1") (pintype "passive"))
      (node (ref "D19") (pin "1") (pinfunction "STR_1") (pintype "passive"))
      (node (ref "D2") (pin "1") (pinfunction "STR_1") (pintype "passive"))
      (node (ref "D20") (pin "1") (pinfunction "STR_1") (pintype "passive"))
      (node (ref "D21") (pin "1") (pinfunction "STR_1") (pintype "passive"))
      (node (ref "D22") (pin "1") (pinfunction "STR_1") (pintype "passive"))
      (node (ref "D23") (pin "1") (pinfunction "STR_1") (pintype "passive"))
      (node (ref "D3") (pin "1") (pinfunction "STR_1") (pintype "passive"))
      (node (ref "D4") (pin "1") (pinfunction "STR_1") (pintype "passive"))
      (node (ref "D5") (pin "1") (pinfunction "STR_1") (pintype "passive"))
      (node (ref "D6") (pin "1") (pinfunction "STR_1") (pintype "passive"))
      (node (ref "D7") (pin "1") (pinfunction "STR_1") (pintype "passive"))
      (node (ref "D8") (pin "1") (pinfunction "STR_1") (pintype "passive"))
      (node (ref "D9") (pin "1") (pinfunction "STR_1") (pintype "passive"))
      (node (ref "PLD1") (pin "3") (pinfunction "3_3") (pintype "passive"))
    )
    (net (code "408") (name "/X1") (class "Default")
      (node (ref "K1") (pin "1") (pinfunction "1_1") (pintype "passive"))
      (node (ref "K10") (pin "1") (pinfunction "1_1") (pintype "passive"))
      (node (ref "K105") (pin "1") (pinfunction "1_1") (pintype "passive"))
      (node (ref "K106") (pin "1") (pinfunction "1_1") (pintype "passive"))
      (node (ref "K107") (pin "1") (pinfunction "1_1") (pintype "passive"))
      (node (ref "K108") (pin "1") (pinfunction "1_1") (pintype "passive"))
      (node (ref "K109") (pin "1") (pinfunction "1_1") (pintype "passive"))
      (node (ref "K11") (pin "1") (pinfunction "1_1") (pintype "passive"))
      (node (ref "K110") (pin "1") (pinfunction "1_1") (pintype "passive"))
      (node (ref "K111") (pin "1") (pinfunction "1_1") (pintype "passive"))
      (node (ref "K112") (pin "1") (pinfunction "1_1") (pintype "passive"))
      (node (ref "K12") (pin "1") (pinfunction "1_1") (pintype "passive"))
      (node (ref "K121") (pin "1") (pinfunction "1_1") (pintype "passive"))
      (node (ref "K122") (pin "1") (pinfunction "1_1") (pintype "passive"))
      (node (ref "K123") (pin "1") (pinfunction "1_1") (pintype "passive"))
      (node (ref "K124") (pin "1") (pinfunction "1_1") (pintype "passive"))
      (node (ref "K125") (pin "1") (pinfunction "1_1") (pintype "passive"))
      (node (ref "K126") (pin "1") (pinfunction "1_1") (pintype "passive"))
      (node (ref "K127") (pin "1") (pinfunction "1_1") (pintype "passive"))
      (node (ref "K128") (pin "1") (pinfunction "1_1") (pintype "passive"))
      (node (ref "K13") (pin "1") (pinfunction "1_1") (pintype "passive"))
      (node (ref "K137") (pin "1") (pinfunction "1_1") (pintype "passive"))
      (node (ref "K138") (pin "1") (pinfunction "1_1") (pintype "passive"))
      (node (ref "K139") (pin "1") (pinfunction "1_1") (pintype "passive"))
      (node (ref "K14") (pin "1") (pinfunction "1_1") (pintype "passive"))
      (node (ref "K140") (pin "1") (pinfunction "1_1") (pintype "passive"))
      (node (ref "K141") (pin "1") (pinfunction "1_1") (pintype "passive"))
      (node (ref "K142") (pin "1") (pinfunction "1_1") (pintype "passive"))
      (node (ref "K143") (pin "1") (pinfunction "1_1") (pintype "passive"))
      (node (ref "K144") (pin "1") (pinfunction "1_1") (pintype "passive"))
      (node (ref "K15") (pin "1") (pinfunction "1_1") (pintype "passive"))
      (node (ref "K153") (pin "1") (pinfunction "1_1") (pintype "passive"))
      (node (ref "K154") (pin "1") (pinfunction "1_1") (pintype "passive"))
      (node (ref "K155") (pin "1") (pinfunction "1_1") (pintype "passive"))
      (node (ref "K156") (pin "1") (pinfunction "1_1") (pintype "passive"))
      (node (ref "K16") (pin "1") (pinfunction "1_1") (pintype "passive"))
      (node (ref "K161") (pin "1") (pinfunction "1_1") (pintype "passive"))
      (node (ref "K162") (pin "1") (pinfunction "1_1") (pintype "passive"))
      (node (ref "K163") (pin "1") (pinfunction "1_1") (pintype "passive"))
      (node (ref "K164") (pin "1") (pinfunction "1_1") (pintype "passive"))
      (node (ref "K169") (pin "1") (pinfunction "1_1") (pintype "passive"))
      (node (ref "K170") (pin "1") (pinfunction "1_1") (pintype "passive"))
      (node (ref "K171") (pin "1") (pinfunction "1_1") (pintype "passive"))
      (node (ref "K172") (pin "1") (pinfunction "1_1") (pintype "passive"))
      (node (ref "K177") (pin "1") (pinfunction "1_1") (pintype "passive"))
      (node (ref "K178") (pin "1") (pinfunction "1_1") (pintype "passive"))
      (node (ref "K179") (pin "1") (pinfunction "1_1") (pintype "passive"))
      (node (ref "K180") (pin "1") (pinfunction "1_1") (pintype "passive"))
      (node (ref "K185") (pin "1") (pinfunction "1_1") (pintype "passive"))
      (node (ref "K186") (pin "1") (pinfunction "1_1") (pintype "passive"))
      (node (ref "K187") (pin "1") (pinfunction "1_1") (pintype "passive"))
      (node (ref "K188") (pin "1") (pinfunction "1_1") (pintype "passive"))
      (node (ref "K2") (pin "1") (pinfunction "1_1") (pintype "passive"))
      (node (ref "K25") (pin "1") (pinfunction "1_1") (pintype "passive"))
      (node (ref "K26") (pin "1") (pinfunction "1_1") (pintype "passive"))
      (node (ref "K27") (pin "1") (pinfunction "1_1") (pintype "passive"))
      (node (ref "K28") (pin "1") (pinfunction "1_1") (pintype "passive"))
      (node (ref "K29") (pin "1") (pinfunction "1_1") (pintype "passive"))
      (node (ref "K3") (pin "1") (pinfunction "1_1") (pintype "passive"))
      (node (ref "K30") (pin "1") (pinfunction "1_1") (pintype "passive"))
      (node (ref "K31") (pin "1") (pinfunction "1_1") (pintype "passive"))
      (node (ref "K32") (pin "1") (pinfunction "1_1") (pintype "passive"))
      (node (ref "K4") (pin "1") (pinfunction "1_1") (pintype "passive"))
      (node (ref "K41") (pin "1") (pinfunction "1_1") (pintype "passive"))
      (node (ref "K42") (pin "1") (pinfunction "1_1") (pintype "passive"))
      (node (ref "K43") (pin "1") (pinfunction "1_1") (pintype "passive"))
      (node (ref "K44") (pin "1") (pinfunction "1_1") (pintype "passive"))
      (node (ref "K45") (pin "1") (pinfunction "1_1") (pintype "passive"))
      (node (ref "K46") (pin "1") (pinfunction "1_1") (pintype "passive"))
      (node (ref "K47") (pin "1") (pinfunction "1_1") (pintype "passive"))
      (node (ref "K48") (pin "1") (pinfunction "1_1") (pintype "passive"))
      (node (ref "K57") (pin "1") (pinfunction "1_1") (pintype "passive"))
      (node (ref "K58") (pin "1") (pinfunction "1_1") (pintype "passive"))
      (node (ref "K59") (pin "1") (pinfunction "1_1") (pintype "passive"))
      (node (ref "K60") (pin "1") (pinfunction "1_1") (pintype "passive"))
      (node (ref "K65") (pin "1") (pinfunction "1_1") (pintype "passive"))
      (node (ref "K66") (pin "1") (pinfunction "1_1") (pintype "passive"))
      (node (ref "K67") (pin "1") (pinfunction "1_1") (pintype "passive"))
      (node (ref "K68") (pin "1") (pinfunction "1_1") (pintype "passive"))
      (node (ref "K73") (pin "1") (pinfunction "1_1") (pintype "passive"))
      (node (ref "K74") (pin "1") (pinfunction "1_1") (pintype "passive"))
      (node (ref "K75") (pin "1") (pinfunction "1_1") (pintype "passive"))
      (node (ref "K76") (pin "1") (pinfunction "1_1") (pintype "passive"))
      (node (ref "K81") (pin "1") (pinfunction "1_1") (pintype "passive"))
      (node (ref "K82") (pin "1") (pinfunction "1_1") (pintype "passive"))
      (node (ref "K83") (pin "1") (pinfunction "1_1") (pintype "passive"))
      (node (ref "K84") (pin "1") (pinfunction "1_1") (pintype "passive"))
      (node (ref "K89") (pin "1") (pinfunction "1_1") (pintype "passive"))
      (node (ref "K9") (pin "1") (pinfunction "1_1") (pintype "passive"))
      (node (ref "K90") (pin "1") (pinfunction "1_1") (pintype "passive"))
      (node (ref "K91") (pin "1") (pinfunction "1_1") (pintype "passive"))
      (node (ref "K92") (pin "1") (pinfunction "1_1") (pintype "passive"))
      (node (ref "K93") (pin "1") (pinfunction "1_1") (pintype "passive"))
      (node (ref "K94") (pin "1") (pinfunction "1_1") (pintype "passive"))
      (node (ref "K95") (pin "1") (pinfunction "1_1") (pintype "passive"))
      (node (ref "K96") (pin "1") (pinfunction "1_1") (pintype "passive"))
      (node (ref "PLD1") (pin "5") (pinfunction "5_5") (pintype "passive"))
    )
    (net (code "409") (name "/X2") (class "Default")
      (node (ref "K100") (pin "1") (pinfunction "1_1") (pintype "passive"))
      (node (ref "K101") (pin "1") (pinfunction "1_1") (pintype "passive"))
      (node (ref "K102") (pin "1") (pinfunction "1_1") (pintype "passive"))
      (node (ref "K103") (pin "1") (pinfunction "1_1") (pintype "passive"))
      (node (ref "K104") (pin "1") (pinfunction "1_1") (pintype "passive"))
      (node (ref "K113") (pin "1") (pinfunction "1_1") (pintype "passive"))
      (node (ref "K114") (pin "1") (pinfunction "1_1") (pintype "passive"))
      (node (ref "K115") (pin "1") (pinfunction "1_1") (pintype "passive"))
      (node (ref "K116") (pin "1") (pinfunction "1_1") (pintype "passive"))
      (node (ref "K117") (pin "1") (pinfunction "1_1") (pintype "passive"))
      (node (ref "K118") (pin "1") (pinfunction "1_1") (pintype "passive"))
      (node (ref "K119") (pin "1") (pinfunction "1_1") (pintype "passive"))
      (node (ref "K120") (pin "1") (pinfunction "1_1") (pintype "passive"))
      (node (ref "K129") (pin "1") (pinfunction "1_1") (pintype "passive"))
      (node (ref "K130") (pin "1") (pinfunction "1_1") (pintype "passive"))
      (node (ref "K131") (pin "1") (pinfunction "1_1") (pintype "passive"))
      (node (ref "K132") (pin "1") (pinfunction "1_1") (pintype "passive"))
      (node (ref "K133") (pin "1") (pinfunction "1_1") (pintype "passive"))
      (node (ref "K134") (pin "1") (pinfunction "1_1") (pintype "passive"))
      (node (ref "K135") (pin "1") (pinfunction "1_1") (pintype "passive"))
      (node (ref "K136") (pin "1") (pinfunction "1_1") (pintype "passive"))
      (node (ref "K145") (pin "1") (pinfunction "1_1") (pintype "passive"))
      (node (ref "K146") (pin "1") (pinfunction "1_1") (pintype "passive"))
      (node (ref "K147") (pin "1") (pinfunction "1_1") (pintype "passive"))
      (node (ref "K148") (pin "1") (pinfunction "1_1") (pintype "passive"))
      (node (ref "K149") (pin "1") (pinfunction "1_1") (pintype "passive"))
      (node (ref "K150") (pin "1") (pinfunction "1_1") (pintype "passive"))
      (node (ref "K151") (pin "1") (pinfunction "1_1") (pintype "passive"))
      (node (ref "K152") (pin "1") (pinfunction "1_1") (pintype "passive"))
      (node (ref "K157") (pin "1") (pinfunction "1_1") (pintype "passive"))
      (node (ref "K158") (pin "1") (pinfunction "1_1") (pintype "passive"))
      (node (ref "K159") (pin "1") (pinfunction "1_1") (pintype "passive"))
      (node (ref "K160") (pin "1") (pinfunction "1_1") (pintype "passive"))
      (node (ref "K165") (pin "1") (pinfunction "1_1") (pintype "passive"))
      (node (ref "K166") (pin "1") (pinfunction "1_1") (pintype "passive"))
      (node (ref "K167") (pin "1") (pinfunction "1_1") (pintype "passive"))
      (node (ref "K168") (pin "1") (pinfunction "1_1") (pintype "passive"))
      (node (ref "K17") (pin "1") (pinfunction "1_1") (pintype "passive"))
      (node (ref "K173") (pin "1") (pinfunction "1_1") (pintype "passive"))
      (node (ref "K174") (pin "1") (pinfunction "1_1") (pintype "passive"))
      (node (ref "K175") (pin "1") (pinfunction "1_1") (pintype "passive"))
      (node (ref "K176") (pin "1") (pinfunction "1_1") (pintype "passive"))
      (node (ref "K18") (pin "1") (pinfunction "1_1") (pintype "passive"))
      (node (ref "K181") (pin "1") (pinfunction "1_1") (pintype "passive"))
      (node (ref "K182") (pin "1") (pinfunction "1_1") (pintype "passive"))
      (node (ref "K183") (pin "1") (pinfunction "1_1") (pintype "passive"))
      (node (ref "K184") (pin "1") (pinfunction "1_1") (pintype "passive"))
      (node (ref "K189") (pin "1") (pinfunction "1_1") (pintype "passive"))
      (node (ref "K19") (pin "1") (pinfunction "1_1") (pintype "passive"))
      (node (ref "K190") (pin "1") (pinfunction "1_1") (pintype "passive"))
      (node (ref "K191") (pin "1") (pinfunction "1_1") (pintype "passive"))
      (node (ref "K192") (pin "1") (pinfunction "1_1") (pintype "passive"))
      (node (ref "K20") (pin "1") (pinfunction "1_1") (pintype "passive"))
      (node (ref "K21") (pin "1") (pinfunction "1_1") (pintype "passive"))
      (node (ref "K22") (pin "1") (pinfunction "1_1") (pintype "passive"))
      (node (ref "K23") (pin "1") (pinfunction "1_1") (pintype "passive"))
      (node (ref "K24") (pin "1") (pinfunction "1_1") (pintype "passive"))
      (node (ref "K33") (pin "1") (pinfunction "1_1") (pintype "passive"))
      (node (ref "K34") (pin "1") (pinfunction "1_1") (pintype "passive"))
      (node (ref "K35") (pin "1") (pinfunction "1_1") (pintype "passive"))
      (node (ref "K36") (pin "1") (pinfunction "1_1") (pintype "passive"))
      (node (ref "K37") (pin "1") (pinfunction "1_1") (pintype "passive"))
      (node (ref "K38") (pin "1") (pinfunction "1_1") (pintype "passive"))
      (node (ref "K39") (pin "1") (pinfunction "1_1") (pintype "passive"))
      (node (ref "K40") (pin "1") (pinfunction "1_1") (pintype "passive"))
      (node (ref "K49") (pin "1") (pinfunction "1_1") (pintype "passive"))
      (node (ref "K5") (pin "1") (pinfunction "1_1") (pintype "passive"))
      (node (ref "K50") (pin "1") (pinfunction "1_1") (pintype "passive"))
      (node (ref "K51") (pin "1") (pinfunction "1_1") (pintype "passive"))
      (node (ref "K52") (pin "1") (pinfunction "1_1") (pintype "passive"))
      (node (ref "K53") (pin "1") (pinfunction "1_1") (pintype "passive"))
      (node (ref "K54") (pin "1") (pinfunction "1_1") (pintype "passive"))
      (node (ref "K55") (pin "1") (pinfunction "1_1") (pintype "passive"))
      (node (ref "K56") (pin "1") (pinfunction "1_1") (pintype "passive"))
      (node (ref "K6") (pin "1") (pinfunction "1_1") (pintype "passive"))
      (node (ref "K61") (pin "1") (pinfunction "1_1") (pintype "passive"))
      (node (ref "K62") (pin "1") (pinfunction "1_1") (pintype "passive"))
      (node (ref "K63") (pin "1") (pinfunction "1_1") (pintype "passive"))
      (node (ref "K64") (pin "1") (pinfunction "1_1") (pintype "passive"))
      (node (ref "K69") (pin "1") (pinfunction "1_1") (pintype "passive"))
      (node (ref "K7") (pin "1") (pinfunction "1_1") (pintype "passive"))
      (node (ref "K70") (pin "1") (pinfunction "1_1") (pintype "passive"))
      (node (ref "K71") (pin "1") (pinfunction "1_1") (pintype "passive"))
      (node (ref "K72") (pin "1") (pinfunction "1_1") (pintype "passive"))
      (node (ref "K77") (pin "1") (pinfunction "1_1") (pintype "passive"))
      (node (ref "K78") (pin "1") (pinfunction "1_1") (pintype "passive"))
      (node (ref "K79") (pin "1") (pinfunction "1_1") (pintype "passive"))
      (node (ref "K8") (pin "1") (pinfunction "1_1") (pintype "passive"))
      (node (ref "K80") (pin "1") (pinfunction "1_1") (pintype "passive"))
      (node (ref "K85") (pin "1") (pinfunction "1_1") (pintype "passive"))
      (node (ref "K86") (pin "1") (pinfunction "1_1") (pintype "passive"))
      (node (ref "K87") (pin "1") (pinfunction "1_1") (pintype "passive"))
      (node (ref "K88") (pin "1") (pinfunction "1_1") (pintype "passive"))
      (node (ref "K97") (pin "1") (pinfunction "1_1") (pintype "passive"))
      (node (ref "K98") (pin "1") (pinfunction "1_1") (pintype "passive"))
      (node (ref "K99") (pin "1") (pinfunction "1_1") (pintype "passive"))
      (node (ref "PLD1") (pin "6") (pinfunction "6_6") (pintype "passive"))
    )
    (net (code "410") (name "/Y0") (class "Default")
      (node (ref "K4") (pin "7") (pinfunction "7_7") (pintype "passive"))
      (node (ref "K8") (pin "7") (pinfunction "7_7") (pintype "passive"))
      (node (ref "L1") (pin "1") (pinfunction "1_1") (pintype "passive"))
    )
    (net (code "411") (name "/Y2") (class "Default")
      (node (ref "K3") (pin "7") (pinfunction "7_7") (pintype "passive"))
      (node (ref "K7") (pin "7") (pinfunction "7_7") (pintype "passive"))
      (node (ref "L1") (pin "2") (pinfunction "2_2") (pintype "passive"))
    )
    (net (code "412") (name "/Y4") (class "Default")
      (node (ref "K2") (pin "7") (pinfunction "7_7") (pintype "passive"))
      (node (ref "K6") (pin "7") (pinfunction "7_7") (pintype "passive"))
      (node (ref "L1") (pin "3") (pinfunction "3_3") (pintype "passive"))
    )
    (net (code "413") (name "/Y6") (class "Default")
      (node (ref "K1") (pin "7") (pinfunction "7_7") (pintype "passive"))
      (node (ref "K5") (pin "7") (pinfunction "7_7") (pintype "passive"))
      (node (ref "L1") (pin "4") (pinfunction "4_4") (pintype "passive"))
    )
    (net (code "414") (name "/Y8") (class "Default")
      (node (ref "K12") (pin "7") (pinfunction "7_7") (pintype "passive"))
      (node (ref "K20") (pin "7") (pinfunction "7_7") (pintype "passive"))
      (node (ref "L1") (pin "5") (pinfunction "5_5") (pintype "passive"))
    )
    (net (code "415") (name "/Y10") (class "Default")
      (node (ref "K11") (pin "7") (pinfunction "7_7") (pintype "passive"))
      (node (ref "K19") (pin "7") (pinfunction "7_7") (pintype "passive"))
      (node (ref "L1") (pin "6") (pinfunction "6_6") (pintype "passive"))
    )
    (net (code "416") (name "/Y12") (class "Default")
      (node (ref "K10") (pin "7") (pinfunction "7_7") (pintype "passive"))
      (node (ref "K18") (pin "7") (pinfunction "7_7") (pintype "passive"))
      (node (ref "L1") (pin "7") (pinfunction "7_7") (pintype "passive"))
    )
    (net (code "417") (name "/Y14") (class "Default")
      (node (ref "K17") (pin "7") (pinfunction "7_7") (pintype "passive"))
      (node (ref "K9") (pin "7") (pinfunction "7_7") (pintype "passive"))
      (node (ref "L1") (pin "8") (pinfunction "8_8") (pintype "passive"))
    )
    (net (code "418") (name "/Y16") (class "Default")
      (node (ref "K16") (pin "7") (pinfunction "7_7") (pintype "passive"))
      (node (ref "K24") (pin "7") (pinfunction "7_7") (pintype "passive"))
      (node (ref "L1") (pin "9") (pinfunction "9_9") (pintype "passive"))
    )
    (net (code "419") (name "/Y18") (class "Default")
      (node (ref "K15") (pin "7") (pinfunction "7_7") (pintype "passive"))
      (node (ref "K23") (pin "7") (pinfunction "7_7") (pintype "passive"))
      (node (ref "L1") (pin "10") (pinfunction "10_10") (pintype "passive"))
    )
    (net (code "420") (name "/Y20") (class "Default")
      (node (ref "K14") (pin "7") (pinfunction "7_7") (pintype "passive"))
      (node (ref "K22") (pin "7") (pinfunction "7_7") (pintype "passive"))
      (node (ref "L1") (pin "11") (pinfunction "11_11") (pintype "passive"))
    )
    (net (code "421") (name "/Y22") (class "Default")
      (node (ref "K13") (pin "7") (pinfunction "7_7") (pintype "passive"))
      (node (ref "K21") (pin "7") (pinfunction "7_7") (pintype "passive"))
      (node (ref "L1") (pin "12") (pinfunction "12_12") (pintype "passive"))
    )
    (net (code "422") (name "/Y24") (class "Default")
      (node (ref "K28") (pin "7") (pinfunction "7_7") (pintype "passive"))
      (node (ref "K36") (pin "7") (pinfunction "7_7") (pintype "passive"))
      (node (ref "L1") (pin "13") (pinfunction "13_13") (pintype "passive"))
    )
    (net (code "423") (name "/Y26") (class "Default")
      (node (ref "K27") (pin "7") (pinfunction "7_7") (pintype "passive"))
      (node (ref "K35") (pin "7") (pinfunction "7_7") (pintype "passive"))
      (node (ref "L1") (pin "14") (pinfunction "14_14") (pintype "passive"))
    )
    (net (code "424") (name "/Y28") (class "Default")
      (node (ref "K26") (pin "7") (pinfunction "7_7") (pintype "passive"))
      (node (ref "K34") (pin "7") (pinfunction "7_7") (pintype "passive"))
      (node (ref "L1") (pin "15") (pinfunction "15_15") (pintype "passive"))
    )
    (net (code "425") (name "/Y30") (class "Default")
      (node (ref "K25") (pin "7") (pinfunction "7_7") (pintype "passive"))
      (node (ref "K33") (pin "7") (pinfunction "7_7") (pintype "passive"))
      (node (ref "L1") (pin "16") (pinfunction "16_16") (pintype "passive"))
    )
    (net (code "426") (name "/Y32") (class "Default")
      (node (ref "K32") (pin "7") (pinfunction "7_7") (pintype "passive"))
      (node (ref "K40") (pin "7") (pinfunction "7_7") (pintype "passive"))
      (node (ref "L1") (pin "17") (pinfunction "17_17") (pintype "passive"))
    )
    (net (code "427") (name "/Y34") (class "Default")
      (node (ref "K31") (pin "7") (pinfunction "7_7") (pintype "passive"))
      (node (ref "K39") (pin "7") (pinfunction "7_7") (pintype "passive"))
      (node (ref "L1") (pin "18") (pinfunction "18_18") (pintype "passive"))
    )
    (net (code "428") (name "/Y36") (class "Default")
      (node (ref "K30") (pin "7") (pinfunction "7_7") (pintype "passive"))
      (node (ref "K38") (pin "7") (pinfunction "7_7") (pintype "passive"))
      (node (ref "L1") (pin "19") (pinfunction "19_19") (pintype "passive"))
    )
    (net (code "429") (name "/Y38") (class "Default")
      (node (ref "K29") (pin "7") (pinfunction "7_7") (pintype "passive"))
      (node (ref "K37") (pin "7") (pinfunction "7_7") (pintype "passive"))
      (node (ref "L1") (pin "20") (pinfunction "20_20") (pintype "passive"))
    )
    (net (code "430") (name "/Y40") (class "Default")
      (node (ref "K44") (pin "7") (pinfunction "7_7") (pintype "passive"))
      (node (ref "K52") (pin "7") (pinfunction "7_7") (pintype "passive"))
      (node (ref "L1") (pin "21") (pinfunction "21_21") (pintype "passive"))
    )
    (net (code "431") (name "/Y42") (class "Default")
      (node (ref "K43") (pin "7") (pinfunction "7_7") (pintype "passive"))
      (node (ref "K51") (pin "7") (pinfunction "7_7") (pintype "passive"))
      (node (ref "L1") (pin "22") (pinfunction "22_22") (pintype "passive"))
    )
    (net (code "432") (name "/Y44") (class "Default")
      (node (ref "K42") (pin "7") (pinfunction "7_7") (pintype "passive"))
      (node (ref "K50") (pin "7") (pinfunction "7_7") (pintype "passive"))
      (node (ref "L1") (pin "23") (pinfunction "23_23") (pintype "passive"))
    )
    (net (code "433") (name "/Y46") (class "Default")
      (node (ref "K41") (pin "7") (pinfunction "7_7") (pintype "passive"))
      (node (ref "K49") (pin "7") (pinfunction "7_7") (pintype "passive"))
      (node (ref "L1") (pin "24") (pinfunction "24_24") (pintype "passive"))
    )
    (net (code "434") (name "/Y48") (class "Default")
      (node (ref "K48") (pin "7") (pinfunction "7_7") (pintype "passive"))
      (node (ref "K56") (pin "7") (pinfunction "7_7") (pintype "passive"))
      (node (ref "L1") (pin "25") (pinfunction "25_25") (pintype "passive"))
    )
    (net (code "435") (name "/Y50") (class "Default")
      (node (ref "K47") (pin "7") (pinfunction "7_7") (pintype "passive"))
      (node (ref "K55") (pin "7") (pinfunction "7_7") (pintype "passive"))
      (node (ref "L1") (pin "26") (pinfunction "26_26") (pintype "passive"))
    )
    (net (code "436") (name "/Y52") (class "Default")
      (node (ref "K46") (pin "7") (pinfunction "7_7") (pintype "passive"))
      (node (ref "K54") (pin "7") (pinfunction "7_7") (pintype "passive"))
      (node (ref "L1") (pin "27") (pinfunction "27_27") (pintype "passive"))
    )
    (net (code "437") (name "/Y54") (class "Default")
      (node (ref "K45") (pin "7") (pinfunction "7_7") (pintype "passive"))
      (node (ref "K53") (pin "7") (pinfunction "7_7") (pintype "passive"))
      (node (ref "L1") (pin "28") (pinfunction "28_28") (pintype "passive"))
    )
    (net (code "438") (name "/Y56") (class "Default")
      (node (ref "K60") (pin "7") (pinfunction "7_7") (pintype "passive"))
      (node (ref "K64") (pin "7") (pinfunction "7_7") (pintype "passive"))
      (node (ref "L1") (pin "29") (pinfunction "29_29") (pintype "passive"))
    )
    (net (code "439") (name "/Y58") (class "Default")
      (node (ref "K59") (pin "7") (pinfunction "7_7") (pintype "passive"))
      (node (ref "K63") (pin "7") (pinfunction "7_7") (pintype "passive"))
      (node (ref "L1") (pin "30") (pinfunction "30_30") (pintype "passive"))
    )
    (net (code "440") (name "/Y60") (class "Default")
      (node (ref "K58") (pin "7") (pinfunction "7_7") (pintype "passive"))
      (node (ref "K62") (pin "7") (pinfunction "7_7") (pintype "passive"))
      (node (ref "L1") (pin "31") (pinfunction "31_31") (pintype "passive"))
    )
    (net (code "441") (name "/Y62") (class "Default")
      (node (ref "K57") (pin "7") (pinfunction "7_7") (pintype "passive"))
      (node (ref "K61") (pin "7") (pinfunction "7_7") (pintype "passive"))
      (node (ref "L1") (pin "32") (pinfunction "32_32") (pintype "passive"))
    )
    (net (code "442") (name "/Y64") (class "Default")
      (node (ref "K68") (pin "7") (pinfunction "7_7") (pintype "passive"))
      (node (ref "K72") (pin "7") (pinfunction "7_7") (pintype "passive"))
      (node (ref "L1") (pin "33") (pinfunction "33_33") (pintype "passive"))
    )
    (net (code "443") (name "/Y66") (class "Default")
      (node (ref "K67") (pin "7") (pinfunction "7_7") (pintype "passive"))
      (node (ref "K71") (pin "7") (pinfunction "7_7") (pintype "passive"))
      (node (ref "L1") (pin "34") (pinfunction "34_34") (pintype "passive"))
    )
    (net (code "444") (name "/Y68") (class "Default")
      (node (ref "K66") (pin "7") (pinfunction "7_7") (pintype "passive"))
      (node (ref "K70") (pin "7") (pinfunction "7_7") (pintype "passive"))
      (node (ref "L1") (pin "35") (pinfunction "35_35") (pintype "passive"))
    )
    (net (code "445") (name "/Y70") (class "Default")
      (node (ref "K65") (pin "7") (pinfunction "7_7") (pintype "passive"))
      (node (ref "K69") (pin "7") (pinfunction "7_7") (pintype "passive"))
      (node (ref "L1") (pin "36") (pinfunction "36_36") (pintype "passive"))
    )
    (net (code "446") (name "/Y72") (class "Default")
      (node (ref "K76") (pin "7") (pinfunction "7_7") (pintype "passive"))
      (node (ref "K80") (pin "7") (pinfunction "7_7") (pintype "passive"))
      (node (ref "L1") (pin "37") (pinfunction "37_37") (pintype "passive"))
    )
    (net (code "447") (name "/Y74") (class "Default")
      (node (ref "K75") (pin "7") (pinfunction "7_7") (pintype "passive"))
      (node (ref "K79") (pin "7") (pinfunction "7_7") (pintype "passive"))
      (node (ref "L1") (pin "38") (pinfunction "38_38") (pintype "passive"))
    )
    (net (code "448") (name "/Y76") (class "Default")
      (node (ref "K74") (pin "7") (pinfunction "7_7") (pintype "passive"))
      (node (ref "K78") (pin "7") (pinfunction "7_7") (pintype "passive"))
      (node (ref "L1") (pin "39") (pinfunction "39_39") (pintype "passive"))
    )
    (net (code "449") (name "/Y78") (class "Default")
      (node (ref "K73") (pin "7") (pinfunction "7_7") (pintype "passive"))
      (node (ref "K77") (pin "7") (pinfunction "7_7") (pintype "passive"))
      (node (ref "L1") (pin "40") (pinfunction "40_40") (pintype "passive"))
    )
    (net (code "450") (name "/Y80") (class "Default")
      (node (ref "K84") (pin "7") (pinfunction "7_7") (pintype "passive"))
      (node (ref "K88") (pin "7") (pinfunction "7_7") (pintype "passive"))
      (node (ref "L1") (pin "41") (pinfunction "41_41") (pintype "passive"))
    )
    (net (code "451") (name "/Y82") (class "Default")
      (node (ref "K83") (pin "7") (pinfunction "7_7") (pintype "passive"))
      (node (ref "K87") (pin "7") (pinfunction "7_7") (pintype "passive"))
      (node (ref "L1") (pin "42") (pinfunction "42_42") (pintype "passive"))
    )
    (net (code "452") (name "/Y84") (class "Default")
      (node (ref "K82") (pin "7") (pinfunction "7_7") (pintype "passive"))
      (node (ref "K86") (pin "7") (pinfunction "7_7") (pintype "passive"))
      (node (ref "L1") (pin "43") (pinfunction "43_43") (pintype "passive"))
    )
    (net (code "453") (name "/Y86") (class "Default")
      (node (ref "K81") (pin "7") (pinfunction "7_7") (pintype "passive"))
      (node (ref "K85") (pin "7") (pinfunction "7_7") (pintype "passive"))
      (node (ref "L1") (pin "44") (pinfunction "44_44") (pintype "passive"))
    )
    (net (code "454") (name "/Y88") (class "Default")
      (node (ref "K100") (pin "7") (pinfunction "7_7") (pintype "passive"))
      (node (ref "K92") (pin "7") (pinfunction "7_7") (pintype "passive"))
      (node (ref "L1") (pin "45") (pinfunction "45_45") (pintype "passive"))
    )
    (net (code "455") (name "/Y90") (class "Default")
      (node (ref "K91") (pin "7") (pinfunction "7_7") (pintype "passive"))
      (node (ref "K99") (pin "7") (pinfunction "7_7") (pintype "passive"))
      (node (ref "L1") (pin "46") (pinfunction "46_46") (pintype "passive"))
    )
    (net (code "456") (name "/Y92") (class "Default")
      (node (ref "K90") (pin "7") (pinfunction "7_7") (pintype "passive"))
      (node (ref "K98") (pin "7") (pinfunction "7_7") (pintype "passive"))
      (node (ref "L1") (pin "47") (pinfunction "47_47") (pintype "passive"))
    )
    (net (code "457") (name "/Y94") (class "Default")
      (node (ref "K89") (pin "7") (pinfunction "7_7") (pintype "passive"))
      (node (ref "K97") (pin "7") (pinfunction "7_7") (pintype "passive"))
      (node (ref "L1") (pin "48") (pinfunction "48_48") (pintype "passive"))
    )
    (net (code "458") (name "/Y96") (class "Default")
      (node (ref "K104") (pin "7") (pinfunction "7_7") (pintype "passive"))
      (node (ref "K96") (pin "7") (pinfunction "7_7") (pintype "passive"))
      (node (ref "L1") (pin "49") (pinfunction "49_49") (pintype "passive"))
    )
    (net (code "459") (name "/Y98") (class "Default")
      (node (ref "K103") (pin "7") (pinfunction "7_7") (pintype "passive"))
      (node (ref "K95") (pin "7") (pinfunction "7_7") (pintype "passive"))
      (node (ref "L1") (pin "50") (pinfunction "50_50") (pintype "passive"))
    )
    (net (code "460") (name "/Y100") (class "Default")
      (node (ref "K102") (pin "7") (pinfunction "7_7") (pintype "passive"))
      (node (ref "K94") (pin "7") (pinfunction "7_7") (pintype "passive"))
      (node (ref "L1") (pin "51") (pinfunction "51_51") (pintype "passive"))
    )
    (net (code "461") (name "/Y102") (class "Default")
      (node (ref "K101") (pin "7") (pinfunction "7_7") (pintype "passive"))
      (node (ref "K93") (pin "7") (pinfunction "7_7") (pintype "passive"))
      (node (ref "L1") (pin "52") (pinfunction "52_52") (pintype "passive"))
    )
    (net (code "462") (name "/Y104") (class "Default")
      (node (ref "K108") (pin "7") (pinfunction "7_7") (pintype "passive"))
      (node (ref "K116") (pin "7") (pinfunction "7_7") (pintype "passive"))
      (node (ref "L1") (pin "53") (pinfunction "53_53") (pintype "passive"))
    )
    (net (code "463") (name "/Y106") (class "Default")
      (node (ref "K107") (pin "7") (pinfunction "7_7") (pintype "passive"))
      (node (ref "K115") (pin "7") (pinfunction "7_7") (pintype "passive"))
      (node (ref "L1") (pin "54") (pinfunction "54_54") (pintype "passive"))
    )
    (net (code "464") (name "/Y108") (class "Default")
      (node (ref "K106") (pin "7") (pinfunction "7_7") (pintype "passive"))
      (node (ref "K114") (pin "7") (pinfunction "7_7") (pintype "passive"))
      (node (ref "L1") (pin "55") (pinfunction "55_55") (pintype "passive"))
    )
    (net (code "465") (name "/Y110") (class "Default")
      (node (ref "K105") (pin "7") (pinfunction "7_7") (pintype "passive"))
      (node (ref "K113") (pin "7") (pinfunction "7_7") (pintype "passive"))
      (node (ref "L1") (pin "56") (pinfunction "56_56") (pintype "passive"))
    )
    (net (code "466") (name "/Y112") (class "Default")
      (node (ref "K112") (pin "7") (pinfunction "7_7") (pintype "passive"))
      (node (ref "K120") (pin "7") (pinfunction "7_7") (pintype "passive"))
      (node (ref "L1") (pin "57") (pinfunction "57_57") (pintype "passive"))
    )
    (net (code "467") (name "/Y114") (class "Default")
      (node (ref "K111") (pin "7") (pinfunction "7_7") (pintype "passive"))
      (node (ref "K119") (pin "7") (pinfunction "7_7") (pintype "passive"))
      (node (ref "L1") (pin "58") (pinfunction "58_58") (pintype "passive"))
    )
    (net (code "468") (name "/Y116") (class "Default")
      (node (ref "K110") (pin "7") (pinfunction "7_7") (pintype "passive"))
      (node (ref "K118") (pin "7") (pinfunction "7_7") (pintype "passive"))
      (node (ref "L1") (pin "59") (pinfunction "59_59") (pintype "passive"))
    )
    (net (code "469") (name "/Y118") (class "Default")
      (node (ref "K109") (pin "7") (pinfunction "7_7") (pintype "passive"))
      (node (ref "K117") (pin "7") (pinfunction "7_7") (pintype "passive"))
      (node (ref "L1") (pin "60") (pinfunction "60_60") (pintype "passive"))
    )
    (net (code "470") (name "/Y120") (class "Default")
      (node (ref "K124") (pin "7") (pinfunction "7_7") (pintype "passive"))
      (node (ref "K132") (pin "7") (pinfunction "7_7") (pintype "passive"))
      (node (ref "L1") (pin "61") (pinfunction "61_61") (pintype "passive"))
    )
    (net (code "471") (name "/Y122") (class "Default")
      (node (ref "K123") (pin "7") (pinfunction "7_7") (pintype "passive"))
      (node (ref "K131") (pin "7") (pinfunction "7_7") (pintype "passive"))
      (node (ref "L1") (pin "62") (pinfunction "62_62") (pintype "passive"))
    )
    (net (code "472") (name "/Y124") (class "Default")
      (node (ref "K122") (pin "7") (pinfunction "7_7") (pintype "passive"))
      (node (ref "K130") (pin "7") (pinfunction "7_7") (pintype "passive"))
      (node (ref "L1") (pin "63") (pinfunction "63_63") (pintype "passive"))
    )
    (net (code "473") (name "/Y126") (class "Default")
      (node (ref "K121") (pin "7") (pinfunction "7_7") (pintype "passive"))
      (node (ref "K129") (pin "7") (pinfunction "7_7") (pintype "passive"))
      (node (ref "L1") (pin "64") (pinfunction "64_64") (pintype "passive"))
    )
    (net (code "474") (name "/Y128") (class "Default")
      (node (ref "K128") (pin "7") (pinfunction "7_7") (pintype "passive"))
      (node (ref "K136") (pin "7") (pinfunction "7_7") (pintype "passive"))
      (node (ref "L1") (pin "65") (pinfunction "65_65") (pintype "passive"))
    )
    (net (code "475") (name "/Y130") (class "Default")
      (node (ref "K127") (pin "7") (pinfunction "7_7") (pintype "passive"))
      (node (ref "K135") (pin "7") (pinfunction "7_7") (pintype "passive"))
      (node (ref "L1") (pin "66") (pinfunction "66_66") (pintype "passive"))
    )
    (net (code "476") (name "/Y132") (class "Default")
      (node (ref "K126") (pin "7") (pinfunction "7_7") (pintype "passive"))
      (node (ref "K134") (pin "7") (pinfunction "7_7") (pintype "passive"))
      (node (ref "L1") (pin "67") (pinfunction "67_67") (pintype "passive"))
    )
    (net (code "477") (name "/Y134") (class "Default")
      (node (ref "K125") (pin "7") (pinfunction "7_7") (pintype "passive"))
      (node (ref "K133") (pin "7") (pinfunction "7_7") (pintype "passive"))
      (node (ref "L1") (pin "68") (pinfunction "68_68") (pintype "passive"))
    )
    (net (code "478") (name "/Y136") (class "Default")
      (node (ref "K140") (pin "7") (pinfunction "7_7") (pintype "passive"))
      (node (ref "K148") (pin "7") (pinfunction "7_7") (pintype "passive"))
      (node (ref "L1") (pin "69") (pinfunction "69_69") (pintype "passive"))
    )
    (net (code "479") (name "/Y138") (class "Default")
      (node (ref "K139") (pin "7") (pinfunction "7_7") (pintype "passive"))
      (node (ref "K147") (pin "7") (pinfunction "7_7") (pintype "passive"))
      (node (ref "L1") (pin "70") (pinfunction "70_70") (pintype "passive"))
    )
    (net (code "480") (name "/Y140") (class "Default")
      (node (ref "K138") (pin "7") (pinfunction "7_7") (pintype "passive"))
      (node (ref "K146") (pin "7") (pinfunction "7_7") (pintype "passive"))
      (node (ref "L1") (pin "71") (pinfunction "71_71") (pintype "passive"))
    )
    (net (code "481") (name "/Y142") (class "Default")
      (node (ref "K137") (pin "7") (pinfunction "7_7") (pintype "passive"))
      (node (ref "K145") (pin "7") (pinfunction "7_7") (pintype "passive"))
      (node (ref "L1") (pin "72") (pinfunction "72_72") (pintype "passive"))
    )
    (net (code "482") (name "/Y144") (class "Default")
      (node (ref "K144") (pin "7") (pinfunction "7_7") (pintype "passive"))
      (node (ref "K152") (pin "7") (pinfunction "7_7") (pintype "passive"))
      (node (ref "L1") (pin "73") (pinfunction "73_73") (pintype "passive"))
    )
    (net (code "483") (name "/Y146") (class "Default")
      (node (ref "K143") (pin "7") (pinfunction "7_7") (pintype "passive"))
      (node (ref "K151") (pin "7") (pinfunction "7_7") (pintype "passive"))
      (node (ref "L1") (pin "74") (pinfunction "74_74") (pintype "passive"))
    )
    (net (code "484") (name "/Y148") (class "Default")
      (node (ref "K142") (pin "7") (pinfunction "7_7") (pintype "passive"))
      (node (ref "K150") (pin "7") (pinfunction "7_7") (pintype "passive"))
      (node (ref "L1") (pin "75") (pinfunction "75_75") (pintype "passive"))
    )
    (net (code "485") (name "/Y150") (class "Default")
      (node (ref "K141") (pin "7") (pinfunction "7_7") (pintype "passive"))
      (node (ref "K149") (pin "7") (pinfunction "7_7") (pintype "passive"))
      (node (ref "L1") (pin "76") (pinfunction "76_76") (pintype "passive"))
    )
    (net (code "486") (name "/Y152") (class "Default")
      (node (ref "K156") (pin "7") (pinfunction "7_7") (pintype "passive"))
      (node (ref "K160") (pin "7") (pinfunction "7_7") (pintype "passive"))
      (node (ref "L1") (pin "77") (pinfunction "77_77") (pintype "passive"))
    )
    (net (code "487") (name "/Y154") (class "Default")
      (node (ref "K155") (pin "7") (pinfunction "7_7") (pintype "passive"))
      (node (ref "K159") (pin "7") (pinfunction "7_7") (pintype "passive"))
      (node (ref "L1") (pin "78") (pinfunction "78_78") (pintype "passive"))
    )
    (net (code "488") (name "/Y156") (class "Default")
      (node (ref "K154") (pin "7") (pinfunction "7_7") (pintype "passive"))
      (node (ref "K158") (pin "7") (pinfunction "7_7") (pintype "passive"))
      (node (ref "L1") (pin "79") (pinfunction "79_79") (pintype "passive"))
    )
    (net (code "489") (name "/Y158") (class "Default")
      (node (ref "K153") (pin "7") (pinfunction "7_7") (pintype "passive"))
      (node (ref "K157") (pin "7") (pinfunction "7_7") (pintype "passive"))
      (node (ref "L1") (pin "80") (pinfunction "80_80") (pintype "passive"))
    )
    (net (code "490") (name "/Y160") (class "Default")
      (node (ref "K164") (pin "7") (pinfunction "7_7") (pintype "passive"))
      (node (ref "K168") (pin "7") (pinfunction "7_7") (pintype "passive"))
      (node (ref "L1") (pin "81") (pinfunction "81_81") (pintype "passive"))
    )
    (net (code "491") (name "/Y162") (class "Default")
      (node (ref "K163") (pin "7") (pinfunction "7_7") (pintype "passive"))
      (node (ref "K167") (pin "7") (pinfunction "7_7") (pintype "passive"))
      (node (ref "L1") (pin "82") (pinfunction "82_82") (pintype "passive"))
    )
    (net (code "492") (name "/Y164") (class "Default")
      (node (ref "K162") (pin "7") (pinfunction "7_7") (pintype "passive"))
      (node (ref "K166") (pin "7") (pinfunction "7_7") (pintype "passive"))
      (node (ref "L1") (pin "83") (pinfunction "83_83") (pintype "passive"))
    )
    (net (code "493") (name "/Y166") (class "Default")
      (node (ref "K161") (pin "7") (pinfunction "7_7") (pintype "passive"))
      (node (ref "K165") (pin "7") (pinfunction "7_7") (pintype "passive"))
      (node (ref "L1") (pin "84") (pinfunction "84_84") (pintype "passive"))
    )
    (net (code "494") (name "/Y168") (class "Default")
      (node (ref "K172") (pin "7") (pinfunction "7_7") (pintype "passive"))
      (node (ref "K176") (pin "7") (pinfunction "7_7") (pintype "passive"))
      (node (ref "L1") (pin "85") (pinfunction "85_85") (pintype "passive"))
    )
    (net (code "495") (name "/Y170") (class "Default")
      (node (ref "K171") (pin "7") (pinfunction "7_7") (pintype "passive"))
      (node (ref "K175") (pin "7") (pinfunction "7_7") (pintype "passive"))
      (node (ref "L1") (pin "86") (pinfunction "86_86") (pintype "passive"))
    )
    (net (code "496") (name "/Y172") (class "Default")
      (node (ref "K170") (pin "7") (pinfunction "7_7") (pintype "passive"))
      (node (ref "K174") (pin "7") (pinfunction "7_7") (pintype "passive"))
      (node (ref "L1") (pin "87") (pinfunction "87_87") (pintype "passive"))
    )
    (net (code "497") (name "/Y174") (class "Default")
      (node (ref "K169") (pin "7") (pinfunction "7_7") (pintype "passive"))
      (node (ref "K173") (pin "7") (pinfunction "7_7") (pintype "passive"))
      (node (ref "L1") (pin "88") (pinfunction "88_88") (pintype "passive"))
    )
    (net (code "498") (name "/Y176") (class "Default")
      (node (ref "K180") (pin "7") (pinfunction "7_7") (pintype "passive"))
      (node (ref "K184") (pin "7") (pinfunction "7_7") (pintype "passive"))
      (node (ref "L1") (pin "89") (pinfunction "89_89") (pintype "passive"))
    )
    (net (code "499") (name "/Y178") (class "Default")
      (node (ref "K179") (pin "7") (pinfunction "7_7") (pintype "passive"))
      (node (ref "K183") (pin "7") (pinfunction "7_7") (pintype "passive"))
      (node (ref "L1") (pin "90") (pinfunction "90_90") (pintype "passive"))
    )
    (net (code "500") (name "/Y180") (class "Default")
      (node (ref "K178") (pin "7") (pinfunction "7_7") (pintype "passive"))
      (node (ref "K182") (pin "7") (pinfunction "7_7") (pintype "passive"))
      (node (ref "L1") (pin "91") (pinfunction "91_91") (pintype "passive"))
    )
    (net (code "501") (name "/Y182") (class "Default")
      (node (ref "K177") (pin "7") (pinfunction "7_7") (pintype "passive"))
      (node (ref "K181") (pin "7") (pinfunction "7_7") (pintype "passive"))
      (node (ref "L1") (pin "92") (pinfunction "92_92") (pintype "passive"))
    )
    (net (code "502") (name "/Y184") (class "Default")
      (node (ref "K188") (pin "7") (pinfunction "7_7") (pintype "passive"))
      (node (ref "K192") (pin "7") (pinfunction "7_7") (pintype "passive"))
      (node (ref "L1") (pin "93") (pinfunction "93_93") (pintype "passive"))
    )
    (net (code "503") (name "/Y186") (class "Default")
      (node (ref "K187") (pin "7") (pinfunction "7_7") (pintype "passive"))
      (node (ref "K191") (pin "7") (pinfunction "7_7") (pintype "passive"))
      (node (ref "L1") (pin "94") (pinfunction "94_94") (pintype "passive"))
    )
    (net (code "504") (name "/Y188") (class "Default")
      (node (ref "K186") (pin "7") (pinfunction "7_7") (pintype "passive"))
      (node (ref "K190") (pin "7") (pinfunction "7_7") (pintype "passive"))
      (node (ref "L1") (pin "95") (pinfunction "95_95") (pintype "passive"))
    )
    (net (code "505") (name "/Y190") (class "Default")
      (node (ref "K185") (pin "7") (pinfunction "7_7") (pintype "passive"))
      (node (ref "K189") (pin "7") (pinfunction "7_7") (pintype "passive"))
      (node (ref "L1") (pin "96") (pinfunction "96_96") (pintype "passive"))
    )
    (net (code "507") (name "Net-(D0-QS1)") (class "Default")
      (node (ref "D0") (pin "9") (pinfunction "QS1_9") (pintype "passive"))
      (node (ref "D1") (pin "2") (pinfunction "D_2") (pintype "passive"))
    )
    (net (code "508") (name "Net-(D1-QS1)") (class "Default")
      (node (ref "D1") (pin "9") (pinfunction "QS1_9") (pintype "passive"))
      (node (ref "D2") (pin "2") (pinfunction "D_2") (pintype "passive"))
    )
    (net (code "509") (name "Net-(D2-QS1)") (class "Default")
      (node (ref "D2") (pin "9") (pinfunction "QS1_9") (pintype "passive"))
      (node (ref "D3") (pin "2") (pinfunction "D_2") (pintype "passive"))
    )
    (net (code "510") (name "Net-(D3-QS1)") (class "Default")
      (node (ref "D3") (pin "9") (pinfunction "QS1_9") (pintype "passive"))
      (node (ref "D4") (pin "2") (pinfunction "D_2") (pintype "passive"))
    )
    (net (code "511") (name "Net-(D4-QS1)") (class "Default")
      (node (ref "D4") (pin "9") (pinfunction "QS1_9") (pintype "passive"))
      (node (ref "D5") (pin "2") (pinfunction "D_2") (pintype "passive"))
    )
    (net (code "512") (name "Net-(D5-QS1)") (class "Default")
      (node (ref "D5") (pin "9") (pinfunction "QS1_9") (pintype "passive"))
      (node (ref "D6") (pin "2") (pinfunction "D_2") (pintype "passive"))
    )
    (net (code "513") (name "Net-(D6-QS1)") (class "Default")
      (node (ref "D6") (pin "9") (pinfunction "QS1_9") (pintype "passive"))
      (node (ref "D7") (pin "2") (pinfunction "D_2") (pintype "passive"))
    )
    (net (code "514") (name "Net-(D7-QS1)") (class "Default")
      (node (ref "D7") (pin "9") (pinfunction "QS1_9") (pintype "passive"))
      (node (ref "D8") (pin "2") (pinfunction "D_2") (pintype "passive"))
    )
    (net (code "515") (name "Net-(D8-QS1)") (class "Default")
      (node (ref "D8") (pin "9") (pinfunction "QS1_9") (pintype "passive"))
      (node (ref "D9") (pin "2") (pinfunction "D_2") (pintype "passive"))
    )
    (net (code "516") (name "Net-(D10-D)") (class "Default")
      (node (ref "D10") (pin "2") (pinfunction "D_2") (pintype "passive"))
      (node (ref "D9") (pin "9") (pinfunction "QS1_9") (pintype "passive"))
    )
    (net (code "517") (name "Net-(D10-QS1)") (class "Default")
      (node (ref "D10") (pin "9") (pinfunction "QS1_9") (pintype "passive"))
      (node (ref "D11") (pin "2") (pinfunction "D_2") (pintype "passive"))
    )
    (net (code "518") (name "Net-(D11-QS1)") (class "Default")
      (node (ref "D11") (pin "9") (pinfunction "QS1_9") (pintype "passive"))
      (node (ref "D12") (pin "2") (pinfunction "D_2") (pintype "passive"))
    )
    (net (code "519") (name "Net-(D12-QS1)") (class "Default")
      (node (ref "D12") (pin "9") (pinfunction "QS1_9") (pintype "passive"))
      (node (ref "D13") (pin "2") (pinfunction "D_2") (pintype "passive"))
    )
    (net (code "520") (name "Net-(D13-QS1)") (class "Default")
      (node (ref "D13") (pin "9") (pinfunction "QS1_9") (pintype "passive"))
      (node (ref "D14") (pin "2") (pinfunction "D_2") (pintype "passive"))
    )
    (net (code "521") (name "Net-(D14-QS1)") (class "Default")
      (node (ref "D14") (pin "9") (pinfunction "QS1_9") (pintype "passive"))
      (node (ref "D15") (pin "2") (pinfunction "D_2") (pintype "passive"))
    )
    (net (code "522") (name "Net-(D15-QS1)") (class "Default")
      (node (ref "D15") (pin "9") (pinfunction "QS1_9") (pintype "passive"))
      (node (ref "D16") (pin "2") (pinfunction "D_2") (pintype "passive"))
    )
    (net (code "523") (name "Net-(D16-QS1)") (class "Default")
      (node (ref "D16") (pin "9") (pinfunction "QS1_9") (pintype "passive"))
      (node (ref "D17") (pin "2") (pinfunction "D_2") (pintype "passive"))
    )
    (net (code "524") (name "Net-(D17-QS1)") (class "Default")
      (node (ref "D17") (pin "9") (pinfunction "QS1_9") (pintype "passive"))
      (node (ref "D18") (pin "2") (pinfunction "D_2") (pintype "passive"))
    )
    (net (code "525") (name "Net-(D18-QS1)") (class "Default")
      (node (ref "D18") (pin "9") (pinfunction "QS1_9") (pintype "passive"))
      (node (ref "D19") (pin "2") (pinfunction "D_2") (pintype "passive"))
    )
    (net (code "526") (name "Net-(D19-QS1)") (class "Default")
      (node (ref "D19") (pin "9") (pinfunction "QS1_9") (pintype "passive"))
      (node (ref "D20") (pin "2") (pinfunction "D_2") (pintype "passive"))
    )
    (net (code "527") (name "Net-(D20-QS1)") (class "Default")
      (node (ref "D20") (pin "9") (pinfunction "QS1_9") (pintype "passive"))
      (node (ref "D21") (pin "2") (pinfunction "D_2") (pintype "passive"))
    )
    (net (code "528") (name "Net-(D21-QS1)") (class "Default")
      (node (ref "D21") (pin "9") (pinfunction "QS1_9") (pintype "passive"))
      (node (ref "D22") (pin "2") (pinfunction "D_2") (pintype "passive"))
    )
    (net (code "529") (name "Net-(D22-QS1)") (class "Default")
      (node (ref "D22") (pin "9") (pinfunction "QS1_9") (pintype "passive"))
      (node (ref "D23") (pin "2") (pinfunction "D_2") (pintype "passive"))
    )
    (net (code "530") (name "unconnected-(D0-QS2-Pad10)") (class "Default")
      (node (ref "D0") (pin "10") (pinfunction "QS2_10") (pintype "passive"))
    )
    (net (code "531") (name "unconnected-(D1-QS2-Pad10)") (class "Default")
      (node (ref "D1") (pin "10") (pinfunction "QS2_10") (pintype "passive"))
    )
    (net (code "532") (name "unconnected-(D2-QS2-Pad10)") (class "Default")
      (node (ref "D2") (pin "10") (pinfunction "QS2_10") (pintype "passive"))
    )
    (net (code "533") (name "unconnected-(D3-QS2-Pad10)") (class "Default")
      (node (ref "D3") (pin "10") (pinfunction "QS2_10") (pintype "passive"))
    )
    (net (code "534") (name "unconnected-(D4-QS2-Pad10)") (class "Default")
      (node (ref "D4") (pin "10") (pinfunction "QS2_10") (pintype "passive"))
    )
    (net (code "535") (name "unconnected-(D5-QS2-Pad10)") (class "Default")
      (node (ref "D5") (pin "10") (pinfunction "QS2_10") (pintype "passive"))
    )
    (net (code "536") (name "unconnected-(D6-QS2-Pad10)") (class "Default")
      (node (ref "D6") (pin "10") (pinfunction "QS2_10") (pintype "passive"))
    )
    (net (code "537") (name "unconnected-(D7-QP4-Pad14)") (class "Default")
      (node (ref "D7") (pin "14") (pinfunction "QP4_14") (pintype "passive"))
    )
    (net (code "538") (name "unconnected-(D7-QS2-Pad10)") (class "Default")
      (node (ref "D7") (pin "10") (pinfunction "QS2_10") (pintype "passive"))
    )
    (net (code "539") (name "unconnected-(D8-QS2-Pad10)") (class "Default")
      (node (ref "D8") (pin "10") (pinfunction "QS2_10") (pintype "passive"))
    )
    (net (code "540") (name "unconnected-(D9-QS2-Pad10)") (class "Default")
      (node (ref "D9") (pin "10") (pinfunction "QS2_10") (pintype "passive"))
    )
    (net (code "541") (name "unconnected-(D10-QS2-Pad10)") (class "Default")
      (node (ref "D10") (pin "10") (pinfunction "QS2_10") (pintype "passive"))
    )
    (net (code "542") (name "unconnected-(D11-QS2-Pad10)") (class "Default")
      (node (ref "D11") (pin "10") (pinfunction "QS2_10") (pintype "passive"))
    )
    (net (code "543") (name "unconnected-(D12-QS2-Pad10)") (class "Default")
      (node (ref "D12") (pin "10") (pinfunction "QS2_10") (pintype "passive"))
    )
    (net (code "544") (name "unconnected-(D13-QS2-Pad10)") (class "Default")
      (node (ref "D13") (pin "10") (pinfunction "QS2_10") (pintype "passive"))
    )
    (net (code "545") (name "unconnected-(D14-QS2-Pad10)") (class "Default")
      (node (ref "D14") (pin "10") (pinfunction "QS2_10") (pintype "passive"))
    )
    (net (code "546") (name "unconnected-(D15-QS2-Pad10)") (class "Default")
      (node (ref "D15") (pin "10") (pinfunction "QS2_10") (pintype "passive"))
    )
    (net (code "547") (name "unconnected-(D16-QS2-Pad10)") (class "Default")
      (node (ref "D16") (pin "10") (pinfunction "QS2_10") (pintype "passive"))
    )
    (net (code "548") (name "unconnected-(D17-QS2-Pad10)") (class "Default")
      (node (ref "D17") (pin "10") (pinfunction "QS2_10") (pintype "passive"))
    )
    (net (code "549") (name "unconnected-(D18-QS2-Pad10)") (class "Default")
      (node (ref "D18") (pin "10") (pinfunction "QS2_10") (pintype "passive"))
    )
    (net (code "550") (name "unconnected-(D19-QS2-Pad10)") (class "Default")
      (node (ref "D19") (pin "10") (pinfunction "QS2_10") (pintype "passive"))
    )
    (net (code "551") (name "unconnected-(D20-QS2-Pad10)") (class "Default")
      (node (ref "D20") (pin "10") (pinfunction "QS2_10") (pintype "passive"))
    )
    (net (code "552") (name "unconnected-(D21-QS2-Pad10)") (class "Default")
      (node (ref "D21") (pin "10") (pinfunction "QS2_10") (pintype "passive"))
    )
    (net (code "553") (name "unconnected-(D22-QS2-Pad10)") (class "Default")
      (node (ref "D22") (pin "10") (pinfunction "QS2_10") (pintype "passive"))
    )
    (net (code "554") (name "unconnected-(D23-QS2-Pad10)") (class "Default")
      (node (ref "D23") (pin "10") (pinfunction "QS2_10") (pintype "passive"))
    )
    (net (code "555") (name "unconnected-(PLD1-Pad10)") (class "Default")
      (node (ref "PLD1") (pin "10") (pinfunction "10_10") (pintype "passive"))
    )
  )
)
